# MCU.net
KiCad netlist of a schematic drawn in EAGLE
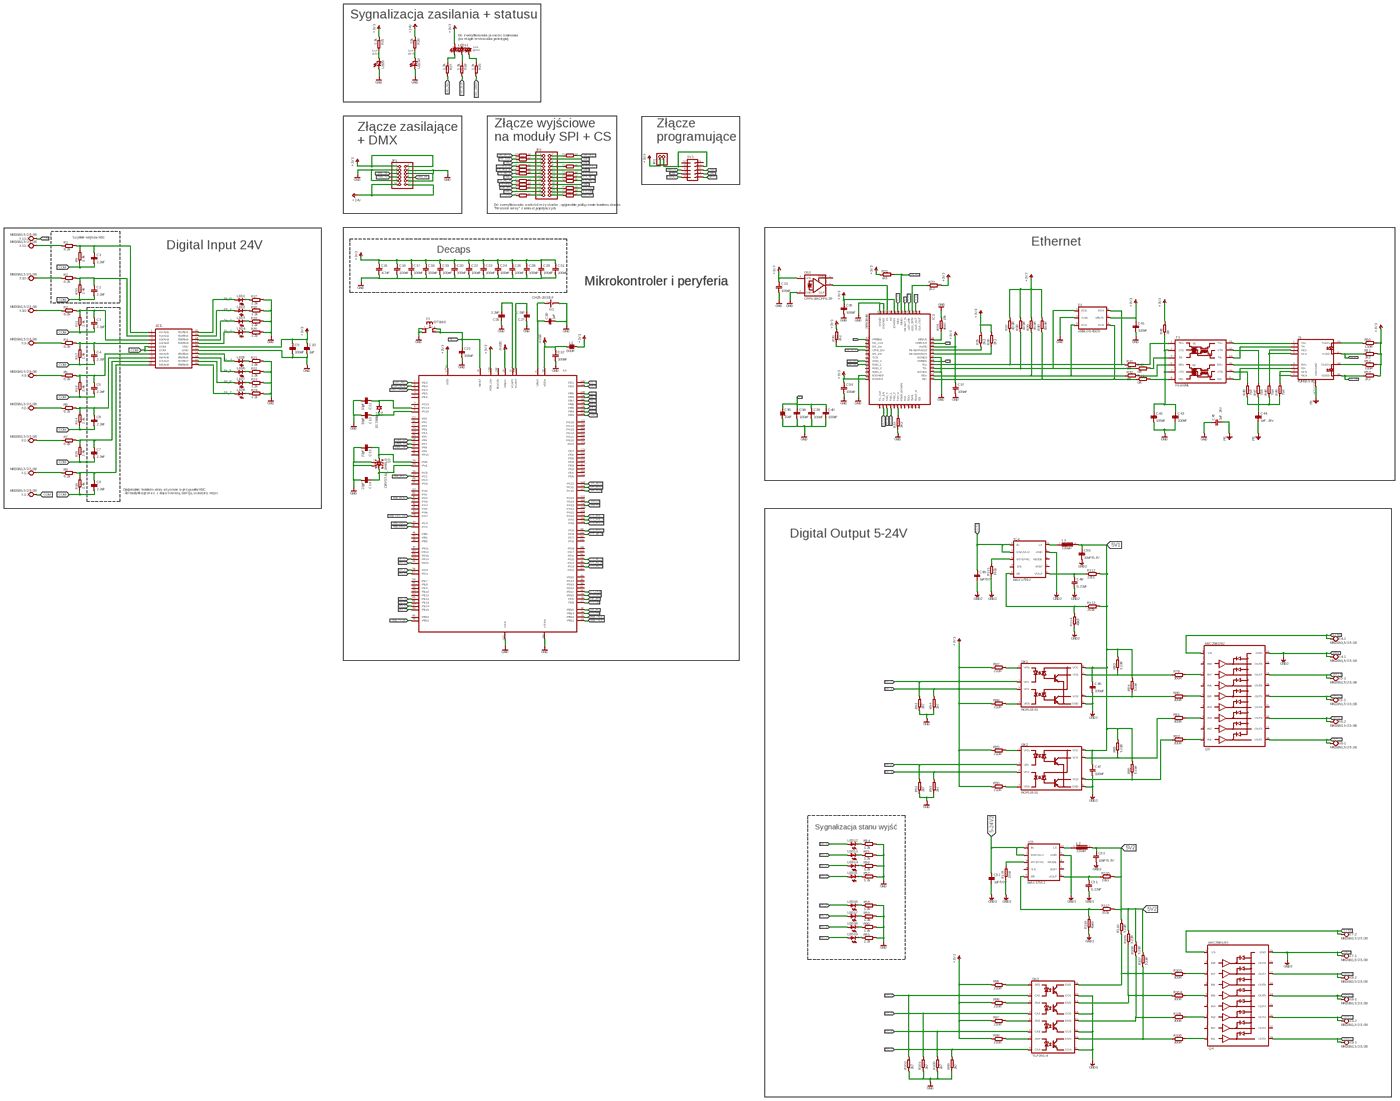
[diagram p0: schematic, sheet 1, overview]
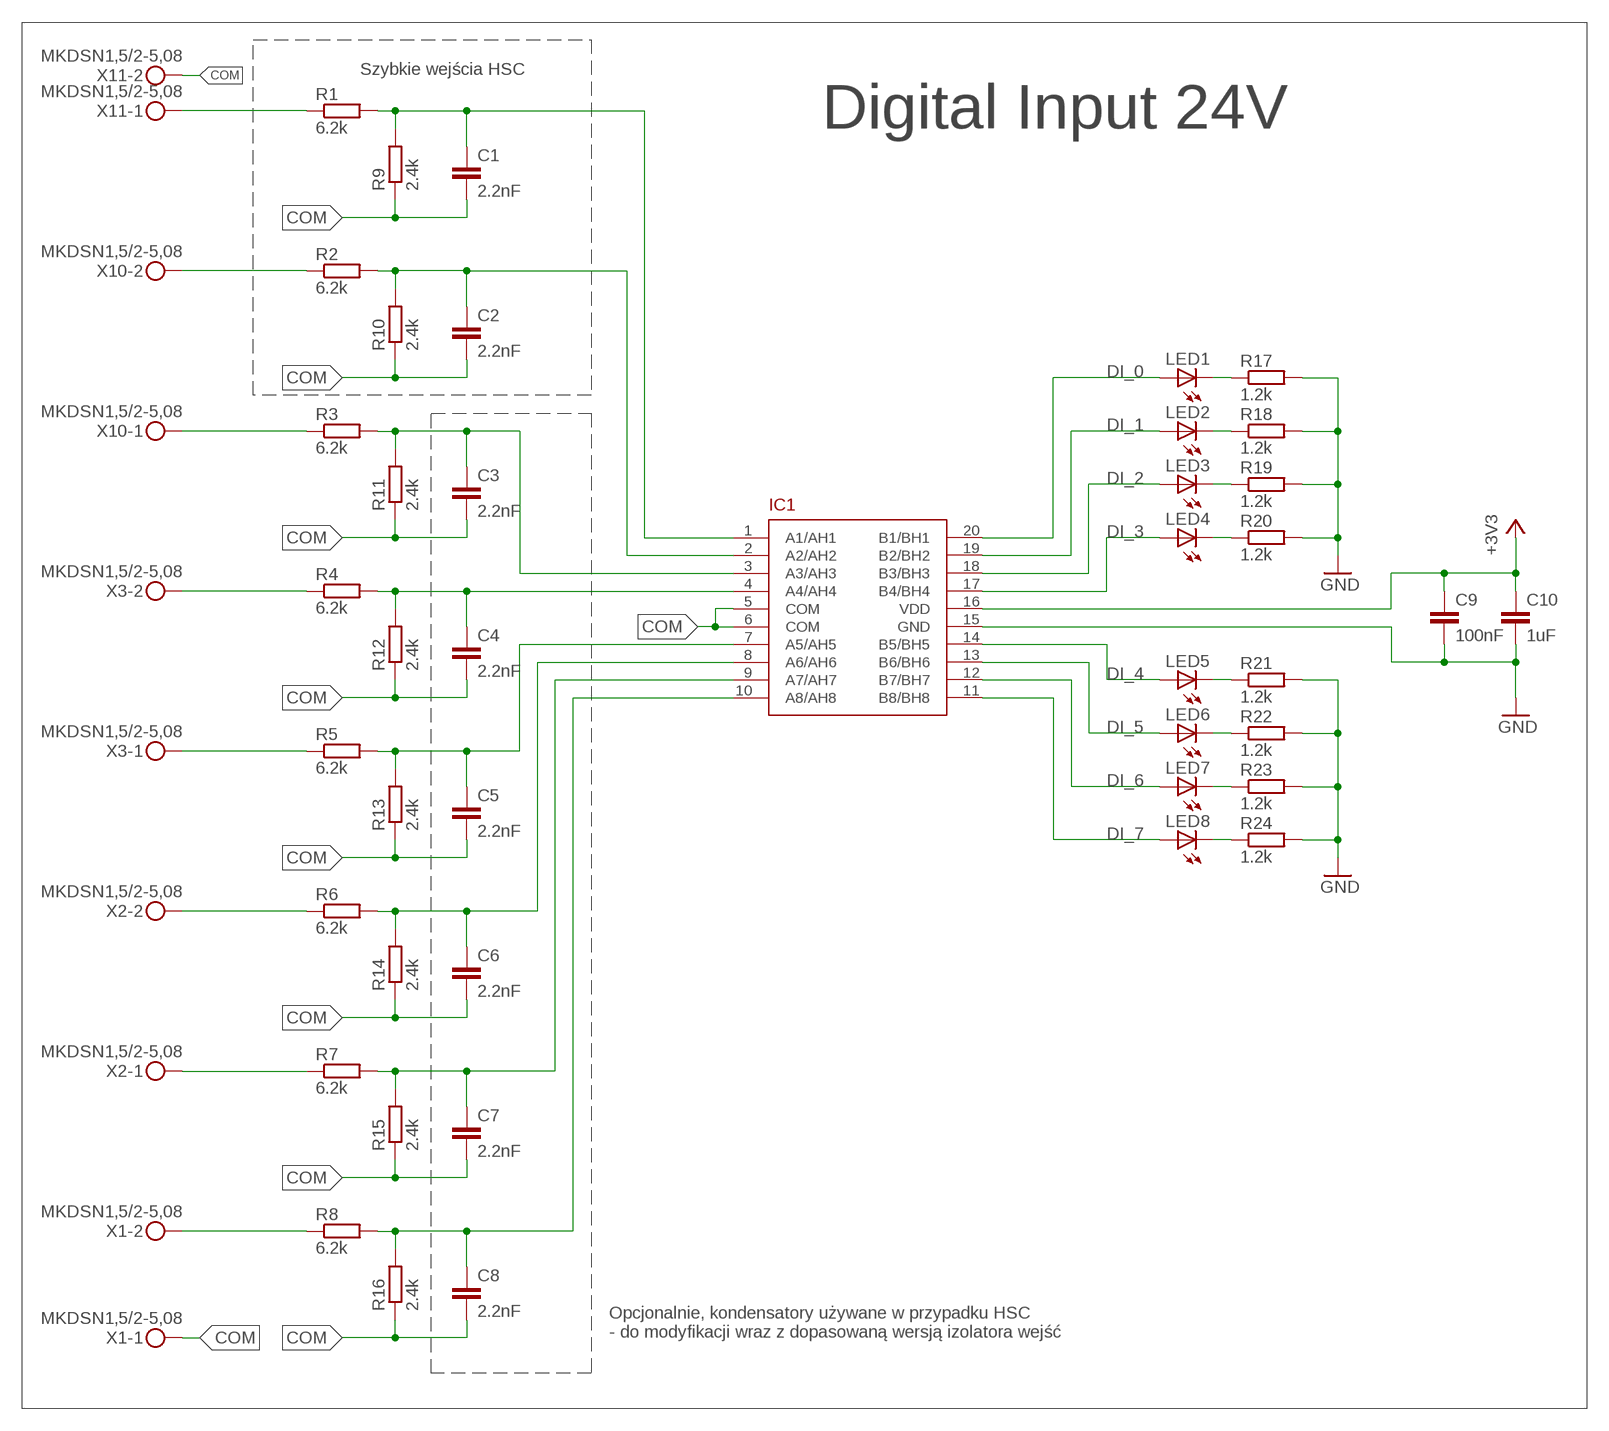
[diagram p1: schematic, sheet 1, part 1 of 5]
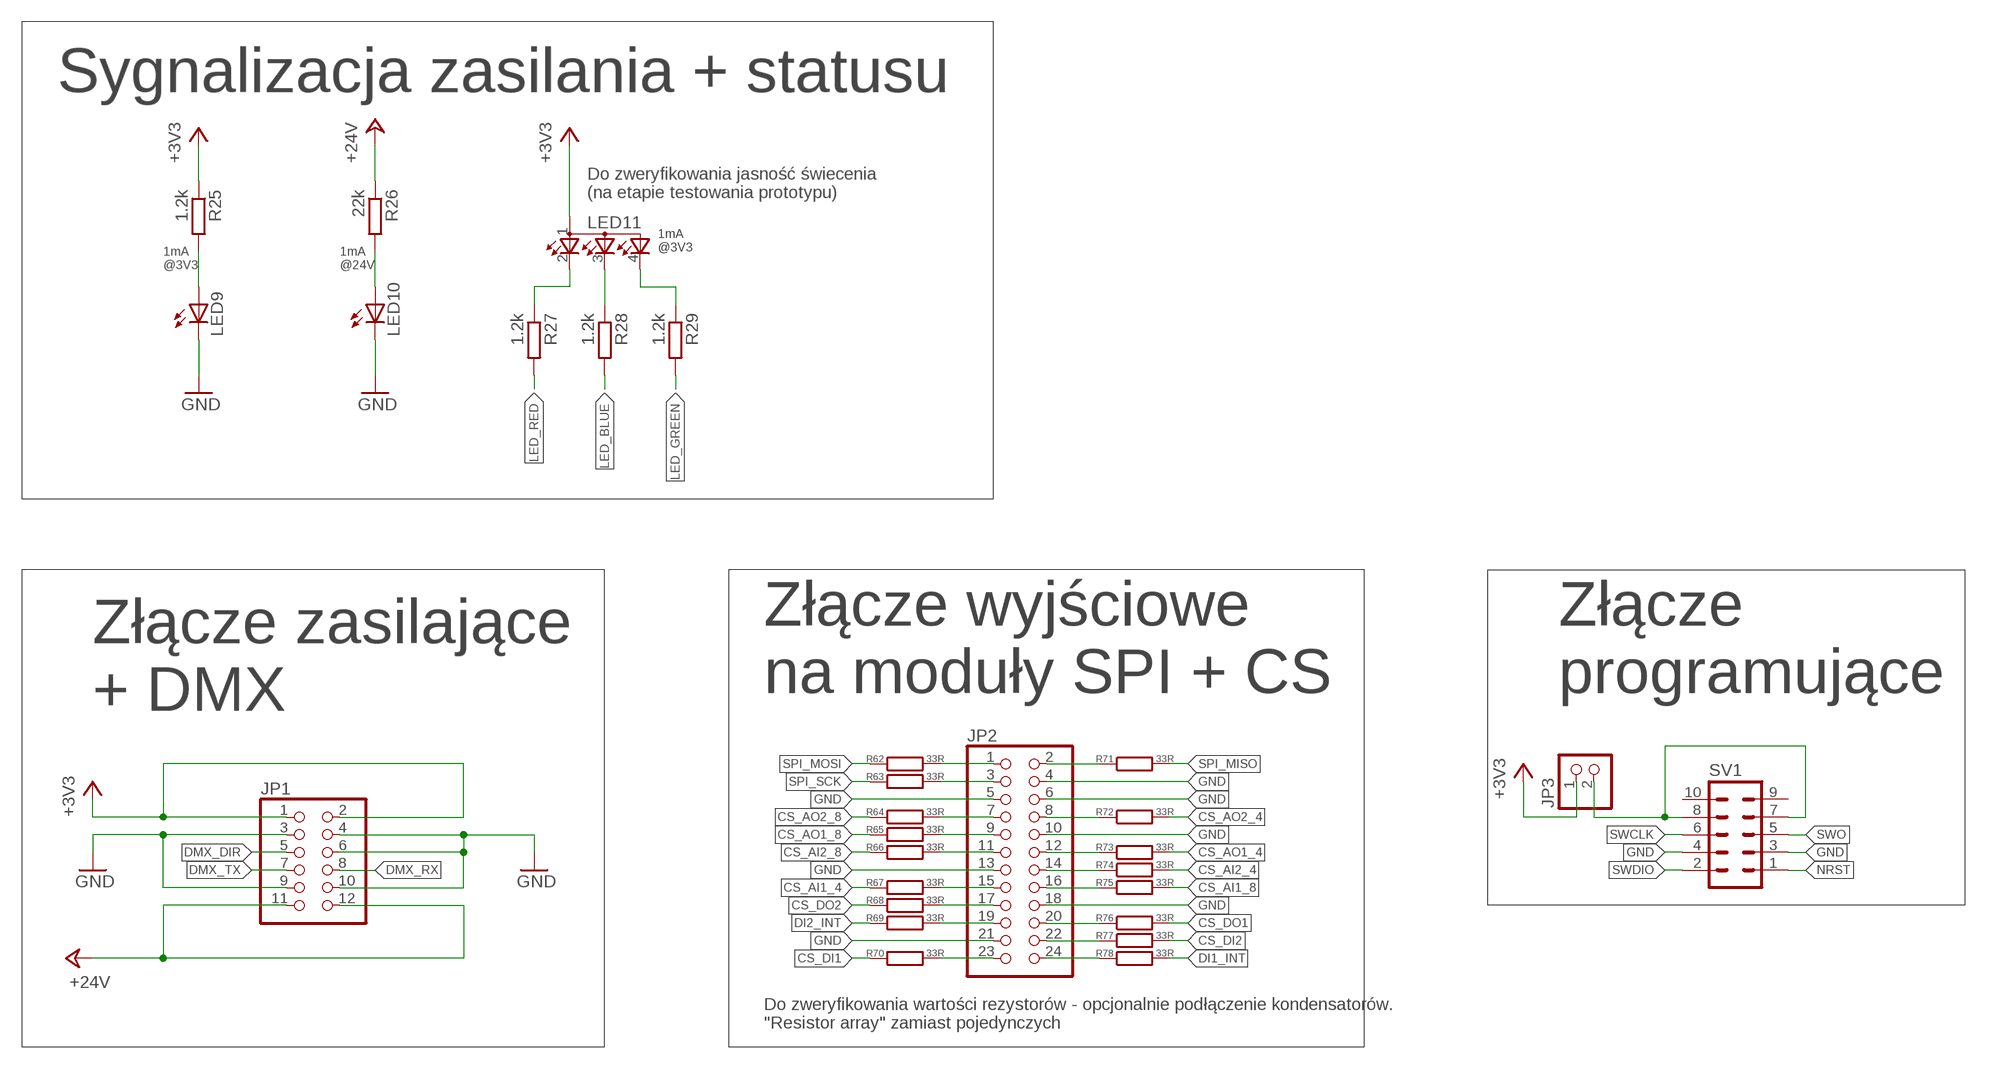
[diagram p2: schematic, sheet 1, part 2 of 5]
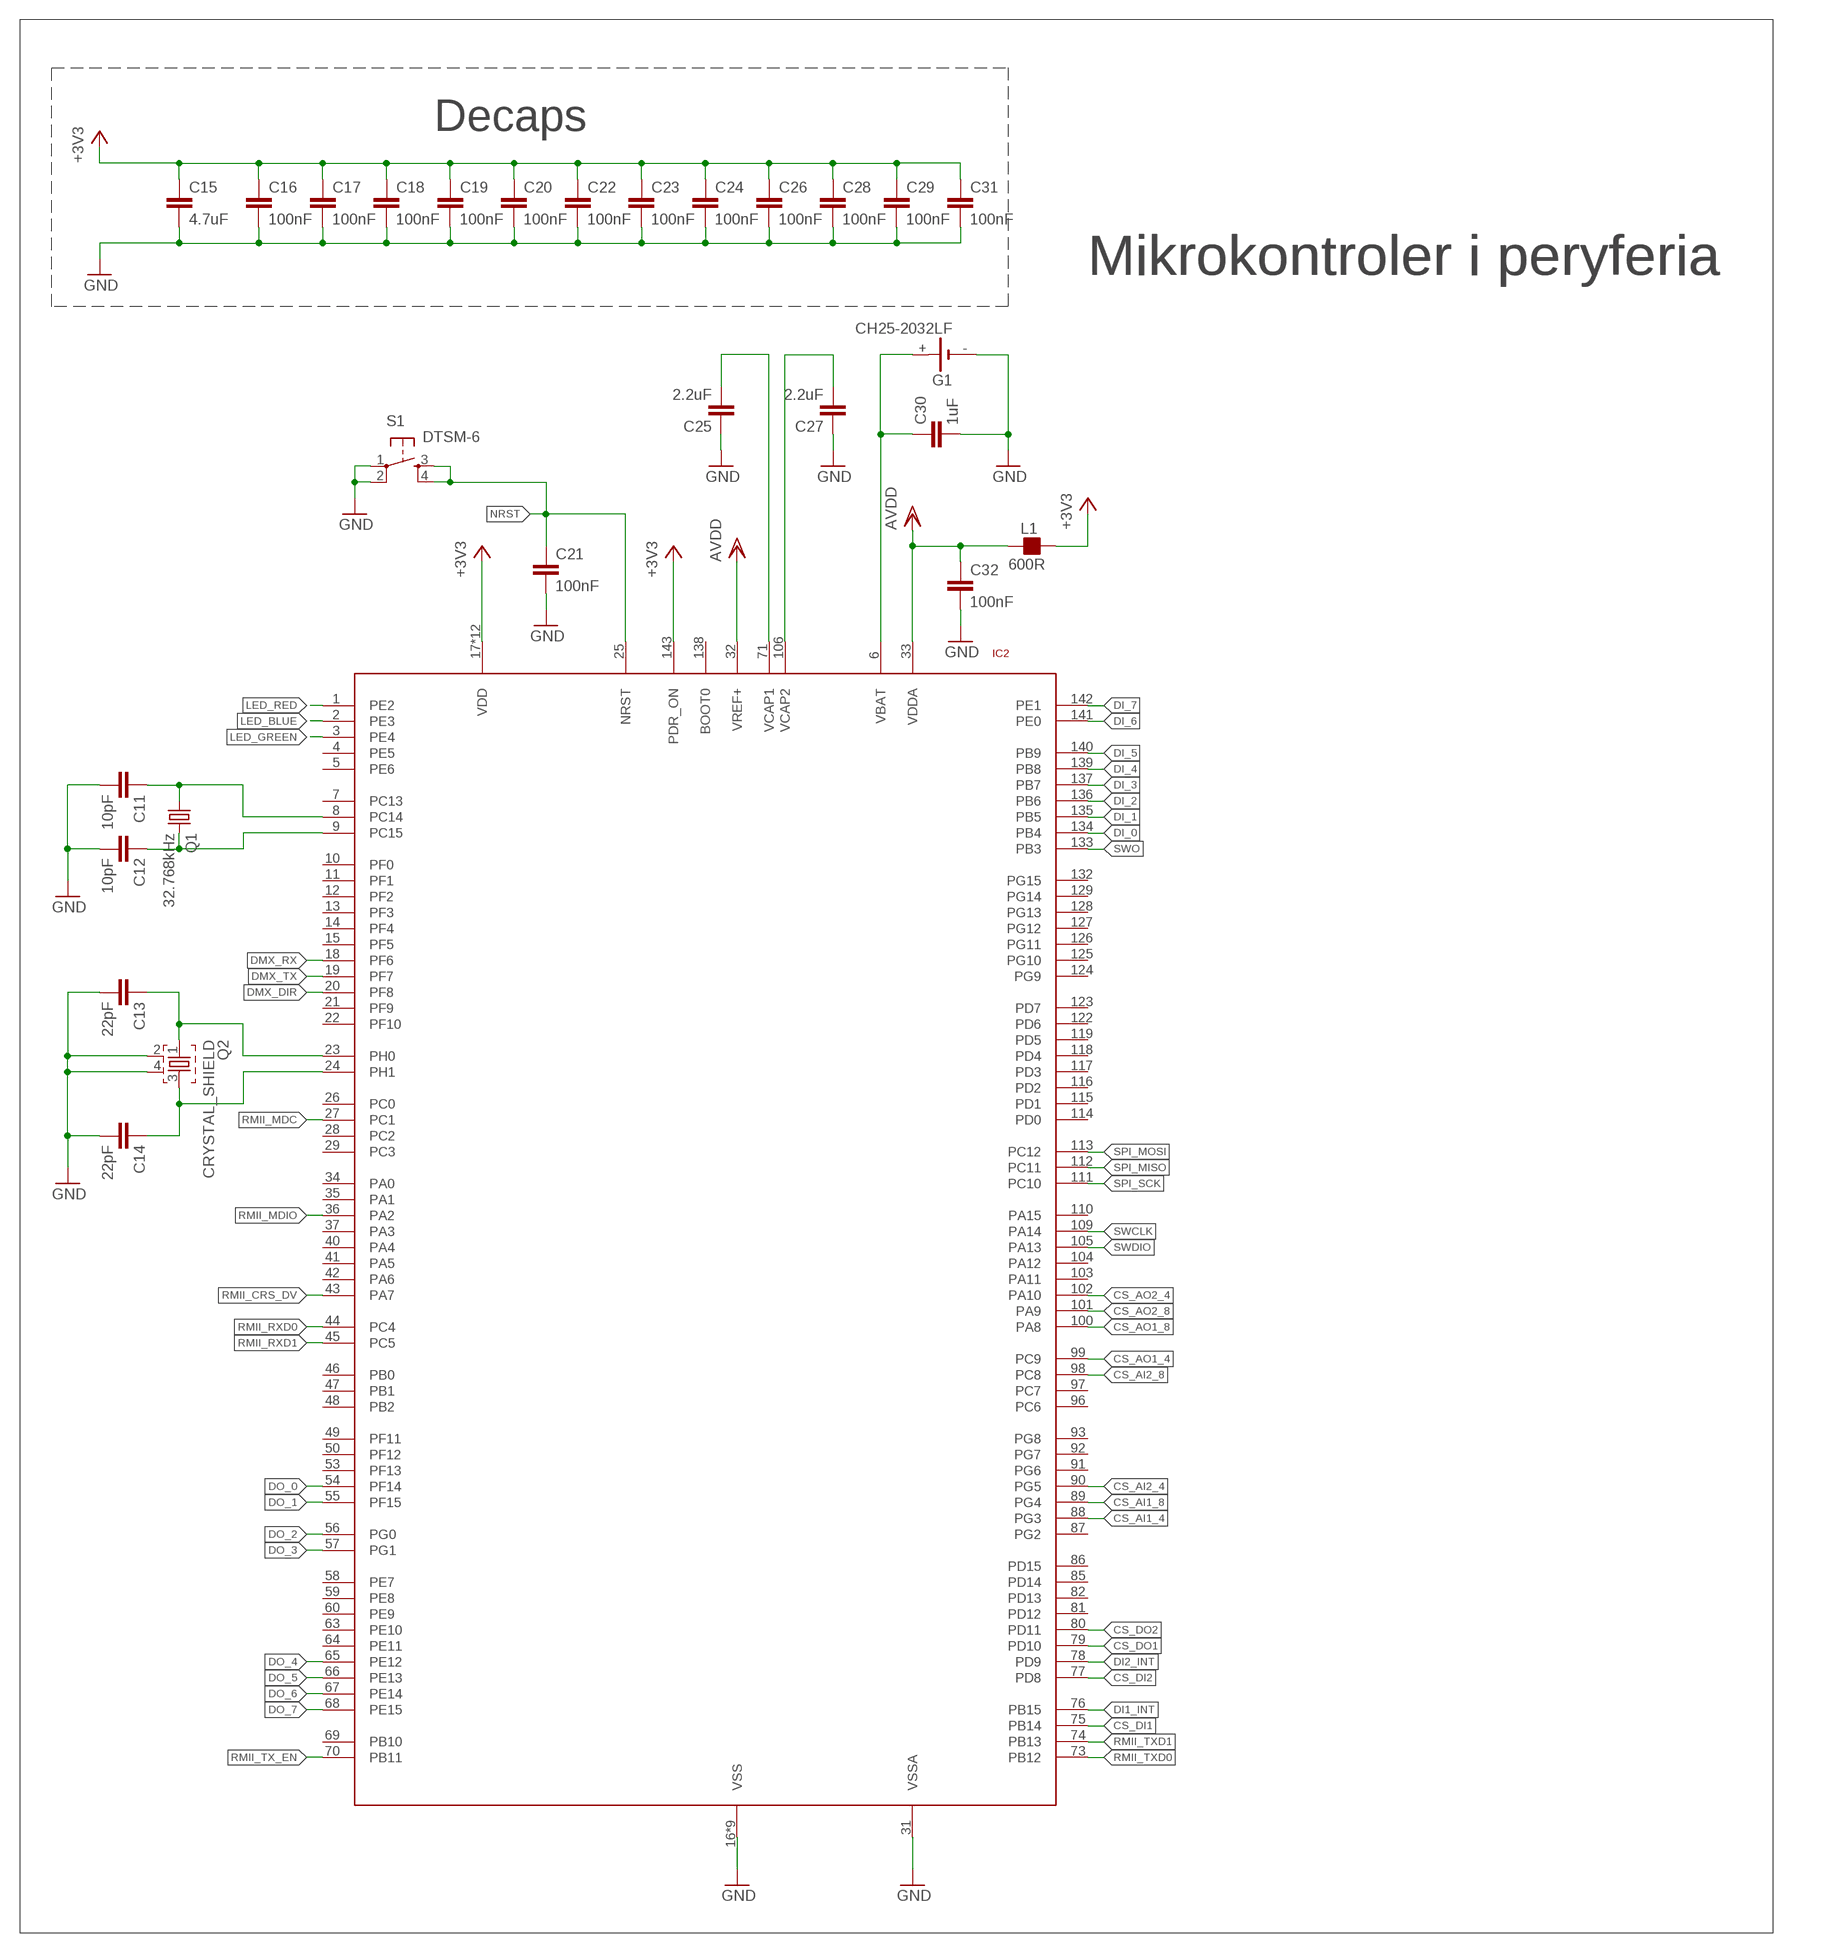
[diagram p3: schematic, sheet 1, part 3 of 5]
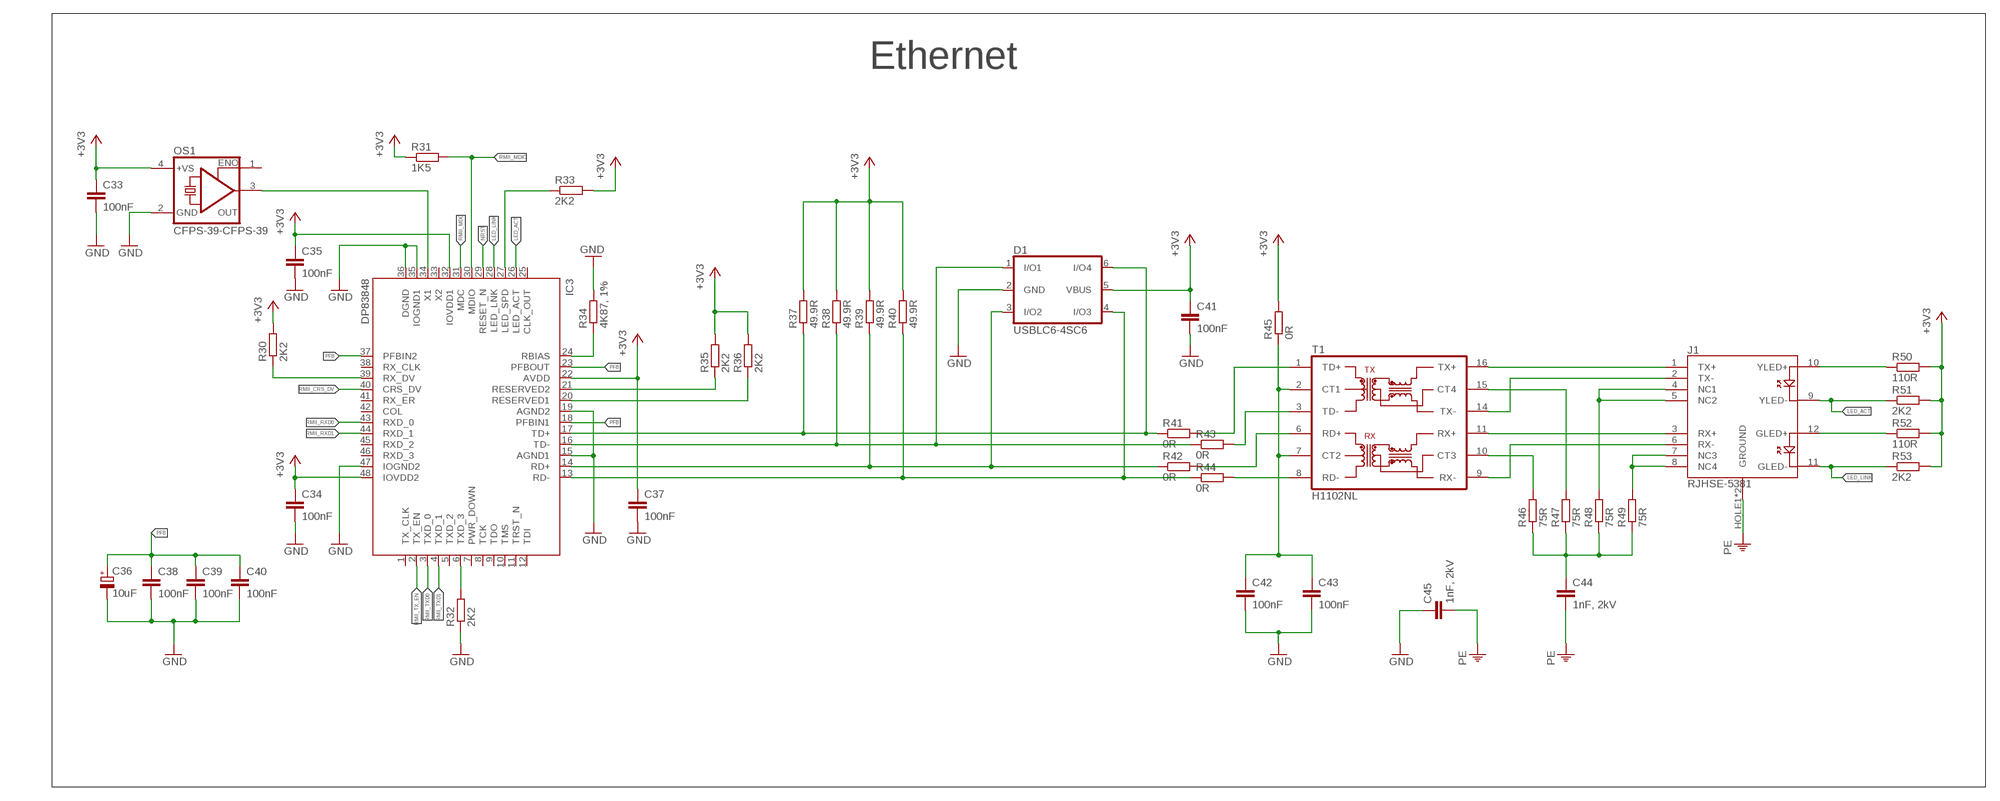
[diagram p4: schematic, sheet 1, part 4 of 5]
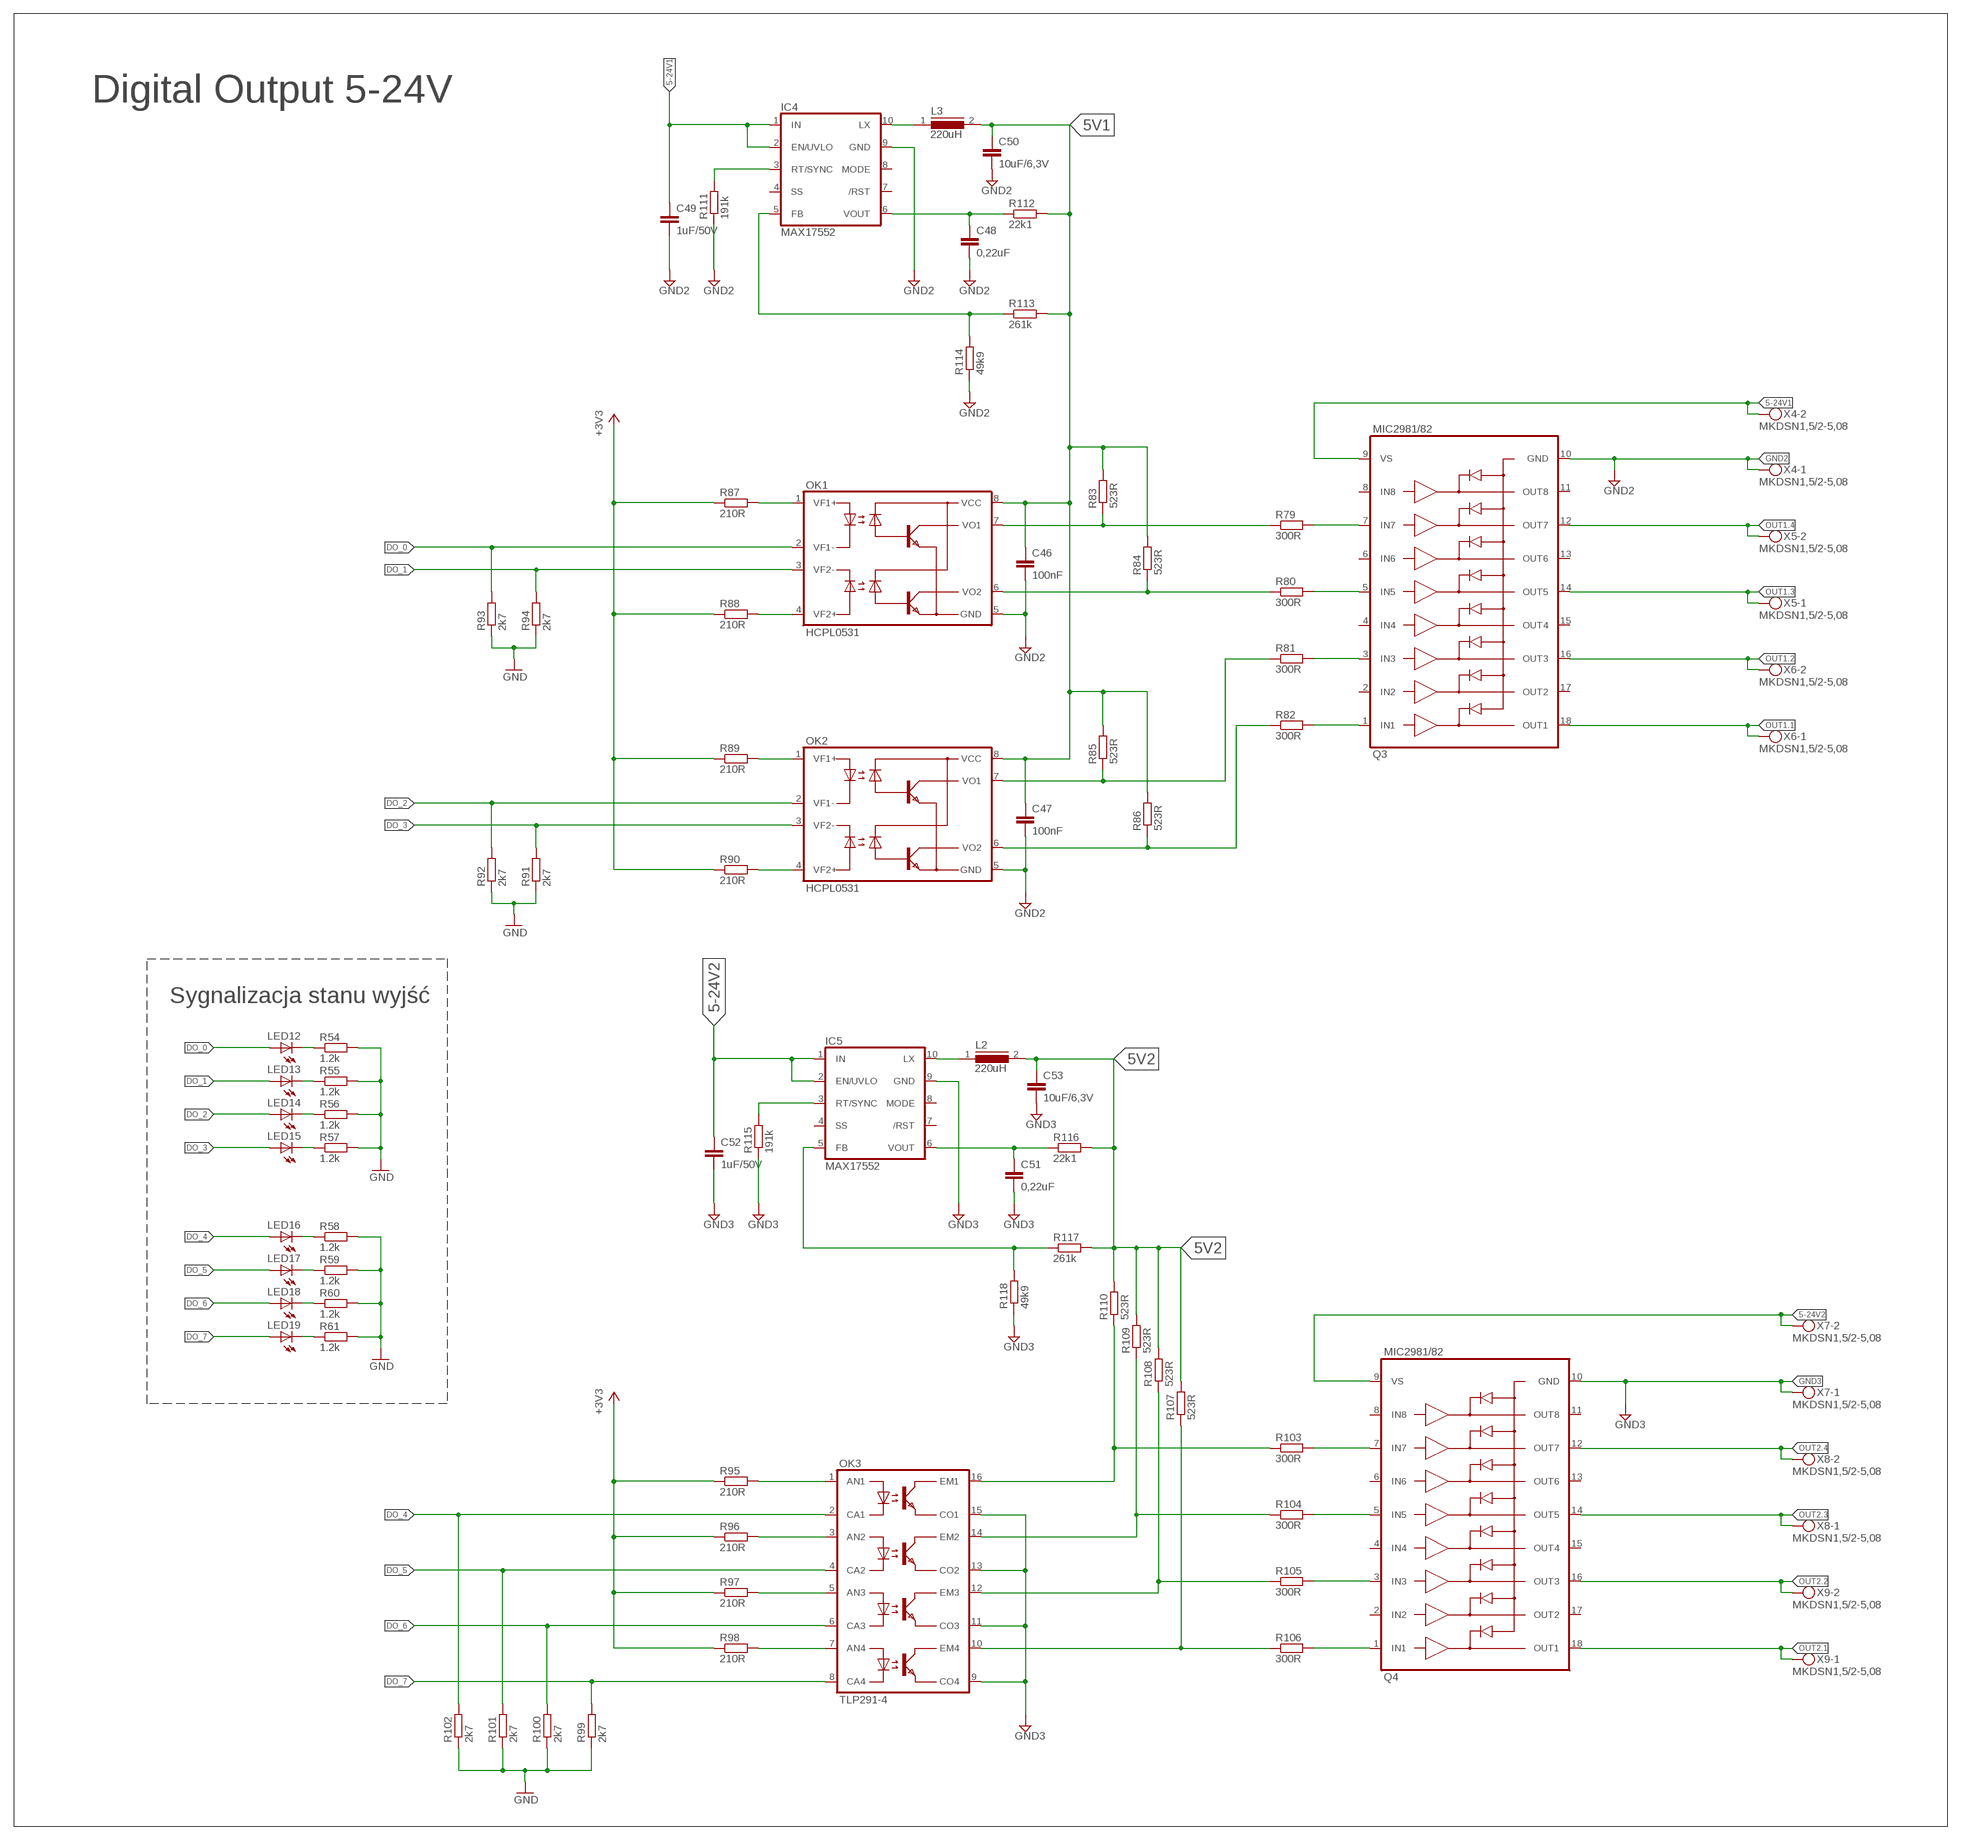
[diagram p5: schematic, sheet 1, part 5 of 5]

(export (version "E")
  (design (tool "Eeschema 10.0.6"))
  (components
    (comp (ref "C1")
      (value "2.2nF")
      (footprint "eagle-import:C0805")
      (fields (field (name "MF") "AVX") (field (name "MPN") "06035C222JAT2A"))
      (libsource (lib "eagle-import") (part "C-EUC0805"))
    )
    (comp (ref "C2")
      (value "2.2nF")
      (footprint "eagle-import:C0805")
      (fields (field (name "MF") "AVX") (field (name "MPN") "06035C222JAT2A"))
      (libsource (lib "eagle-import") (part "C-EUC0805"))
    )
    (comp (ref "C3")
      (value "2.2nF")
      (footprint "eagle-import:C0805")
      (fields (field (name "MF") "AVX") (field (name "MPN") "06035C222JAT2A"))
      (libsource (lib "eagle-import") (part "C-EUC0805"))
    )
    (comp (ref "C4")
      (value "2.2nF")
      (footprint "eagle-import:C0805")
      (fields (field (name "MF") "AVX") (field (name "MPN") "06035C222JAT2A"))
      (libsource (lib "eagle-import") (part "C-EUC0805"))
    )
    (comp (ref "C5")
      (value "2.2nF")
      (footprint "eagle-import:C0805")
      (fields (field (name "MF") "AVX") (field (name "MPN") "06035C222JAT2A"))
      (libsource (lib "eagle-import") (part "C-EUC0805"))
    )
    (comp (ref "C6")
      (value "2.2nF")
      (footprint "eagle-import:C0805")
      (fields (field (name "MF") "AVX") (field (name "MPN") "06035C222JAT2A"))
      (libsource (lib "eagle-import") (part "C-EUC0805"))
    )
    (comp (ref "C7")
      (value "2.2nF")
      (footprint "eagle-import:C0805")
      (fields (field (name "MF") "AVX") (field (name "MPN") "06035C222JAT2A"))
      (libsource (lib "eagle-import") (part "C-EUC0805"))
    )
    (comp (ref "C8")
      (value "2.2nF")
      (footprint "eagle-import:C0805")
      (fields (field (name "MF") "AVX") (field (name "MPN") "06035C222JAT2A"))
      (libsource (lib "eagle-import") (part "C-EUC0805"))
    )
    (comp (ref "C9")
      (value "100nF")
      (footprint "eagle-import:C0603K")
      (fields (field (name "MF") "AVX") (field (name "MPN") "06033C104KAT2A"))
      (libsource (lib "eagle-import") (part "C-EUC0603K"))
    )
    (comp (ref "C10")
      (value "1uF")
      (footprint "eagle-import:C0603K")
      (fields (field (name "MF") "AVX") (field (name "MPN") "0603YC105KAT4A"))
      (libsource (lib "eagle-import") (part "C-EUC0603K"))
    )
    (comp (ref "C11")
      (value "10pF")
      (footprint "eagle-import:C0603K")
      (fields (field (name "MF") "AVX") (field (name "MPN") "06035A100JAT2A"))
      (libsource (lib "eagle-import") (part "C-EUC0603K"))
    )
    (comp (ref "C12")
      (value "10pF")
      (footprint "eagle-import:C0603K")
      (fields (field (name "MF") "AVX") (field (name "MPN") "06035A100JAT2A"))
      (libsource (lib "eagle-import") (part "C-EUC0603K"))
    )
    (comp (ref "C13")
      (value "22pF")
      (footprint "eagle-import:C0603K")
      (fields (field (name "MF") "AVX") (field (name "MPN") "06035A220JAT2A"))
      (libsource (lib "eagle-import") (part "C-EUC0603K"))
    )
    (comp (ref "C14")
      (value "22pF")
      (footprint "eagle-import:C0603K")
      (fields (field (name "MF") "AVX") (field (name "MPN") "06035A220JAT2A"))
      (libsource (lib "eagle-import") (part "C-EUC0603K"))
    )
    (comp (ref "C15")
      (value "4.7uF")
      (footprint "eagle-import:C0603K")
      (fields (field (name "MF") "AVX") (field (name "MPN") "0603ZD475KAT2A"))
      (libsource (lib "eagle-import") (part "C-EUC0603K"))
    )
    (comp (ref "C16")
      (value "100nF")
      (footprint "eagle-import:C0603K")
      (fields (field (name "MF") "AVX") (field (name "MPN") "06033C104KAT2A"))
      (libsource (lib "eagle-import") (part "C-EUC0603K"))
    )
    (comp (ref "C17")
      (value "100nF")
      (footprint "eagle-import:C0603K")
      (fields (field (name "MF") "AVX") (field (name "MPN") "06033C104KAT2A"))
      (libsource (lib "eagle-import") (part "C-EUC0603K"))
    )
    (comp (ref "C18")
      (value "100nF")
      (footprint "eagle-import:C0603K")
      (fields (field (name "MF") "AVX") (field (name "MPN") "06033C104KAT2A"))
      (libsource (lib "eagle-import") (part "C-EUC0603K"))
    )
    (comp (ref "C19")
      (value "100nF")
      (footprint "eagle-import:C0603K")
      (fields (field (name "MF") "AVX") (field (name "MPN") "06033C104KAT2A"))
      (libsource (lib "eagle-import") (part "C-EUC0603K"))
    )
    (comp (ref "C20")
      (value "100nF")
      (footprint "eagle-import:C0603K")
      (fields (field (name "MF") "AVX") (field (name "MPN") "06033C104KAT2A"))
      (libsource (lib "eagle-import") (part "C-EUC0603K"))
    )
    (comp (ref "C21")
      (value "100nF")
      (footprint "eagle-import:C0603K")
      (fields (field (name "MF") "AVX") (field (name "MPN") "06033C104KAT2A"))
      (libsource (lib "eagle-import") (part "C-EUC0603K"))
    )
    (comp (ref "C22")
      (value "100nF")
      (footprint "eagle-import:C0603K")
      (fields (field (name "MF") "AVX") (field (name "MPN") "06033C104KAT2A"))
      (libsource (lib "eagle-import") (part "C-EUC0603K"))
    )
    (comp (ref "C23")
      (value "100nF")
      (footprint "eagle-import:C0603K")
      (fields (field (name "MF") "AVX") (field (name "MPN") "06033C104KAT2A"))
      (libsource (lib "eagle-import") (part "C-EUC0603K"))
    )
    (comp (ref "C24")
      (value "100nF")
      (footprint "eagle-import:C0603K")
      (fields (field (name "MF") "AVX") (field (name "MPN") "06033C104KAT2A"))
      (libsource (lib "eagle-import") (part "C-EUC0603K"))
    )
    (comp (ref "C25")
      (value "2.2uF")
      (footprint "eagle-import:C0603K")
      (fields (field (name "MF") "AVX") (field (name "MPN") "06036C225KAT2A"))
      (libsource (lib "eagle-import") (part "C-EUC0603K"))
    )
    (comp (ref "C26")
      (value "100nF")
      (footprint "eagle-import:C0603K")
      (fields (field (name "MF") "AVX") (field (name "MPN") "06033C104KAT2A"))
      (libsource (lib "eagle-import") (part "C-EUC0603K"))
    )
    (comp (ref "C27")
      (value "2.2uF")
      (footprint "eagle-import:C0603K")
      (fields (field (name "MF") "AVX") (field (name "MPN") "06036C225KAT2A"))
      (libsource (lib "eagle-import") (part "C-EUC0603K"))
    )
    (comp (ref "C28")
      (value "100nF")
      (footprint "eagle-import:C0603K")
      (fields (field (name "MF") "AVX") (field (name "MPN") "06033C104KAT2A"))
      (libsource (lib "eagle-import") (part "C-EUC0603K"))
    )
    (comp (ref "C29")
      (value "100nF")
      (footprint "eagle-import:C0603K")
      (fields (field (name "MF") "AVX") (field (name "MPN") "06033C104KAT2A"))
      (libsource (lib "eagle-import") (part "C-EUC0603K"))
    )
    (comp (ref "C30")
      (value "1uF")
      (footprint "eagle-import:C0603K")
      (fields (field (name "MF") "AVX") (field (name "MPN") "0603YC105KAT4A"))
      (libsource (lib "eagle-import") (part "C-EUC0603K"))
    )
    (comp (ref "C31")
      (value "100nF")
      (footprint "eagle-import:C0603K")
      (fields (field (name "MF") "AVX") (field (name "MPN") "06033C104KAT2A"))
      (libsource (lib "eagle-import") (part "C-EUC0603K"))
    )
    (comp (ref "C32")
      (value "100nF")
      (footprint "eagle-import:C0603K")
      (fields (field (name "MF") "AVX") (field (name "MPN") "06033C104KAT2A"))
      (libsource (lib "eagle-import") (part "C-EUC0603K"))
    )
    (comp (ref "C33")
      (value "100nF")
      (footprint "eagle-import:C0603")
      (fields (field (name "MF") "AVX") (field (name "MPN") "06033C104KAT2A"))
      (libsource (lib "eagle-import") (part "C-EUC0603"))
    )
    (comp (ref "C34")
      (value "100nF")
      (footprint "eagle-import:C0603")
      (fields (field (name "MF") "AVX") (field (name "MPN") "06033C104KAT2A"))
      (libsource (lib "eagle-import") (part "C-EUC0603"))
    )
    (comp (ref "C35")
      (value "100nF")
      (footprint "eagle-import:C0603")
      (fields (field (name "MF") "AVX") (field (name "MPN") "06033C104KAT2A"))
      (libsource (lib "eagle-import") (part "C-EUC0603"))
    )
    (comp (ref "C36")
      (value "10uF")
      (footprint "eagle-import:SMC_A")
      (fields (field (name "MF") "AVX") (field (name "MPN") "F931A106MAA"))
      (libsource (lib "eagle-import") (part "CPOL-EUSMCA"))
    )
    (comp (ref "C37")
      (value "100nF")
      (footprint "eagle-import:C0603")
      (fields (field (name "MF") "AVX") (field (name "MPN") "06033C104KAT2A"))
      (libsource (lib "eagle-import") (part "C-EUC0603"))
    )
    (comp (ref "C38")
      (value "100nF")
      (footprint "eagle-import:C0603")
      (fields (field (name "MF") "AVX") (field (name "MPN") "06033C104KAT2A"))
      (libsource (lib "eagle-import") (part "C-EUC0603"))
    )
    (comp (ref "C39")
      (value "100nF")
      (footprint "eagle-import:C0603")
      (fields (field (name "MF") "AVX") (field (name "MPN") "06033C104KAT2A"))
      (libsource (lib "eagle-import") (part "C-EUC0603"))
    )
    (comp (ref "C40")
      (value "100nF")
      (footprint "eagle-import:C0603")
      (fields (field (name "MF") "AVX") (field (name "MPN") "06033C104KAT2A"))
      (libsource (lib "eagle-import") (part "C-EUC0603"))
    )
    (comp (ref "C41")
      (value "100nF")
      (footprint "eagle-import:C0603")
      (fields (field (name "MF") "AVX") (field (name "MPN") "06033C104KAT2A"))
      (libsource (lib "eagle-import") (part "C-EUC0603"))
    )
    (comp (ref "C42")
      (value "100nF")
      (footprint "eagle-import:C0603")
      (fields (field (name "MF") "AVX") (field (name "MPN") "06033C104KAT2A"))
      (libsource (lib "eagle-import") (part "C-EUC0603"))
    )
    (comp (ref "C43")
      (value "100nF")
      (footprint "eagle-import:C0603")
      (fields (field (name "MF") "AVX") (field (name "MPN") "06033C104KAT2A"))
      (libsource (lib "eagle-import") (part "C-EUC0603"))
    )
    (comp (ref "C44")
      (value "1nF, 2kV")
      (footprint "eagle-import:C1206")
      (fields (field (name "MF") "Vishay") (field (name "MPN") "VJ1206Y102MXFAT4X"))
      (libsource (lib "eagle-import") (part "C-EUC1206"))
    )
    (comp (ref "C45")
      (value "1nF, 2kV")
      (footprint "eagle-import:C1206")
      (fields (field (name "MF") "Vishay") (field (name "MPN") "VJ1206Y102MXFAT4X"))
      (libsource (lib "eagle-import") (part "C-EUC1206"))
    )
    (comp (ref "C46")
      (value "100nF")
      (footprint "eagle-import:C0603")
      (fields (field (name "MF") "AVX") (field (name "MPN") "06033C104KAT2A"))
      (libsource (lib "eagle-import") (part "C-EUC0603"))
    )
    (comp (ref "C47")
      (value "100nF")
      (footprint "eagle-import:C0603")
      (fields (field (name "MF") "AVX") (field (name "MPN") "06033C104KAT2A"))
      (libsource (lib "eagle-import") (part "C-EUC0603"))
    )
    (comp (ref "C48")
      (value "0,22uF")
      (footprint "eagle-import:C0603")
      (fields (field (name "MF") "AVX") (field (name "MPN") "0603ZC224KAT9A"))
      (libsource (lib "eagle-import") (part "C-EUC0603"))
    )
    (comp (ref "C49")
      (value "1uF/50V")
      (footprint "eagle-import:C1206")
      (fields (field (name "MF") "AVX") (field (name "MPN") "12065C105M4Z2A"))
      (libsource (lib "eagle-import") (part "C-EUC1206"))
    )
    (comp (ref "C50")
      (value "10uF/6,3V")
      (footprint "eagle-import:C1206")
      (fields (field (name "MF") "AVX") (field (name "MPN") "12066G106ZAT4A"))
      (libsource (lib "eagle-import") (part "C-EUC1206"))
    )
    (comp (ref "C51")
      (value "0,22uF")
      (footprint "eagle-import:C0603")
      (fields (field (name "MF") "AVX") (field (name "MPN") "0603ZC224KAT9A"))
      (libsource (lib "eagle-import") (part "C-EUC0603"))
    )
    (comp (ref "C52")
      (value "1uF/50V")
      (footprint "eagle-import:C1206")
      (fields (field (name "MF") "AVX") (field (name "MPN") "12065C105M4Z2A"))
      (libsource (lib "eagle-import") (part "C-EUC1206"))
    )
    (comp (ref "C53")
      (value "10uF/6,3V")
      (footprint "eagle-import:C1206")
      (fields (field (name "MF") "AVX") (field (name "MPN") "12066G106ZAT4A"))
      (libsource (lib "eagle-import") (part "C-EUC1206"))
    )
    (comp (ref "D1")
      (value "USBLC6-4SC6")
      (footprint "eagle-import:SOT23-6")
      (fields (field (name "MF") "ST-MICROELECTRONICS"))
      (libsource (lib "eagle-import") (part "USBLC6-4SC6"))
    )
    (comp (ref "G1")
      (value "CH25-2032LF")
      (footprint "eagle-import:CH25-2032LF")
      (fields (field (name "MF") "G1") (field (name "MPN") "CH25-2032"))
      (libsource (lib "eagle-import") (part "CH25-2032LF"))
    )
    (comp (ref "IC1")
      (value "SI8382P-IU")
      (footprint "eagle-import:QSOP-20")
      (fields (field (name "MF") "Silicon Labs"))
      (libsource (lib "eagle-import") (part "SI838X"))
    )
    (comp (ref "IC2")
      (value "STM32F429ZILQFP144")
      (footprint "eagle-import:LQFP144")
      (fields (field (name "MF") "STMicroelectronics") (field (name "MPN") "STM32F429ZIT6"))
      (libsource (lib "eagle-import") (part "STM32F429ZILQFP144"))
    )
    (comp (ref "IC3")
      (value "DP83848")
      (footprint "eagle-import:LQFP48")
      (fields
        (field (name "MPN") "DP83848VYB")
        (field (name "MF") "Texas Instruments")
        (field (name "MPN_1") "DP83848CVV/NOPB")
      )
      (libsource (lib "eagle-import") (part "DP83848"))
    )
    (comp (ref "IC4")
      (value "MAX17552")
      (footprint "eagle-import:TSSOP-10(10UMAX)")
      (fields (field (name "MF") "Maxim") (field (name "MPN") "MAX17552AUB+"))
      (libsource (lib "eagle-import") (part "MAX17552"))
    )
    (comp (ref "IC5")
      (value "MAX17552")
      (footprint "eagle-import:TSSOP-10(10UMAX)")
      (fields (field (name "MF") "Maxim") (field (name "MPN") "MAX17552AUB+"))
      (libsource (lib "eagle-import") (part "MAX17552"))
    )
    (comp (ref "J1")
      (value "RJHSE-5381")
      (footprint "eagle-import:MAGJACK-19938")
      (fields (field (name "MF") "AMPHENOL"))
      (libsource (lib "eagle-import") (part "RJHSE-5381"))
    )
    (comp (ref "JP1")
      (value "PINHD-2X6")
      (footprint "eagle-import:2X06")
      (fields (field (name "MF") "NINIGI") (field (name "MPN") "ZL2019-40"))
      (libsource (lib "eagle-import") (part "PINHD-2X6"))
    )
    (comp (ref "JP2")
      (value "PINHD-2X12")
      (footprint "eagle-import:2X12")
      (fields (field (name "MF") "NINIGI") (field (name "MPN") "ZL2019-40"))
      (libsource (lib "eagle-import") (part "PINHD-2X12"))
    )
    (comp (ref "JP3")
      (value "PINHD-1X2")
      (footprint "eagle-import:1X02")
      (fields (field (name "MF") "CONNFLY") (field (name "MPN") "DS1021-1*20SF1-5"))
      (libsource (lib "eagle-import") (part "PINHD-1X2"))
    )
    (comp (ref "L1")
      (value "600R")
      (footprint "eagle-import:L0603")
      (fields (field (name "MF") "TDK") (field (name "MPN") "MMZ1608S601ATD25"))
      (libsource (lib "eagle-import") (part "FB_0603"))
    )
    (comp (ref "L2")
      (value "220uH")
      (footprint "eagle-import:SRR4528A")
      (fields (field (name "MF") "Bourns") (field (name "MPN") "SRR4528A-221M"))
      (libsource (lib "eagle-import") (part "SRR4528A221M"))
    )
    (comp (ref "L3")
      (value "220uH")
      (footprint "eagle-import:SRR4528A")
      (fields (field (name "MF") "Bourns") (field (name "MPN") "SRR4528A-221M"))
      (libsource (lib "eagle-import") (part "SRR4528A221M"))
    )
    (comp (ref "LED1")
      (value "LEDCHIP-LED0603")
      (footprint "eagle-import:CHIP-LED0603")
      (fields (field (name "MF") "Kingbright") (field (name "MPN") "APTD1608LCGCK"))
      (libsource (lib "eagle-import") (part "LEDCHIP-LED0603"))
    )
    (comp (ref "LED2")
      (value "LEDCHIP-LED0603")
      (footprint "eagle-import:CHIP-LED0603")
      (fields (field (name "MF") "Kingbright") (field (name "MPN") "APTD1608LCGCK"))
      (libsource (lib "eagle-import") (part "LEDCHIP-LED0603"))
    )
    (comp (ref "LED3")
      (value "LEDCHIP-LED0603")
      (footprint "eagle-import:CHIP-LED0603")
      (fields (field (name "MF") "Kingbright") (field (name "MPN") "APTD1608LCGCK"))
      (libsource (lib "eagle-import") (part "LEDCHIP-LED0603"))
    )
    (comp (ref "LED4")
      (value "LEDCHIP-LED0603")
      (footprint "eagle-import:CHIP-LED0603")
      (fields (field (name "MF") "Kingbright") (field (name "MPN") "APTD1608LCGCK"))
      (libsource (lib "eagle-import") (part "LEDCHIP-LED0603"))
    )
    (comp (ref "LED5")
      (value "LEDCHIP-LED0603")
      (footprint "eagle-import:CHIP-LED0603")
      (fields (field (name "MF") "Kingbright") (field (name "MPN") "APTD1608LCGCK"))
      (libsource (lib "eagle-import") (part "LEDCHIP-LED0603"))
    )
    (comp (ref "LED6")
      (value "LEDCHIP-LED0603")
      (footprint "eagle-import:CHIP-LED0603")
      (fields (field (name "MF") "Kingbright") (field (name "MPN") "APTD1608LCGCK"))
      (libsource (lib "eagle-import") (part "LEDCHIP-LED0603"))
    )
    (comp (ref "LED7")
      (value "LEDCHIP-LED0603")
      (footprint "eagle-import:CHIP-LED0603")
      (fields (field (name "MF") "Kingbright") (field (name "MPN") "APTD1608LCGCK"))
      (libsource (lib "eagle-import") (part "LEDCHIP-LED0603"))
    )
    (comp (ref "LED8")
      (value "LEDCHIP-LED0603")
      (footprint "eagle-import:CHIP-LED0603")
      (fields (field (name "MF") "Kingbright") (field (name "MPN") "APTD1608LCGCK"))
      (libsource (lib "eagle-import") (part "LEDCHIP-LED0603"))
    )
    (comp (ref "LED9")
      (value "LEDCHIP-LED0603")
      (footprint "eagle-import:CHIP-LED0603")
      (fields (field (name "MF") "Kingbright") (field (name "MPN") "APTD1608LSURCK"))
      (libsource (lib "eagle-import") (part "LEDCHIP-LED0603"))
    )
    (comp (ref "LED10")
      (value "LEDCHIP-LED0603")
      (footprint "eagle-import:CHIP-LED0603")
      (fields (field (name "MF") "Kingbright") (field (name "MPN") "APTD1608LSURCK"))
      (libsource (lib "eagle-import") (part "LEDCHIP-LED0603"))
    )
    (comp (ref "LED11")
      (value "APHF1608SEEQBDZGKC")
      (footprint "eagle-import:APHF1608SEEQBDZGKC")
      (fields (field (name "MF") "Kingbright"))
      (libsource (lib "eagle-import") (part "APHF1608SEEQBDZGKC"))
    )
    (comp (ref "LED12")
      (value "LEDCHIP-LED0603")
      (footprint "eagle-import:CHIP-LED0603")
      (fields (field (name "MF") "Kingbright") (field (name "MPN") "APTD1608LCGCK"))
      (libsource (lib "eagle-import") (part "LEDCHIP-LED0603"))
    )
    (comp (ref "LED13")
      (value "LEDCHIP-LED0603")
      (footprint "eagle-import:CHIP-LED0603")
      (fields (field (name "MF") "Kingbright") (field (name "MPN") "APTD1608LCGCK"))
      (libsource (lib "eagle-import") (part "LEDCHIP-LED0603"))
    )
    (comp (ref "LED14")
      (value "LEDCHIP-LED0603")
      (footprint "eagle-import:CHIP-LED0603")
      (fields (field (name "MF") "Kingbright") (field (name "MPN") "APTD1608LCGCK"))
      (libsource (lib "eagle-import") (part "LEDCHIP-LED0603"))
    )
    (comp (ref "LED15")
      (value "LEDCHIP-LED0603")
      (footprint "eagle-import:CHIP-LED0603")
      (fields (field (name "MF") "Kingbright") (field (name "MPN") "APTD1608LCGCK"))
      (libsource (lib "eagle-import") (part "LEDCHIP-LED0603"))
    )
    (comp (ref "LED16")
      (value "LEDCHIP-LED0603")
      (footprint "eagle-import:CHIP-LED0603")
      (fields (field (name "MF") "Kingbright") (field (name "MPN") "APTD1608LCGCK"))
      (libsource (lib "eagle-import") (part "LEDCHIP-LED0603"))
    )
    (comp (ref "LED17")
      (value "LEDCHIP-LED0603")
      (footprint "eagle-import:CHIP-LED0603")
      (fields (field (name "MF") "Kingbright") (field (name "MPN") "APTD1608LCGCK"))
      (libsource (lib "eagle-import") (part "LEDCHIP-LED0603"))
    )
    (comp (ref "LED18")
      (value "LEDCHIP-LED0603")
      (footprint "eagle-import:CHIP-LED0603")
      (fields (field (name "MF") "Kingbright") (field (name "MPN") "APTD1608LCGCK"))
      (libsource (lib "eagle-import") (part "LEDCHIP-LED0603"))
    )
    (comp (ref "LED19")
      (value "LEDCHIP-LED0603")
      (footprint "eagle-import:CHIP-LED0603")
      (fields (field (name "MF") "Kingbright") (field (name "MPN") "APTD1608LCGCK"))
      (libsource (lib "eagle-import") (part "LEDCHIP-LED0603"))
    )
    (comp (ref "OK1")
      (value "HCPL0531")
      (footprint "eagle-import:SOIC08")
      (fields (field (name "MF") "Broadcom / Avago") (field (name "MPN") "HCPL-0531-500E"))
      (libsource (lib "eagle-import") (part "HCPL0531"))
    )
    (comp (ref "OK2")
      (value "HCPL0531")
      (footprint "eagle-import:SOIC08")
      (fields (field (name "MF") "Broadcom / Avago") (field (name "MPN") "HCPL-0531-500E"))
      (libsource (lib "eagle-import") (part "HCPL0531"))
    )
    (comp (ref "OK3")
      (value "TLP291-4")
      (footprint "eagle-import:SO16")
      (fields (field (name "MF") "Toshiba") (field (name "MPN") "TLP291-4(GB,E)"))
      (libsource (lib "eagle-import") (part "TLP291-4"))
    )
    (comp (ref "OS1")
      (value "CFPS-39-CFPS-39")
      (footprint "eagle-import:3.4X2.7-4-PAD")
      (fields (field (name "MF") "IQD") (field (name "MPN") "LFSPXO025560"))
      (libsource (lib "eagle-import") (part "CFPS-39-CFPS-39"))
    )
    (comp (ref "Q1")
      (value "32.768kHz")
      (footprint "eagle-import:CRYSTAL_3.5X1.5")
      (fields (field (name "MF") "ECS") (field (name "MPN") "ECS-.327-9-34QCS-TR"))
      (libsource (lib "eagle-import") (part "CRYSTAL3.5X1.5"))
    )
    (comp (ref "Q2")
      (value "CRYSTAL_SHIELD")
      (footprint "eagle-import:CRYSTAL_5X3.2")
      (fields (field (name "MF") "IQD") (field (name "MPN") "LFXTAL059158"))
      (libsource (lib "eagle-import") (part "CRYSTAL_SHIELD"))
    )
    (comp (ref "Q3")
      (value "MIC2981/82")
      (footprint "eagle-import:SOP18")
      (fields (field (name "MF") "Microchip") (field (name "MPN") "MIC2981/82YWM"))
      (libsource (lib "eagle-import") (part "MIC2981/82"))
    )
    (comp (ref "Q4")
      (value "MIC2981/82")
      (footprint "eagle-import:SOP18")
      (fields (field (name "MF") "Microchip") (field (name "MPN") "MIC2981/82YWM"))
      (libsource (lib "eagle-import") (part "MIC2981/82"))
    )
    (comp (ref "R1")
      (value "6.2k")
      (footprint "eagle-import:R1206")
      (fields (field (name "MF") "Yageo") (field (name "MPN") "RC1206JR-076K2L"))
      (libsource (lib "eagle-import") (part "R-EU_R1206"))
    )
    (comp (ref "R2")
      (value "6.2k")
      (footprint "eagle-import:R1206")
      (fields (field (name "MF") "Yageo") (field (name "MPN") "RC1206JR-076K2L"))
      (libsource (lib "eagle-import") (part "R-EU_R1206"))
    )
    (comp (ref "R3")
      (value "6.2k")
      (footprint "eagle-import:R1206")
      (fields (field (name "MF") "Yageo") (field (name "MPN") "RC1206JR-076K2L"))
      (libsource (lib "eagle-import") (part "R-EU_R1206"))
    )
    (comp (ref "R4")
      (value "6.2k")
      (footprint "eagle-import:R1206")
      (fields (field (name "MF") "Yageo") (field (name "MPN") "RC1206JR-076K2L"))
      (libsource (lib "eagle-import") (part "R-EU_R1206"))
    )
    (comp (ref "R5")
      (value "6.2k")
      (footprint "eagle-import:R1206")
      (fields (field (name "MF") "Yageo") (field (name "MPN") "RC1206JR-076K2L"))
      (libsource (lib "eagle-import") (part "R-EU_R1206"))
    )
    (comp (ref "R6")
      (value "6.2k")
      (footprint "eagle-import:R1206")
      (fields (field (name "MF") "Yageo") (field (name "MPN") "RC1206JR-076K2L"))
      (libsource (lib "eagle-import") (part "R-EU_R1206"))
    )
    (comp (ref "R7")
      (value "6.2k")
      (footprint "eagle-import:R1206")
      (fields (field (name "MF") "Yageo") (field (name "MPN") "RC1206JR-076K2L"))
      (libsource (lib "eagle-import") (part "R-EU_R1206"))
    )
    (comp (ref "R8")
      (value "6.2k")
      (footprint "eagle-import:R1206")
      (fields (field (name "MF") "Yageo") (field (name "MPN") "RC1206JR-076K2L"))
      (libsource (lib "eagle-import") (part "R-EU_R1206"))
    )
    (comp (ref "R9")
      (value "2.4k")
      (footprint "eagle-import:R1206")
      (fields (field (name "MF") "Yageo") (field (name "MPN") "RC1206JR-072K4L"))
      (libsource (lib "eagle-import") (part "R-EU_R1206"))
    )
    (comp (ref "R10")
      (value "2.4k")
      (footprint "eagle-import:R1206")
      (fields (field (name "MF") "Yageo") (field (name "MPN") "RC1206JR-072K4L"))
      (libsource (lib "eagle-import") (part "R-EU_R1206"))
    )
    (comp (ref "R11")
      (value "2.4k")
      (footprint "eagle-import:R1206")
      (fields (field (name "MF") "Yageo") (field (name "MPN") "RC1206JR-072K4L"))
      (libsource (lib "eagle-import") (part "R-EU_R1206"))
    )
    (comp (ref "R12")
      (value "2.4k")
      (footprint "eagle-import:R1206")
      (fields (field (name "MF") "Yageo") (field (name "MPN") "RC1206JR-072K4L"))
      (libsource (lib "eagle-import") (part "R-EU_R1206"))
    )
    (comp (ref "R13")
      (value "2.4k")
      (footprint "eagle-import:R1206")
      (fields (field (name "MF") "Yageo") (field (name "MPN") "RC1206JR-072K4L"))
      (libsource (lib "eagle-import") (part "R-EU_R1206"))
    )
    (comp (ref "R14")
      (value "2.4k")
      (footprint "eagle-import:R1206")
      (fields (field (name "MF") "Yageo") (field (name "MPN") "RC1206JR-072K4L"))
      (libsource (lib "eagle-import") (part "R-EU_R1206"))
    )
    (comp (ref "R15")
      (value "2.4k")
      (footprint "eagle-import:R1206")
      (fields (field (name "MF") "Yageo") (field (name "MPN") "RC1206JR-072K4L"))
      (libsource (lib "eagle-import") (part "R-EU_R1206"))
    )
    (comp (ref "R16")
      (value "2.4k")
      (footprint "eagle-import:R1206")
      (fields (field (name "MF") "Yageo") (field (name "MPN") "RC1206JR-072K4L"))
      (libsource (lib "eagle-import") (part "R-EU_R1206"))
    )
    (comp (ref "R17")
      (value "1.2k")
      (footprint "eagle-import:R0603")
      (fields (field (name "MF") "Yageo") (field (name "MPN") "RC0603FR-071K2L"))
      (libsource (lib "eagle-import") (part "R-EU_R0603"))
    )
    (comp (ref "R18")
      (value "1.2k")
      (footprint "eagle-import:R0603")
      (fields (field (name "MF") "Yageo") (field (name "MPN") "RC0603FR-071K2L"))
      (libsource (lib "eagle-import") (part "R-EU_R0603"))
    )
    (comp (ref "R19")
      (value "1.2k")
      (footprint "eagle-import:R0603")
      (fields (field (name "MF") "Yageo") (field (name "MPN") "RC0603FR-071K2L"))
      (libsource (lib "eagle-import") (part "R-EU_R0603"))
    )
    (comp (ref "R20")
      (value "1.2k")
      (footprint "eagle-import:R0603")
      (fields (field (name "MF") "Yageo") (field (name "MPN") "RC0603FR-071K2L"))
      (libsource (lib "eagle-import") (part "R-EU_R0603"))
    )
    (comp (ref "R21")
      (value "1.2k")
      (footprint "eagle-import:R0603")
      (fields (field (name "MF") "Yageo") (field (name "MPN") "RC0603FR-071K2L"))
      (libsource (lib "eagle-import") (part "R-EU_R0603"))
    )
    (comp (ref "R22")
      (value "1.2k")
      (footprint "eagle-import:R0603")
      (fields (field (name "MF") "Yageo") (field (name "MPN") "RC0603FR-071K2L"))
      (libsource (lib "eagle-import") (part "R-EU_R0603"))
    )
    (comp (ref "R23")
      (value "1.2k")
      (footprint "eagle-import:R0603")
      (fields (field (name "MF") "Yageo") (field (name "MPN") "RC0603FR-071K2L"))
      (libsource (lib "eagle-import") (part "R-EU_R0603"))
    )
    (comp (ref "R24")
      (value "1.2k")
      (footprint "eagle-import:R0603")
      (fields (field (name "MF") "Yageo") (field (name "MPN") "RC0603FR-071K2L"))
      (libsource (lib "eagle-import") (part "R-EU_R0603"))
    )
    (comp (ref "R25")
      (value "1.2k")
      (footprint "eagle-import:R0603")
      (fields (field (name "MF") "Yageo") (field (name "MPN") "RC0603FR-071K2L"))
      (libsource (lib "eagle-import") (part "R-EU_R0603"))
    )
    (comp (ref "R26")
      (value "22k")
      (footprint "eagle-import:R0603")
      (fields (field (name "MF") "Yageo") (field (name "MPN") "AC0603FR-0722K1L"))
      (libsource (lib "eagle-import") (part "R-EU_R0603"))
    )
    (comp (ref "R27")
      (value "1.2k")
      (footprint "eagle-import:R0603")
      (fields (field (name "MF") "Yageo") (field (name "MPN") "RC0603FR-071K2L"))
      (libsource (lib "eagle-import") (part "R-EU_R0603"))
    )
    (comp (ref "R28")
      (value "1.2k")
      (footprint "eagle-import:R0603")
      (fields (field (name "MF") "Yageo") (field (name "MPN") "RC0603FR-071K2L"))
      (libsource (lib "eagle-import") (part "R-EU_R0603"))
    )
    (comp (ref "R29")
      (value "1.2k")
      (footprint "eagle-import:R0603")
      (fields (field (name "MF") "Yageo") (field (name "MPN") "RC0603FR-071K2L"))
      (libsource (lib "eagle-import") (part "R-EU_R0603"))
    )
    (comp (ref "R30")
      (value "2K2")
      (footprint "eagle-import:R0603")
      (fields (field (name "MF") "Yageo") (field (name "MPN") "RC0603FR-072K2P"))
      (libsource (lib "eagle-import") (part "R-EU_R0603"))
    )
    (comp (ref "R31")
      (value "1K5")
      (footprint "eagle-import:R0603")
      (fields (field (name "MF") "Yageo") (field (name "MPN") "RC0603FR-071K5P"))
      (libsource (lib "eagle-import") (part "R-EU_R0603"))
    )
    (comp (ref "R32")
      (value "2K2")
      (footprint "eagle-import:R0603")
      (fields (field (name "MF") "Yageo") (field (name "MPN") "RC0603FR-072K2P"))
      (libsource (lib "eagle-import") (part "R-EU_R0603"))
    )
    (comp (ref "R33")
      (value "2K2")
      (footprint "eagle-import:R0603")
      (fields (field (name "MF") "Yageo") (field (name "MPN") "RC0603FR-072K2P"))
      (libsource (lib "eagle-import") (part "R-EU_R0603"))
    )
    (comp (ref "R34")
      (value "4K87, 1%")
      (footprint "eagle-import:R0603")
      (fields (field (name "MF") "Yageo") (field (name "MPN") "AC0603FR-074K87L"))
      (libsource (lib "eagle-import") (part "R-EU_R0603"))
    )
    (comp (ref "R35")
      (value "2K2")
      (footprint "eagle-import:R0603")
      (fields (field (name "MF") "Yageo") (field (name "MPN") "RC0603FR-072K2P"))
      (libsource (lib "eagle-import") (part "R-EU_R0603"))
    )
    (comp (ref "R36")
      (value "2K2")
      (footprint "eagle-import:R0603")
      (fields (field (name "MF") "Yageo") (field (name "MPN") "RC0603FR-072K2P"))
      (libsource (lib "eagle-import") (part "R-EU_R0603"))
    )
    (comp (ref "R37")
      (value "49.9R")
      (footprint "eagle-import:R0603")
      (fields (field (name "MF") "Bourns") (field (name "MPN") "CR0603-FX-49R9GLF"))
      (libsource (lib "eagle-import") (part "R-EU_R0603"))
    )
    (comp (ref "R38")
      (value "49.9R")
      (footprint "eagle-import:R0603")
      (fields (field (name "MF") "Bourns") (field (name "MPN") "CR0603-FX-49R9GLF"))
      (libsource (lib "eagle-import") (part "R-EU_R0603"))
    )
    (comp (ref "R39")
      (value "49.9R")
      (footprint "eagle-import:R0603")
      (fields (field (name "MF") "Bourns") (field (name "MPN") "CR0603-FX-49R9GLF"))
      (libsource (lib "eagle-import") (part "R-EU_R0603"))
    )
    (comp (ref "R40")
      (value "49.9R")
      (footprint "eagle-import:R0603")
      (fields (field (name "MF") "Bourns") (field (name "MPN") "CR0603-FX-49R9GLF"))
      (libsource (lib "eagle-import") (part "R-EU_R0603"))
    )
    (comp (ref "R41")
      (value "0R")
      (footprint "eagle-import:R0603")
      (fields (field (name "MF") "Yageo") (field (name "MPN") "RC0603JR-070RL"))
      (libsource (lib "eagle-import") (part "R-EU_R0603"))
    )
    (comp (ref "R42")
      (value "0R")
      (footprint "eagle-import:R0603")
      (fields (field (name "MF") "Yageo") (field (name "MPN") "RC0603JR-070RL"))
      (libsource (lib "eagle-import") (part "R-EU_R0603"))
    )
    (comp (ref "R43")
      (value "0R")
      (footprint "eagle-import:R0603")
      (fields (field (name "MF") "Yageo") (field (name "MPN") "RC0603JR-070RL"))
      (libsource (lib "eagle-import") (part "R-EU_R0603"))
    )
    (comp (ref "R44")
      (value "0R")
      (footprint "eagle-import:R0603")
      (fields (field (name "MF") "Yageo") (field (name "MPN") "RC0603JR-070RL"))
      (libsource (lib "eagle-import") (part "R-EU_R0603"))
    )
    (comp (ref "R45")
      (value "0R")
      (footprint "eagle-import:R0603")
      (fields (field (name "MF") "Yageo") (field (name "MPN") "RC0603JR-070RL"))
      (libsource (lib "eagle-import") (part "R-EU_R0603"))
    )
    (comp (ref "R46")
      (value "75R")
      (footprint "eagle-import:R0603")
      (fields (field (name "MF") "Yageo") (field (name "MPN") "RC0603JR-0775RL"))
      (libsource (lib "eagle-import") (part "R-EU_R0603"))
    )
    (comp (ref "R47")
      (value "75R")
      (footprint "eagle-import:R0603")
      (fields (field (name "MF") "Yageo") (field (name "MPN") "RC0603JR-0775RL"))
      (libsource (lib "eagle-import") (part "R-EU_R0603"))
    )
    (comp (ref "R48")
      (value "75R")
      (footprint "eagle-import:R0603")
      (fields (field (name "MF") "Yageo") (field (name "MPN") "RC0603JR-0775RL"))
      (libsource (lib "eagle-import") (part "R-EU_R0603"))
    )
    (comp (ref "R49")
      (value "75R")
      (footprint "eagle-import:R0603")
      (fields (field (name "MF") "Yageo") (field (name "MPN") "RC0603JR-0775RL"))
      (libsource (lib "eagle-import") (part "R-EU_R0603"))
    )
    (comp (ref "R50")
      (value "110R")
      (footprint "eagle-import:R0603")
      (fields (field (name "MF") "Yageo") (field (name "MPN") "RC0603FR-07110RL"))
      (libsource (lib "eagle-import") (part "R-EU_R0603"))
    )
    (comp (ref "R51")
      (value "2K2")
      (footprint "eagle-import:R0603")
      (fields (field (name "MF") "Yageo") (field (name "MPN") "RC0603FR-072K2P"))
      (libsource (lib "eagle-import") (part "R-EU_R0603"))
    )
    (comp (ref "R52")
      (value "110R")
      (footprint "eagle-import:R0603")
      (fields (field (name "MF") "Yageo") (field (name "MPN") "RC0603FR-07110RL"))
      (libsource (lib "eagle-import") (part "R-EU_R0603"))
    )
    (comp (ref "R53")
      (value "2K2")
      (footprint "eagle-import:R0603")
      (fields (field (name "MF") "Yageo") (field (name "MPN") "RC0603FR-072K2P"))
      (libsource (lib "eagle-import") (part "R-EU_R0603"))
    )
    (comp (ref "R54")
      (value "1.2k")
      (footprint "eagle-import:R0603")
      (fields (field (name "MF") "Yageo") (field (name "MPN") "RC0603FR-071K2L"))
      (libsource (lib "eagle-import") (part "R-EU_R0603"))
    )
    (comp (ref "R55")
      (value "1.2k")
      (footprint "eagle-import:R0603")
      (fields (field (name "MF") "Yageo") (field (name "MPN") "RC0603FR-071K2L"))
      (libsource (lib "eagle-import") (part "R-EU_R0603"))
    )
    (comp (ref "R56")
      (value "1.2k")
      (footprint "eagle-import:R0603")
      (fields (field (name "MF") "Yageo") (field (name "MPN") "RC0603FR-071K2L"))
      (libsource (lib "eagle-import") (part "R-EU_R0603"))
    )
    (comp (ref "R57")
      (value "1.2k")
      (footprint "eagle-import:R0603")
      (fields (field (name "MF") "Yageo") (field (name "MPN") "RC0603FR-071K2L"))
      (libsource (lib "eagle-import") (part "R-EU_R0603"))
    )
    (comp (ref "R58")
      (value "1.2k")
      (footprint "eagle-import:R0603")
      (fields (field (name "MF") "Yageo") (field (name "MPN") "RC0603FR-071K2L"))
      (libsource (lib "eagle-import") (part "R-EU_R0603"))
    )
    (comp (ref "R59")
      (value "1.2k")
      (footprint "eagle-import:R0603")
      (fields (field (name "MF") "Yageo") (field (name "MPN") "RC0603FR-071K2L"))
      (libsource (lib "eagle-import") (part "R-EU_R0603"))
    )
    (comp (ref "R60")
      (value "1.2k")
      (footprint "eagle-import:R0603")
      (fields (field (name "MF") "Yageo") (field (name "MPN") "RC0603FR-071K2L"))
      (libsource (lib "eagle-import") (part "R-EU_R0603"))
    )
    (comp (ref "R61")
      (value "1.2k")
      (footprint "eagle-import:R0603")
      (fields (field (name "MF") "Yageo") (field (name "MPN") "RC0603FR-071K2L"))
      (libsource (lib "eagle-import") (part "R-EU_R0603"))
    )
    (comp (ref "R62")
      (value "33R")
      (footprint "eagle-import:R0603")
      (fields (field (name "MF") "Yageo") (field (name "MPN") "RC0603FR-071K2L"))
      (libsource (lib "eagle-import") (part "R-EU_R0603"))
    )
    (comp (ref "R63")
      (value "33R")
      (footprint "eagle-import:R0603")
      (fields (field (name "MF") "Yageo") (field (name "MPN") "RC0603FR-071K2L"))
      (libsource (lib "eagle-import") (part "R-EU_R0603"))
    )
    (comp (ref "R64")
      (value "33R")
      (footprint "eagle-import:R0603")
      (fields (field (name "MF") "Yageo") (field (name "MPN") "RC0603FR-071K2L"))
      (libsource (lib "eagle-import") (part "R-EU_R0603"))
    )
    (comp (ref "R65")
      (value "33R")
      (footprint "eagle-import:R0603")
      (fields (field (name "MF") "Yageo") (field (name "MPN") "RC0603FR-071K2L"))
      (libsource (lib "eagle-import") (part "R-EU_R0603"))
    )
    (comp (ref "R66")
      (value "33R")
      (footprint "eagle-import:R0603")
      (fields (field (name "MF") "Yageo") (field (name "MPN") "RC0603FR-071K2L"))
      (libsource (lib "eagle-import") (part "R-EU_R0603"))
    )
    (comp (ref "R67")
      (value "33R")
      (footprint "eagle-import:R0603")
      (fields (field (name "MF") "Yageo") (field (name "MPN") "RC0603FR-071K2L"))
      (libsource (lib "eagle-import") (part "R-EU_R0603"))
    )
    (comp (ref "R68")
      (value "33R")
      (footprint "eagle-import:R0603")
      (fields (field (name "MF") "Yageo") (field (name "MPN") "RC0603FR-071K2L"))
      (libsource (lib "eagle-import") (part "R-EU_R0603"))
    )
    (comp (ref "R69")
      (value "33R")
      (footprint "eagle-import:R0603")
      (fields (field (name "MF") "Yageo") (field (name "MPN") "RC0603FR-071K2L"))
      (libsource (lib "eagle-import") (part "R-EU_R0603"))
    )
    (comp (ref "R70")
      (value "33R")
      (footprint "eagle-import:R0603")
      (fields (field (name "MF") "Yageo") (field (name "MPN") "RC0603FR-071K2L"))
      (libsource (lib "eagle-import") (part "R-EU_R0603"))
    )
    (comp (ref "R71")
      (value "33R")
      (footprint "eagle-import:R0603")
      (fields (field (name "MF") "Yageo") (field (name "MPN") "RC0603FR-071K2L"))
      (libsource (lib "eagle-import") (part "R-EU_R0603"))
    )
    (comp (ref "R72")
      (value "33R")
      (footprint "eagle-import:R0603")
      (fields (field (name "MF") "Yageo") (field (name "MPN") "RC0603FR-071K2L"))
      (libsource (lib "eagle-import") (part "R-EU_R0603"))
    )
    (comp (ref "R73")
      (value "33R")
      (footprint "eagle-import:R0603")
      (fields (field (name "MF") "Yageo") (field (name "MPN") "RC0603FR-071K2L"))
      (libsource (lib "eagle-import") (part "R-EU_R0603"))
    )
    (comp (ref "R74")
      (value "33R")
      (footprint "eagle-import:R0603")
      (fields (field (name "MF") "Yageo") (field (name "MPN") "RC0603FR-071K2L"))
      (libsource (lib "eagle-import") (part "R-EU_R0603"))
    )
    (comp (ref "R75")
      (value "33R")
      (footprint "eagle-import:R0603")
      (fields (field (name "MF") "Yageo") (field (name "MPN") "RC0603FR-071K2L"))
      (libsource (lib "eagle-import") (part "R-EU_R0603"))
    )
    (comp (ref "R76")
      (value "33R")
      (footprint "eagle-import:R0603")
      (fields (field (name "MF") "Yageo") (field (name "MPN") "RC0603FR-071K2L"))
      (libsource (lib "eagle-import") (part "R-EU_R0603"))
    )
    (comp (ref "R77")
      (value "33R")
      (footprint "eagle-import:R0603")
      (fields (field (name "MF") "Yageo") (field (name "MPN") "RC0603FR-071K2L"))
      (libsource (lib "eagle-import") (part "R-EU_R0603"))
    )
    (comp (ref "R78")
      (value "33R")
      (footprint "eagle-import:R0603")
      (fields (field (name "MF") "Yageo") (field (name "MPN") "RC0603FR-071K2L"))
      (libsource (lib "eagle-import") (part "R-EU_R0603"))
    )
    (comp (ref "R79")
      (value "300R")
      (footprint "eagle-import:R0603")
      (fields (field (name "MF") "Yageo") (field (name "MPN") "AC0603FR-07300RL"))
      (libsource (lib "eagle-import") (part "R-EU_R0603"))
    )
    (comp (ref "R80")
      (value "300R")
      (footprint "eagle-import:R0603")
      (fields (field (name "MF") "Yageo") (field (name "MPN") "AC0603FR-07300RL"))
      (libsource (lib "eagle-import") (part "R-EU_R0603"))
    )
    (comp (ref "R81")
      (value "300R")
      (footprint "eagle-import:R0603")
      (fields (field (name "MF") "Yageo") (field (name "MPN") "AC0603FR-07300RL"))
      (libsource (lib "eagle-import") (part "R-EU_R0603"))
    )
    (comp (ref "R82")
      (value "300R")
      (footprint "eagle-import:R0603")
      (fields (field (name "MF") "Yageo") (field (name "MPN") "AC0603FR-07300RL"))
      (libsource (lib "eagle-import") (part "R-EU_R0603"))
    )
    (comp (ref "R83")
      (value "523R")
      (footprint "eagle-import:R0603")
      (fields (field (name "MF") "Yageo") (field (name "MPN") "RC0603FR-07523RL"))
      (libsource (lib "eagle-import") (part "R-EU_R0603"))
    )
    (comp (ref "R84")
      (value "523R")
      (footprint "eagle-import:R0603")
      (fields (field (name "MF") "Yageo") (field (name "MPN") "RC0603FR-07523RL"))
      (libsource (lib "eagle-import") (part "R-EU_R0603"))
    )
    (comp (ref "R85")
      (value "523R")
      (footprint "eagle-import:R0603")
      (fields (field (name "MF") "Yageo") (field (name "MPN") "RC0603FR-07523RL"))
      (libsource (lib "eagle-import") (part "R-EU_R0603"))
    )
    (comp (ref "R86")
      (value "523R")
      (footprint "eagle-import:R0603")
      (fields (field (name "MF") "Yageo") (field (name "MPN") "RC0603FR-07523RL"))
      (libsource (lib "eagle-import") (part "R-EU_R0603"))
    )
    (comp (ref "R87")
      (value "210R")
      (footprint "eagle-import:R0603")
      (fields (field (name "MF") "Bourns") (field (name "MPN") "CR0603-FX-2100ELF"))
      (libsource (lib "eagle-import") (part "R-EU_R0603"))
    )
    (comp (ref "R88")
      (value "210R")
      (footprint "eagle-import:R0603")
      (fields (field (name "MF") "Bourns") (field (name "MPN") "CR0603-FX-2100ELF"))
      (libsource (lib "eagle-import") (part "R-EU_R0603"))
    )
    (comp (ref "R89")
      (value "210R")
      (footprint "eagle-import:R0603")
      (fields (field (name "MF") "Bourns") (field (name "MPN") "CR0603-FX-2100ELF"))
      (libsource (lib "eagle-import") (part "R-EU_R0603"))
    )
    (comp (ref "R90")
      (value "210R")
      (footprint "eagle-import:R0603")
      (fields (field (name "MF") "Bourns") (field (name "MPN") "CR0603-FX-2100ELF"))
      (libsource (lib "eagle-import") (part "R-EU_R0603"))
    )
    (comp (ref "R91")
      (value "2k7")
      (footprint "eagle-import:R0603")
      (fields (field (name "MF") "Yageo") (field (name "MPN") "RC0603JR-072K7L"))
      (libsource (lib "eagle-import") (part "R-EU_R0603"))
    )
    (comp (ref "R92")
      (value "2k7")
      (footprint "eagle-import:R0603")
      (fields (field (name "MF") "Yageo") (field (name "MPN") "RC0603JR-072K7L"))
      (libsource (lib "eagle-import") (part "R-EU_R0603"))
    )
    (comp (ref "R93")
      (value "2k7")
      (footprint "eagle-import:R0603")
      (fields (field (name "MF") "Yageo") (field (name "MPN") "RC0603JR-072K7L"))
      (libsource (lib "eagle-import") (part "R-EU_R0603"))
    )
    (comp (ref "R94")
      (value "2k7")
      (footprint "eagle-import:R0603")
      (fields (field (name "MF") "Yageo") (field (name "MPN") "RC0603JR-072K7L"))
      (libsource (lib "eagle-import") (part "R-EU_R0603"))
    )
    (comp (ref "R95")
      (value "210R")
      (footprint "eagle-import:R0603")
      (fields (field (name "MF") "Bourns") (field (name "MPN") "CR0603-FX-2100ELF"))
      (libsource (lib "eagle-import") (part "R-EU_R0603"))
    )
    (comp (ref "R96")
      (value "210R")
      (footprint "eagle-import:R0603")
      (fields (field (name "MF") "Bourns") (field (name "MPN") "CR0603-FX-2100ELF"))
      (libsource (lib "eagle-import") (part "R-EU_R0603"))
    )
    (comp (ref "R97")
      (value "210R")
      (footprint "eagle-import:R0603")
      (fields (field (name "MF") "Bourns") (field (name "MPN") "CR0603-FX-2100ELF"))
      (libsource (lib "eagle-import") (part "R-EU_R0603"))
    )
    (comp (ref "R98")
      (value "210R")
      (footprint "eagle-import:R0603")
      (fields (field (name "MF") "Bourns") (field (name "MPN") "CR0603-FX-2100ELF"))
      (libsource (lib "eagle-import") (part "R-EU_R0603"))
    )
    (comp (ref "R99")
      (value "2k7")
      (footprint "eagle-import:R0603")
      (fields (field (name "MF") "Yageo") (field (name "MPN") "RC0603JR-072K7L"))
      (libsource (lib "eagle-import") (part "R-EU_R0603"))
    )
    (comp (ref "R100")
      (value "2k7")
      (footprint "eagle-import:R0603")
      (fields (field (name "MF") "Yageo") (field (name "MPN") "RC0603JR-072K7L"))
      (libsource (lib "eagle-import") (part "R-EU_R0603"))
    )
    (comp (ref "R101")
      (value "2k7")
      (footprint "eagle-import:R0603")
      (fields (field (name "MF") "Yageo") (field (name "MPN") "RC0603JR-072K7L"))
      (libsource (lib "eagle-import") (part "R-EU_R0603"))
    )
    (comp (ref "R102")
      (value "2k7")
      (footprint "eagle-import:R0603")
      (fields (field (name "MF") "Yageo") (field (name "MPN") "RC0603JR-072K7L"))
      (libsource (lib "eagle-import") (part "R-EU_R0603"))
    )
    (comp (ref "R103")
      (value "300R")
      (footprint "eagle-import:R0603")
      (fields (field (name "MF") "Yageo") (field (name "MPN") "AC0603FR-07300RL"))
      (libsource (lib "eagle-import") (part "R-EU_R0603"))
    )
    (comp (ref "R104")
      (value "300R")
      (footprint "eagle-import:R0603")
      (fields (field (name "MF") "Yageo") (field (name "MPN") "AC0603FR-07300RL"))
      (libsource (lib "eagle-import") (part "R-EU_R0603"))
    )
    (comp (ref "R105")
      (value "300R")
      (footprint "eagle-import:R0603")
      (fields (field (name "MF") "Yageo") (field (name "MPN") "AC0603FR-07300RL"))
      (libsource (lib "eagle-import") (part "R-EU_R0603"))
    )
    (comp (ref "R106")
      (value "300R")
      (footprint "eagle-import:R0603")
      (fields (field (name "MF") "Yageo") (field (name "MPN") "AC0603FR-07300RL"))
      (libsource (lib "eagle-import") (part "R-EU_R0603"))
    )
    (comp (ref "R107")
      (value "523R")
      (footprint "eagle-import:R0603")
      (fields (field (name "MF") "Yageo") (field (name "MPN") "RC0603FR-07523RL"))
      (libsource (lib "eagle-import") (part "R-EU_R0603"))
    )
    (comp (ref "R108")
      (value "523R")
      (footprint "eagle-import:R0603")
      (fields (field (name "MF") "Yageo") (field (name "MPN") "RC0603FR-07523RL"))
      (libsource (lib "eagle-import") (part "R-EU_R0603"))
    )
    (comp (ref "R109")
      (value "523R")
      (footprint "eagle-import:R0603")
      (fields (field (name "MF") "Yageo") (field (name "MPN") "RC0603FR-07523RL"))
      (libsource (lib "eagle-import") (part "R-EU_R0603"))
    )
    (comp (ref "R110")
      (value "523R")
      (footprint "eagle-import:R0603")
      (fields (field (name "MF") "Yageo") (field (name "MPN") "RC0603FR-07523RL"))
      (libsource (lib "eagle-import") (part "R-EU_R0603"))
    )
    (comp (ref "R111")
      (value "191k")
      (footprint "eagle-import:R0603")
      (fields (field (name "MF") "Yageo") (field (name "MPN") "AC0603FR-07191KL"))
      (libsource (lib "eagle-import") (part "R-EU_R0603"))
    )
    (comp (ref "R112")
      (value "22k1")
      (footprint "eagle-import:R0603")
      (fields (field (name "MF") "Yageo") (field (name "MPN") "AC0603FR-0722K1L"))
      (libsource (lib "eagle-import") (part "R-EU_R0603"))
    )
    (comp (ref "R113")
      (value "261k")
      (footprint "eagle-import:R0603")
      (fields (field (name "MF") "Bourns") (field (name "MPN") "CR0603-FX-2613ELF"))
      (libsource (lib "eagle-import") (part "R-EU_R0603"))
    )
    (comp (ref "R114")
      (value "49k9")
      (footprint "eagle-import:R0603")
      (fields (field (name "MF") "Vishay") (field (name "MPN") "CRCW060349K9FKEB"))
      (libsource (lib "eagle-import") (part "R-EU_R0603"))
    )
    (comp (ref "R115")
      (value "191k")
      (footprint "eagle-import:R0603")
      (fields (field (name "MF") "Yageo") (field (name "MPN") "AC0603FR-07191KL"))
      (libsource (lib "eagle-import") (part "R-EU_R0603"))
    )
    (comp (ref "R116")
      (value "22k1")
      (footprint "eagle-import:R0603")
      (fields (field (name "MF") "Yageo") (field (name "MPN") "AC0603FR-0722K1L"))
      (libsource (lib "eagle-import") (part "R-EU_R0603"))
    )
    (comp (ref "R117")
      (value "261k")
      (footprint "eagle-import:R0603")
      (fields (field (name "MF") "Bourns") (field (name "MPN") "CR0603-FX-2613ELF"))
      (libsource (lib "eagle-import") (part "R-EU_R0603"))
    )
    (comp (ref "R118")
      (value "49k9")
      (footprint "eagle-import:R0603")
      (fields (field (name "MF") "Vishay") (field (name "MPN") "CRCW060349K9FKEB"))
      (libsource (lib "eagle-import") (part "R-EU_R0603"))
    )
    (comp (ref "S1")
      (value "DTSM-6")
      (footprint "eagle-import:DTSM-6")
      (fields (field (name "MF") "DIPTRONICS") (field (name "MPN") "DTSM-63N-V-B"))
      (libsource (lib "eagle-import") (part "DTSM-6"))
    )
    (comp (ref "SV1")
      (value "ML10")
      (footprint "eagle-import:ML10")
      (fields (field (name "MF") "Wurth Electronics") (field (name "MPN") "61201021621"))
      (libsource (lib "eagle-import") (part "ML10"))
    )
    (comp (ref "T1")
      (value "H1102NL")
      (footprint "eagle-import:HXXXX")
      (fields (field (name "MF") "PULSE"))
      (libsource (lib "eagle-import") (part "HX1188"))
    )
    (comp (ref "X1")
      (value "MKDSN1,5/2-5,08")
      (footprint "eagle-import:MKDSN1,5_2-5,08")
      (fields (field (name "MF") "NINIGI") (field (name "MPN") "TB-5.08-P-2P/BL"))
      (libsource (lib "eagle-import") (part "MKDSN1,5/2-5,08"))
    )
    (comp (ref "X2")
      (value "MKDSN1,5/2-5,08")
      (footprint "eagle-import:MKDSN1,5_2-5,08")
      (fields (field (name "MF") "NINIGI") (field (name "MPN") "TB-5.08-P-2P/BL"))
      (libsource (lib "eagle-import") (part "MKDSN1,5/2-5,08"))
    )
    (comp (ref "X3")
      (value "MKDSN1,5/2-5,08")
      (footprint "eagle-import:MKDSN1,5_2-5,08")
      (fields (field (name "MF") "NINIGI") (field (name "MPN") "TB-5.08-P-2P/BL"))
      (libsource (lib "eagle-import") (part "MKDSN1,5/2-5,08"))
    )
    (comp (ref "X4")
      (value "MKDSN1,5/2-5,08")
      (footprint "eagle-import:MKDSN1,5_2-5,08")
      (fields (field (name "MF") "NINIGI") (field (name "MPN") "TB-5.08-P-2P/BL"))
      (libsource (lib "eagle-import") (part "MKDSN1,5/2-5,08"))
    )
    (comp (ref "X5")
      (value "MKDSN1,5/2-5,08")
      (footprint "eagle-import:MKDSN1,5_2-5,08")
      (fields (field (name "MF") "NINIGI") (field (name "MPN") "TB-5.08-P-2P/BL"))
      (libsource (lib "eagle-import") (part "MKDSN1,5/2-5,08"))
    )
    (comp (ref "X6")
      (value "MKDSN1,5/2-5,08")
      (footprint "eagle-import:MKDSN1,5_2-5,08")
      (fields (field (name "MF") "NINIGI") (field (name "MPN") "TB-5.08-P-2P/BL"))
      (libsource (lib "eagle-import") (part "MKDSN1,5/2-5,08"))
    )
    (comp (ref "X7")
      (value "MKDSN1,5/2-5,08")
      (footprint "eagle-import:MKDSN1,5_2-5,08")
      (fields (field (name "MF") "NINIGI") (field (name "MPN") "TB-5.08-P-2P/BL"))
      (libsource (lib "eagle-import") (part "MKDSN1,5/2-5,08"))
    )
    (comp (ref "X8")
      (value "MKDSN1,5/2-5,08")
      (footprint "eagle-import:MKDSN1,5_2-5,08")
      (fields (field (name "MF") "NINIGI") (field (name "MPN") "TB-5.08-P-2P/BL"))
      (libsource (lib "eagle-import") (part "MKDSN1,5/2-5,08"))
    )
    (comp (ref "X9")
      (value "MKDSN1,5/2-5,08")
      (footprint "eagle-import:MKDSN1,5_2-5,08")
      (fields (field (name "MF") "NINIGI") (field (name "MPN") "TB-5.08-P-2P/BL"))
      (libsource (lib "eagle-import") (part "MKDSN1,5/2-5,08"))
    )
    (comp (ref "X10")
      (value "MKDSN1,5/2-5,08")
      (footprint "eagle-import:MKDSN1,5_2-5,08")
      (fields (field (name "MF") "NINIGI") (field (name "MPN") "TB-5.08-P-2P/BL"))
      (libsource (lib "eagle-import") (part "MKDSN1,5/2-5,08"))
    )
    (comp (ref "X11")
      (value "MKDSN1,5/2-5,08")
      (footprint "eagle-import:MKDSN1,5_2-5,08")
      (fields (field (name "MF") "NINIGI") (field (name "MPN") "TB-5.08-P-2P/BL"))
      (libsource (lib "eagle-import") (part "MKDSN1,5/2-5,08"))
    )
  )
  (nets
    (net (code "1") (name "+3V3") (class "Default")
      (node (ref "C10") (pin "1") (pinfunction "1_1") (pintype "passive"))
      (node (ref "C15") (pin "1") (pinfunction "1_1") (pintype "passive"))
      (node (ref "C16") (pin "1") (pinfunction "1_1") (pintype "passive"))
      (node (ref "C17") (pin "1") (pinfunction "1_1") (pintype "passive"))
      (node (ref "C18") (pin "1") (pinfunction "1_1") (pintype "passive"))
      (node (ref "C19") (pin "1") (pinfunction "1_1") (pintype "passive"))
      (node (ref "C20") (pin "1") (pinfunction "1_1") (pintype "passive"))
      (node (ref "C22") (pin "1") (pinfunction "1_1") (pintype "passive"))
      (node (ref "C23") (pin "1") (pinfunction "1_1") (pintype "passive"))
      (node (ref "C24") (pin "1") (pinfunction "1_1") (pintype "passive"))
      (node (ref "C26") (pin "1") (pinfunction "1_1") (pintype "passive"))
      (node (ref "C28") (pin "1") (pinfunction "1_1") (pintype "passive"))
      (node (ref "C29") (pin "1") (pinfunction "1_1") (pintype "passive"))
      (node (ref "C31") (pin "1") (pinfunction "1_1") (pintype "passive"))
      (node (ref "C33") (pin "1") (pinfunction "1_1") (pintype "passive"))
      (node (ref "C34") (pin "1") (pinfunction "1_1") (pintype "passive"))
      (node (ref "C35") (pin "1") (pinfunction "1_1") (pintype "passive"))
      (node (ref "C37") (pin "1") (pinfunction "1_1") (pintype "passive"))
      (node (ref "C41") (pin "1") (pinfunction "1_1") (pintype "passive"))
      (node (ref "C9") (pin "1") (pinfunction "1_1") (pintype "passive"))
      (node (ref "D1") (pin "5") (pinfunction "VBUS_5") (pintype "output"))
      (node (ref "IC1") (pin "16") (pinfunction "VDD_16") (pintype "bidirectional"))
      (node (ref "IC2") (pin "108") (pinfunction "VDD_108") (pintype "bidirectional"))
      (node (ref "IC2") (pin "121") (pinfunction "VDD_121") (pintype "bidirectional"))
      (node (ref "IC2") (pin "131") (pinfunction "VDD_131") (pintype "bidirectional"))
      (node (ref "IC2") (pin "143") (pinfunction "PDR_ON_143") (pintype "bidirectional"))
      (node (ref "IC2") (pin "144") (pinfunction "VDD_144") (pintype "bidirectional"))
      (node (ref "IC2") (pin "17") (pinfunction "VDD_17") (pintype "bidirectional"))
      (node (ref "IC2") (pin "30") (pinfunction "VDD_30") (pintype "bidirectional"))
      (node (ref "IC2") (pin "39") (pinfunction "VDD_39") (pintype "bidirectional"))
      (node (ref "IC2") (pin "52") (pinfunction "VDD_52") (pintype "bidirectional"))
      (node (ref "IC2") (pin "62") (pinfunction "VDD_62") (pintype "bidirectional"))
      (node (ref "IC2") (pin "72") (pinfunction "VDD_72") (pintype "bidirectional"))
      (node (ref "IC2") (pin "84") (pinfunction "VDD_84") (pintype "bidirectional"))
      (node (ref "IC2") (pin "95") (pinfunction "VDD_95") (pintype "bidirectional"))
      (node (ref "IC3") (pin "22") (pinfunction "AVDD_22") (pintype "power_in"))
      (node (ref "IC3") (pin "32") (pinfunction "IOVDD1_32") (pintype "power_in"))
      (node (ref "IC3") (pin "48") (pinfunction "IOVDD2_48") (pintype "power_in"))
      (node (ref "JP1") (pin "1") (pinfunction "1_1") (pintype "passive"))
      (node (ref "JP1") (pin "2") (pinfunction "2_2") (pintype "passive"))
      (node (ref "JP3") (pin "1") (pinfunction "1_1") (pintype "passive"))
      (node (ref "L1") (pin "2") (pinfunction "2_2") (pintype "passive"))
      (node (ref "LED11") (pin "1") (pinfunction "A_1") (pintype "passive"))
      (node (ref "OS1") (pin "4") (pinfunction "VDD_4") (pintype "power_in"))
      (node (ref "R25") (pin "1") (pinfunction "1_1") (pintype "passive"))
      (node (ref "R30") (pin "2") (pinfunction "2_2") (pintype "passive"))
      (node (ref "R31") (pin "1") (pinfunction "1_1") (pintype "passive"))
      (node (ref "R33") (pin "2") (pinfunction "2_2") (pintype "passive"))
      (node (ref "R35") (pin "2") (pinfunction "2_2") (pintype "passive"))
      (node (ref "R36") (pin "2") (pinfunction "2_2") (pintype "passive"))
      (node (ref "R37") (pin "2") (pinfunction "2_2") (pintype "passive"))
      (node (ref "R38") (pin "2") (pinfunction "2_2") (pintype "passive"))
      (node (ref "R39") (pin "2") (pinfunction "2_2") (pintype "passive"))
      (node (ref "R40") (pin "2") (pinfunction "2_2") (pintype "passive"))
      (node (ref "R45") (pin "2") (pinfunction "2_2") (pintype "passive"))
      (node (ref "R50") (pin "2") (pinfunction "2_2") (pintype "passive"))
      (node (ref "R51") (pin "2") (pinfunction "2_2") (pintype "passive"))
      (node (ref "R52") (pin "2") (pinfunction "2_2") (pintype "passive"))
      (node (ref "R53") (pin "2") (pinfunction "2_2") (pintype "passive"))
      (node (ref "R87") (pin "1") (pinfunction "1_1") (pintype "passive"))
      (node (ref "R88") (pin "1") (pinfunction "1_1") (pintype "passive"))
      (node (ref "R89") (pin "1") (pinfunction "1_1") (pintype "passive"))
      (node (ref "R90") (pin "1") (pinfunction "1_1") (pintype "passive"))
      (node (ref "R95") (pin "1") (pinfunction "1_1") (pintype "passive"))
      (node (ref "R96") (pin "1") (pinfunction "1_1") (pintype "passive"))
      (node (ref "R97") (pin "1") (pinfunction "1_1") (pintype "passive"))
      (node (ref "R98") (pin "1") (pinfunction "1_1") (pintype "passive"))
    )
    (net (code "2") (name "+24V") (class "Default")
      (node (ref "JP1") (pin "11") (pinfunction "11_11") (pintype "passive"))
      (node (ref "JP1") (pin "12") (pinfunction "12_12") (pintype "passive"))
      (node (ref "R26") (pin "1") (pinfunction "1_1") (pintype "passive"))
    )
    (net (code "3") (name "5-24V1") (class "Default")
      (node (ref "C49") (pin "1") (pinfunction "1_1") (pintype "passive"))
      (node (ref "IC4") (pin "1") (pinfunction "IN_1") (pintype "power_in"))
      (node (ref "IC4") (pin "2") (pinfunction "EN/UVLO_2") (pintype "input"))
      (node (ref "Q3") (pin "9") (pinfunction "VS_9") (pintype "passive"))
      (node (ref "X4") (pin "2") (pinfunction "KL_2") (pintype "passive"))
    )
    (net (code "4") (name "5-24V2") (class "Default")
      (node (ref "C52") (pin "1") (pinfunction "1_1") (pintype "passive"))
      (node (ref "IC5") (pin "1") (pinfunction "IN_1") (pintype "power_in"))
      (node (ref "IC5") (pin "2") (pinfunction "EN/UVLO_2") (pintype "input"))
      (node (ref "Q4") (pin "9") (pinfunction "VS_9") (pintype "passive"))
      (node (ref "X7") (pin "2") (pinfunction "KL_2") (pintype "passive"))
    )
    (net (code "5") (name "5V1") (class "Default")
      (node (ref "C46") (pin "1") (pinfunction "1_1") (pintype "passive"))
      (node (ref "C47") (pin "1") (pinfunction "1_1") (pintype "passive"))
      (node (ref "C50") (pin "1") (pinfunction "1_1") (pintype "passive"))
      (node (ref "L3") (pin "2") (pinfunction "2_2") (pintype "passive"))
      (node (ref "OK1") (pin "8") (pinfunction "VCC_8") (pintype "passive"))
      (node (ref "OK2") (pin "8") (pinfunction "VCC_8") (pintype "passive"))
      (node (ref "R112") (pin "2") (pinfunction "2_2") (pintype "passive"))
      (node (ref "R113") (pin "2") (pinfunction "2_2") (pintype "passive"))
      (node (ref "R83") (pin "2") (pinfunction "2_2") (pintype "passive"))
      (node (ref "R84") (pin "2") (pinfunction "2_2") (pintype "passive"))
      (node (ref "R85") (pin "2") (pinfunction "2_2") (pintype "passive"))
      (node (ref "R86") (pin "2") (pinfunction "2_2") (pintype "passive"))
    )
    (net (code "6") (name "5V2") (class "Default")
      (node (ref "C53") (pin "1") (pinfunction "1_1") (pintype "passive"))
      (node (ref "L2") (pin "2") (pinfunction "2_2") (pintype "passive"))
      (node (ref "R107") (pin "2") (pinfunction "2_2") (pintype "passive"))
      (node (ref "R108") (pin "2") (pinfunction "2_2") (pintype "passive"))
      (node (ref "R109") (pin "2") (pinfunction "2_2") (pintype "passive"))
      (node (ref "R110") (pin "2") (pinfunction "2_2") (pintype "passive"))
      (node (ref "R116") (pin "2") (pinfunction "2_2") (pintype "passive"))
      (node (ref "R117") (pin "2") (pinfunction "2_2") (pintype "passive"))
    )
    (net (code "7") (name "AVDD") (class "Default")
      (node (ref "C32") (pin "1") (pinfunction "1_1") (pintype "passive"))
      (node (ref "IC2") (pin "32") (pinfunction "VREF+_32") (pintype "bidirectional"))
      (node (ref "IC2") (pin "33") (pinfunction "VDDA_33") (pintype "bidirectional"))
      (node (ref "L1") (pin "1") (pinfunction "1_1") (pintype "passive"))
    )
    (net (code "8") (name "COM") (class "Default")
      (node (ref "C1") (pin "2") (pinfunction "2_2") (pintype "passive"))
      (node (ref "C2") (pin "2") (pinfunction "2_2") (pintype "passive"))
      (node (ref "C3") (pin "2") (pinfunction "2_2") (pintype "passive"))
      (node (ref "C4") (pin "2") (pinfunction "2_2") (pintype "passive"))
      (node (ref "C5") (pin "2") (pinfunction "2_2") (pintype "passive"))
      (node (ref "C6") (pin "2") (pinfunction "2_2") (pintype "passive"))
      (node (ref "C7") (pin "2") (pinfunction "2_2") (pintype "passive"))
      (node (ref "C8") (pin "2") (pinfunction "2_2") (pintype "passive"))
      (node (ref "IC1") (pin "5") (pinfunction "COM_5") (pintype "bidirectional"))
      (node (ref "IC1") (pin "6") (pinfunction "COM_6") (pintype "bidirectional"))
      (node (ref "R10") (pin "1") (pinfunction "1_1") (pintype "passive"))
      (node (ref "R11") (pin "1") (pinfunction "1_1") (pintype "passive"))
      (node (ref "R12") (pin "1") (pinfunction "1_1") (pintype "passive"))
      (node (ref "R13") (pin "1") (pinfunction "1_1") (pintype "passive"))
      (node (ref "R14") (pin "1") (pinfunction "1_1") (pintype "passive"))
      (node (ref "R15") (pin "1") (pinfunction "1_1") (pintype "passive"))
      (node (ref "R16") (pin "1") (pinfunction "1_1") (pintype "passive"))
      (node (ref "R9") (pin "1") (pinfunction "1_1") (pintype "passive"))
      (node (ref "X1") (pin "1") (pinfunction "KL_1") (pintype "passive"))
      (node (ref "X11") (pin "2") (pinfunction "KL_2") (pintype "passive"))
    )
    (net (code "9") (name "CS_AI1_4") (class "Default")
      (node (ref "IC2") (pin "88") (pinfunction "PG3_88") (pintype "bidirectional"))
      (node (ref "R67") (pin "1") (pinfunction "1_1") (pintype "passive"))
    )
    (net (code "10") (name "CS_AI1_8") (class "Default")
      (node (ref "IC2") (pin "89") (pinfunction "PG4_89") (pintype "bidirectional"))
      (node (ref "R75") (pin "2") (pinfunction "2_2") (pintype "passive"))
    )
    (net (code "11") (name "CS_AI2_4") (class "Default")
      (node (ref "IC2") (pin "90") (pinfunction "PG5_90") (pintype "bidirectional"))
      (node (ref "R74") (pin "2") (pinfunction "2_2") (pintype "passive"))
    )
    (net (code "12") (name "CS_AI2_8") (class "Default")
      (node (ref "IC2") (pin "98") (pinfunction "PC8_98") (pintype "bidirectional"))
      (node (ref "R66") (pin "1") (pinfunction "1_1") (pintype "passive"))
    )
    (net (code "13") (name "CS_AO1_4") (class "Default")
      (node (ref "IC2") (pin "99") (pinfunction "PC9_99") (pintype "bidirectional"))
      (node (ref "R73") (pin "2") (pinfunction "2_2") (pintype "passive"))
    )
    (net (code "14") (name "CS_AO1_8") (class "Default")
      (node (ref "IC2") (pin "100") (pinfunction "PA8_100") (pintype "bidirectional"))
      (node (ref "R65") (pin "1") (pinfunction "1_1") (pintype "passive"))
    )
    (net (code "15") (name "CS_AO2_4") (class "Default")
      (node (ref "IC2") (pin "102") (pinfunction "PA10_102") (pintype "bidirectional"))
      (node (ref "R72") (pin "2") (pinfunction "2_2") (pintype "passive"))
    )
    (net (code "16") (name "CS_AO2_8") (class "Default")
      (node (ref "IC2") (pin "101") (pinfunction "PA9_101") (pintype "bidirectional"))
      (node (ref "R64") (pin "1") (pinfunction "1_1") (pintype "passive"))
    )
    (net (code "17") (name "CS_DI1") (class "Default")
      (node (ref "IC2") (pin "75") (pinfunction "PB14_75") (pintype "bidirectional"))
      (node (ref "R70") (pin "1") (pinfunction "1_1") (pintype "passive"))
    )
    (net (code "18") (name "CS_DI2") (class "Default")
      (node (ref "IC2") (pin "77") (pinfunction "PD8_77") (pintype "bidirectional"))
      (node (ref "R77") (pin "2") (pinfunction "2_2") (pintype "passive"))
    )
    (net (code "19") (name "CS_DO1") (class "Default")
      (node (ref "IC2") (pin "79") (pinfunction "PD10_79") (pintype "bidirectional"))
      (node (ref "R76") (pin "2") (pinfunction "2_2") (pintype "passive"))
    )
    (net (code "20") (name "CS_DO2") (class "Default")
      (node (ref "IC2") (pin "80") (pinfunction "PD11_80") (pintype "bidirectional"))
      (node (ref "R68") (pin "1") (pinfunction "1_1") (pintype "passive"))
    )
    (net (code "21") (name "DI1_INT") (class "Default")
      (node (ref "IC2") (pin "76") (pinfunction "PB15_76") (pintype "bidirectional"))
      (node (ref "R78") (pin "2") (pinfunction "2_2") (pintype "passive"))
    )
    (net (code "22") (name "DI2_INT") (class "Default")
      (node (ref "IC2") (pin "78") (pinfunction "PD9_78") (pintype "bidirectional"))
      (node (ref "R69") (pin "1") (pinfunction "1_1") (pintype "passive"))
    )
    (net (code "23") (name "DI_0") (class "Default")
      (node (ref "IC1") (pin "20") (pinfunction "B1/BH1_20") (pintype "bidirectional"))
      (node (ref "IC2") (pin "134") (pinfunction "PB4_134") (pintype "bidirectional"))
      (node (ref "LED1") (pin "A") (pinfunction "A_A") (pintype "passive"))
    )
    (net (code "24") (name "DI_1") (class "Default")
      (node (ref "IC1") (pin "19") (pinfunction "B2/BH2_19") (pintype "bidirectional"))
      (node (ref "IC2") (pin "135") (pinfunction "PB5_135") (pintype "bidirectional"))
      (node (ref "LED2") (pin "A") (pinfunction "A_A") (pintype "passive"))
    )
    (net (code "25") (name "DI_2") (class "Default")
      (node (ref "IC1") (pin "18") (pinfunction "B3/BH3_18") (pintype "bidirectional"))
      (node (ref "IC2") (pin "136") (pinfunction "PB6_136") (pintype "bidirectional"))
      (node (ref "LED3") (pin "A") (pinfunction "A_A") (pintype "passive"))
    )
    (net (code "26") (name "DI_3") (class "Default")
      (node (ref "IC1") (pin "17") (pinfunction "B4/BH4_17") (pintype "bidirectional"))
      (node (ref "IC2") (pin "137") (pinfunction "PB7_137") (pintype "bidirectional"))
      (node (ref "LED4") (pin "A") (pinfunction "A_A") (pintype "passive"))
    )
    (net (code "27") (name "DI_4") (class "Default")
      (node (ref "IC1") (pin "14") (pinfunction "B5/BH5_14") (pintype "bidirectional"))
      (node (ref "IC2") (pin "139") (pinfunction "PB8_139") (pintype "bidirectional"))
      (node (ref "LED5") (pin "A") (pinfunction "A_A") (pintype "passive"))
    )
    (net (code "28") (name "DI_5") (class "Default")
      (node (ref "IC1") (pin "13") (pinfunction "B6/BH6_13") (pintype "bidirectional"))
      (node (ref "IC2") (pin "140") (pinfunction "PB9_140") (pintype "bidirectional"))
      (node (ref "LED6") (pin "A") (pinfunction "A_A") (pintype "passive"))
    )
    (net (code "29") (name "DI_6") (class "Default")
      (node (ref "IC1") (pin "12") (pinfunction "B7/BH7_12") (pintype "bidirectional"))
      (node (ref "IC2") (pin "141") (pinfunction "PE0_141") (pintype "bidirectional"))
      (node (ref "LED7") (pin "A") (pinfunction "A_A") (pintype "passive"))
    )
    (net (code "30") (name "DI_7") (class "Default")
      (node (ref "IC1") (pin "11") (pinfunction "B8/BH8_11") (pintype "bidirectional"))
      (node (ref "IC2") (pin "142") (pinfunction "PE1_142") (pintype "bidirectional"))
      (node (ref "LED8") (pin "A") (pinfunction "A_A") (pintype "passive"))
    )
    (net (code "31") (name "DMX_DIR") (class "Default")
      (node (ref "IC2") (pin "20") (pinfunction "PF8_20") (pintype "bidirectional"))
      (node (ref "JP1") (pin "5") (pinfunction "5_5") (pintype "passive"))
    )
    (net (code "32") (name "DMX_RX") (class "Default")
      (node (ref "IC2") (pin "18") (pinfunction "PF6_18") (pintype "bidirectional"))
      (node (ref "JP1") (pin "8") (pinfunction "8_8") (pintype "passive"))
    )
    (net (code "33") (name "DMX_TX") (class "Default")
      (node (ref "IC2") (pin "19") (pinfunction "PF7_19") (pintype "bidirectional"))
      (node (ref "JP1") (pin "7") (pinfunction "7_7") (pintype "passive"))
    )
    (net (code "34") (name "DO_0") (class "Default")
      (node (ref "IC2") (pin "54") (pinfunction "PF14_54") (pintype "bidirectional"))
      (node (ref "LED12") (pin "A") (pinfunction "A_A") (pintype "passive"))
      (node (ref "OK1") (pin "2") (pinfunction "VF1-_2") (pintype "passive"))
      (node (ref "R93") (pin "2") (pinfunction "2_2") (pintype "passive"))
    )
    (net (code "35") (name "DO_1") (class "Default")
      (node (ref "IC2") (pin "55") (pinfunction "PF15_55") (pintype "bidirectional"))
      (node (ref "LED13") (pin "A") (pinfunction "A_A") (pintype "passive"))
      (node (ref "OK1") (pin "3") (pinfunction "VF2-_3") (pintype "passive"))
      (node (ref "R94") (pin "2") (pinfunction "2_2") (pintype "passive"))
    )
    (net (code "36") (name "DO_2") (class "Default")
      (node (ref "IC2") (pin "56") (pinfunction "PG0_56") (pintype "bidirectional"))
      (node (ref "LED14") (pin "A") (pinfunction "A_A") (pintype "passive"))
      (node (ref "OK2") (pin "2") (pinfunction "VF1-_2") (pintype "passive"))
      (node (ref "R92") (pin "2") (pinfunction "2_2") (pintype "passive"))
    )
    (net (code "37") (name "DO_3") (class "Default")
      (node (ref "IC2") (pin "57") (pinfunction "PG1_57") (pintype "bidirectional"))
      (node (ref "LED15") (pin "A") (pinfunction "A_A") (pintype "passive"))
      (node (ref "OK2") (pin "3") (pinfunction "VF2-_3") (pintype "passive"))
      (node (ref "R91") (pin "2") (pinfunction "2_2") (pintype "passive"))
    )
    (net (code "38") (name "DO_4") (class "Default")
      (node (ref "IC2") (pin "65") (pinfunction "PE12_65") (pintype "bidirectional"))
      (node (ref "LED16") (pin "A") (pinfunction "A_A") (pintype "passive"))
      (node (ref "OK3") (pin "2") (pinfunction "CA1_2") (pintype "passive"))
      (node (ref "R102") (pin "2") (pinfunction "2_2") (pintype "passive"))
    )
    (net (code "39") (name "DO_5") (class "Default")
      (node (ref "IC2") (pin "66") (pinfunction "PE13_66") (pintype "bidirectional"))
      (node (ref "LED17") (pin "A") (pinfunction "A_A") (pintype "passive"))
      (node (ref "OK3") (pin "4") (pinfunction "CA2_4") (pintype "passive"))
      (node (ref "R101") (pin "2") (pinfunction "2_2") (pintype "passive"))
    )
    (net (code "40") (name "DO_6") (class "Default")
      (node (ref "IC2") (pin "67") (pinfunction "PE14_67") (pintype "bidirectional"))
      (node (ref "LED18") (pin "A") (pinfunction "A_A") (pintype "passive"))
      (node (ref "OK3") (pin "6") (pinfunction "CA3_6") (pintype "passive"))
      (node (ref "R100") (pin "2") (pinfunction "2_2") (pintype "passive"))
    )
    (net (code "41") (name "DO_7") (class "Default")
      (node (ref "IC2") (pin "68") (pinfunction "PE15_68") (pintype "bidirectional"))
      (node (ref "LED19") (pin "A") (pinfunction "A_A") (pintype "passive"))
      (node (ref "OK3") (pin "8") (pinfunction "CA4_8") (pintype "passive"))
      (node (ref "R99") (pin "2") (pinfunction "2_2") (pintype "passive"))
    )
    (net (code "42") (name "GND") (class "Default")
      (node (ref "C10") (pin "2") (pinfunction "2_2") (pintype "passive"))
      (node (ref "C11") (pin "2") (pinfunction "2_2") (pintype "passive"))
      (node (ref "C12") (pin "2") (pinfunction "2_2") (pintype "passive"))
      (node (ref "C13") (pin "2") (pinfunction "2_2") (pintype "passive"))
      (node (ref "C14") (pin "2") (pinfunction "2_2") (pintype "passive"))
      (node (ref "C15") (pin "2") (pinfunction "2_2") (pintype "passive"))
      (node (ref "C16") (pin "2") (pinfunction "2_2") (pintype "passive"))
      (node (ref "C17") (pin "2") (pinfunction "2_2") (pintype "passive"))
      (node (ref "C18") (pin "2") (pinfunction "2_2") (pintype "passive"))
      (node (ref "C19") (pin "2") (pinfunction "2_2") (pintype "passive"))
      (node (ref "C20") (pin "2") (pinfunction "2_2") (pintype "passive"))
      (node (ref "C21") (pin "2") (pinfunction "2_2") (pintype "passive"))
      (node (ref "C22") (pin "2") (pinfunction "2_2") (pintype "passive"))
      (node (ref "C23") (pin "2") (pinfunction "2_2") (pintype "passive"))
      (node (ref "C24") (pin "2") (pinfunction "2_2") (pintype "passive"))
      (node (ref "C25") (pin "1") (pinfunction "1_1") (pintype "passive"))
      (node (ref "C26") (pin "2") (pinfunction "2_2") (pintype "passive"))
      (node (ref "C27") (pin "1") (pinfunction "1_1") (pintype "passive"))
      (node (ref "C28") (pin "2") (pinfunction "2_2") (pintype "passive"))
      (node (ref "C29") (pin "2") (pinfunction "2_2") (pintype "passive"))
      (node (ref "C30") (pin "2") (pinfunction "2_2") (pintype "passive"))
      (node (ref "C31") (pin "2") (pinfunction "2_2") (pintype "passive"))
      (node (ref "C32") (pin "2") (pinfunction "2_2") (pintype "passive"))
      (node (ref "C33") (pin "2") (pinfunction "2_2") (pintype "passive"))
      (node (ref "C34") (pin "2") (pinfunction "2_2") (pintype "passive"))
      (node (ref "C35") (pin "2") (pinfunction "2_2") (pintype "passive"))
      (node (ref "C36") (pin "-") (pinfunction "-_-") (pintype "passive"))
      (node (ref "C37") (pin "2") (pinfunction "2_2") (pintype "passive"))
      (node (ref "C38") (pin "2") (pinfunction "2_2") (pintype "passive"))
      (node (ref "C39") (pin "2") (pinfunction "2_2") (pintype "passive"))
      (node (ref "C40") (pin "2") (pinfunction "2_2") (pintype "passive"))
      (node (ref "C41") (pin "2") (pinfunction "2_2") (pintype "passive"))
      (node (ref "C42") (pin "2") (pinfunction "2_2") (pintype "passive"))
      (node (ref "C43") (pin "2") (pinfunction "2_2") (pintype "passive"))
      (node (ref "C45") (pin "1") (pinfunction "1_1") (pintype "passive"))
      (node (ref "C9") (pin "2") (pinfunction "2_2") (pintype "passive"))
      (node (ref "D1") (pin "2") (pinfunction "GND_2") (pintype "input"))
      (node (ref "G1") (pin "-") (pinfunction "-_-") (pintype "passive"))
      (node (ref "IC1") (pin "15") (pinfunction "GND_15") (pintype "bidirectional"))
      (node (ref "IC2") (pin "107") (pinfunction "VSS_107") (pintype "bidirectional"))
      (node (ref "IC2") (pin "120") (pinfunction "VSS_120") (pintype "bidirectional"))
      (node (ref "IC2") (pin "130") (pinfunction "VSS_130") (pintype "bidirectional"))
      (node (ref "IC2") (pin "16") (pinfunction "VSS_16") (pintype "bidirectional"))
      (node (ref "IC2") (pin "31") (pinfunction "VSSA_31") (pintype "bidirectional"))
      (node (ref "IC2") (pin "38") (pinfunction "VSS_38") (pintype "bidirectional"))
      (node (ref "IC2") (pin "51") (pinfunction "VSS_51") (pintype "bidirectional"))
      (node (ref "IC2") (pin "61") (pinfunction "VSS_61") (pintype "bidirectional"))
      (node (ref "IC2") (pin "83") (pinfunction "VSS_83") (pintype "bidirectional"))
      (node (ref "IC2") (pin "94") (pinfunction "VSS_94") (pintype "bidirectional"))
      (node (ref "IC3") (pin "15") (pinfunction "AGND1_15") (pintype "power_in"))
      (node (ref "IC3") (pin "19") (pinfunction "AGND2_19") (pintype "power_in"))
      (node (ref "IC3") (pin "35") (pinfunction "IOGND1_35") (pintype "power_in"))
      (node (ref "IC3") (pin "36") (pinfunction "DGND_36") (pintype "power_in"))
      (node (ref "IC3") (pin "47") (pinfunction "IOGND2_47") (pintype "power_in"))
      (node (ref "JP1") (pin "10") (pinfunction "10_10") (pintype "passive"))
      (node (ref "JP1") (pin "3") (pinfunction "3_3") (pintype "passive"))
      (node (ref "JP1") (pin "4") (pinfunction "4_4") (pintype "passive"))
      (node (ref "JP1") (pin "6") (pinfunction "6_6") (pintype "passive"))
      (node (ref "JP1") (pin "9") (pinfunction "9_9") (pintype "passive"))
      (node (ref "JP2") (pin "10") (pinfunction "10_10") (pintype "passive"))
      (node (ref "JP2") (pin "13") (pinfunction "13_13") (pintype "passive"))
      (node (ref "JP2") (pin "18") (pinfunction "18_18") (pintype "passive"))
      (node (ref "JP2") (pin "21") (pinfunction "21_21") (pintype "passive"))
      (node (ref "JP2") (pin "4") (pinfunction "4_4") (pintype "passive"))
      (node (ref "JP2") (pin "5") (pinfunction "5_5") (pintype "passive"))
      (node (ref "JP2") (pin "6") (pinfunction "6_6") (pintype "passive"))
      (node (ref "LED10") (pin "C") (pinfunction "C_C") (pintype "passive"))
      (node (ref "LED9") (pin "C") (pinfunction "C_C") (pintype "passive"))
      (node (ref "OS1") (pin "2") (pinfunction "VSS_2") (pintype "power_in"))
      (node (ref "Q2") (pin "2") (pinfunction "2_2") (pintype "passive"))
      (node (ref "Q2") (pin "4") (pinfunction "4_4") (pintype "passive"))
      (node (ref "R100") (pin "1") (pinfunction "1_1") (pintype "passive"))
      (node (ref "R101") (pin "1") (pinfunction "1_1") (pintype "passive"))
      (node (ref "R102") (pin "1") (pinfunction "1_1") (pintype "passive"))
      (node (ref "R17") (pin "2") (pinfunction "2_2") (pintype "passive"))
      (node (ref "R18") (pin "2") (pinfunction "2_2") (pintype "passive"))
      (node (ref "R19") (pin "2") (pinfunction "2_2") (pintype "passive"))
      (node (ref "R20") (pin "2") (pinfunction "2_2") (pintype "passive"))
      (node (ref "R21") (pin "2") (pinfunction "2_2") (pintype "passive"))
      (node (ref "R22") (pin "2") (pinfunction "2_2") (pintype "passive"))
      (node (ref "R23") (pin "2") (pinfunction "2_2") (pintype "passive"))
      (node (ref "R24") (pin "2") (pinfunction "2_2") (pintype "passive"))
      (node (ref "R32") (pin "1") (pinfunction "1_1") (pintype "passive"))
      (node (ref "R34") (pin "2") (pinfunction "2_2") (pintype "passive"))
      (node (ref "R54") (pin "2") (pinfunction "2_2") (pintype "passive"))
      (node (ref "R55") (pin "2") (pinfunction "2_2") (pintype "passive"))
      (node (ref "R56") (pin "2") (pinfunction "2_2") (pintype "passive"))
      (node (ref "R57") (pin "2") (pinfunction "2_2") (pintype "passive"))
      (node (ref "R58") (pin "2") (pinfunction "2_2") (pintype "passive"))
      (node (ref "R59") (pin "2") (pinfunction "2_2") (pintype "passive"))
      (node (ref "R60") (pin "2") (pinfunction "2_2") (pintype "passive"))
      (node (ref "R61") (pin "2") (pinfunction "2_2") (pintype "passive"))
      (node (ref "R91") (pin "1") (pinfunction "1_1") (pintype "passive"))
      (node (ref "R92") (pin "1") (pinfunction "1_1") (pintype "passive"))
      (node (ref "R93") (pin "1") (pinfunction "1_1") (pintype "passive"))
      (node (ref "R94") (pin "1") (pinfunction "1_1") (pintype "passive"))
      (node (ref "R99") (pin "1") (pinfunction "1_1") (pintype "passive"))
      (node (ref "S1") (pin "1") (pinfunction "1_1") (pintype "passive"))
      (node (ref "S1") (pin "2") (pinfunction "2_2") (pintype "passive"))
      (node (ref "SV1") (pin "3") (pinfunction "3_3") (pintype "passive"))
      (node (ref "SV1") (pin "4") (pinfunction "4_4") (pintype "passive"))
    )
    (net (code "43") (name "GND2") (class "Default")
      (node (ref "C46") (pin "2") (pinfunction "2_2") (pintype "passive"))
      (node (ref "C47") (pin "2") (pinfunction "2_2") (pintype "passive"))
      (node (ref "C48") (pin "2") (pinfunction "2_2") (pintype "passive"))
      (node (ref "C49") (pin "2") (pinfunction "2_2") (pintype "passive"))
      (node (ref "C50") (pin "2") (pinfunction "2_2") (pintype "passive"))
      (node (ref "IC4") (pin "9") (pinfunction "GND_9") (pintype "output"))
      (node (ref "OK1") (pin "5") (pinfunction "GND_5") (pintype "passive"))
      (node (ref "OK2") (pin "5") (pinfunction "GND_5") (pintype "passive"))
      (node (ref "Q3") (pin "10") (pinfunction "GND_10") (pintype "passive"))
      (node (ref "R111") (pin "1") (pinfunction "1_1") (pintype "passive"))
      (node (ref "R114") (pin "1") (pinfunction "1_1") (pintype "passive"))
      (node (ref "X4") (pin "1") (pinfunction "KL_1") (pintype "passive"))
    )
    (net (code "44") (name "GND3") (class "Default")
      (node (ref "C51") (pin "2") (pinfunction "2_2") (pintype "passive"))
      (node (ref "C52") (pin "2") (pinfunction "2_2") (pintype "passive"))
      (node (ref "C53") (pin "2") (pinfunction "2_2") (pintype "passive"))
      (node (ref "IC5") (pin "9") (pinfunction "GND_9") (pintype "output"))
      (node (ref "OK3") (pin "11") (pinfunction "CO3_11") (pintype "passive"))
      (node (ref "OK3") (pin "13") (pinfunction "CO2_13") (pintype "passive"))
      (node (ref "OK3") (pin "15") (pinfunction "CO1_15") (pintype "passive"))
      (node (ref "OK3") (pin "9") (pinfunction "CO4_9") (pintype "passive"))
      (node (ref "Q4") (pin "10") (pinfunction "GND_10") (pintype "passive"))
      (node (ref "R115") (pin "1") (pinfunction "1_1") (pintype "passive"))
      (node (ref "R118") (pin "1") (pinfunction "1_1") (pintype "passive"))
      (node (ref "X7") (pin "1") (pinfunction "KL_1") (pintype "passive"))
    )
    (net (code "45") (name "LED_ACT") (class "Default")
      (node (ref "IC3") (pin "26") (pinfunction "LED_ACT_26") (pintype "bidirectional"))
      (node (ref "J1") (pin "9") (pinfunction "YLED-_9") (pintype "bidirectional"))
      (node (ref "R51") (pin "1") (pinfunction "1_1") (pintype "passive"))
    )
    (net (code "46") (name "LED_BLUE") (class "Default")
      (node (ref "IC2") (pin "2") (pinfunction "PE3_2") (pintype "bidirectional"))
      (node (ref "R28") (pin "2") (pinfunction "2_2") (pintype "passive"))
    )
    (net (code "47") (name "LED_GREEN") (class "Default")
      (node (ref "IC2") (pin "3") (pinfunction "PE4_3") (pintype "bidirectional"))
      (node (ref "R29") (pin "2") (pinfunction "2_2") (pintype "passive"))
    )
    (net (code "48") (name "LED_LINK") (class "Default")
      (node (ref "IC3") (pin "28") (pinfunction "LED_LNK_28") (pintype "bidirectional"))
      (node (ref "J1") (pin "11") (pinfunction "GLED-_11") (pintype "bidirectional"))
      (node (ref "R53") (pin "1") (pinfunction "1_1") (pintype "passive"))
    )
    (net (code "49") (name "LED_RED") (class "Default")
      (node (ref "IC2") (pin "1") (pinfunction "PE2_1") (pintype "bidirectional"))
      (node (ref "R27") (pin "2") (pinfunction "2_2") (pintype "passive"))
    )
    (net (code "50") (name "NRST") (class "Default")
      (node (ref "C21") (pin "1") (pinfunction "1_1") (pintype "passive"))
      (node (ref "IC2") (pin "25") (pinfunction "NRST_25") (pintype "bidirectional"))
      (node (ref "IC3") (pin "29") (pinfunction "RESET_N_29") (pintype "input"))
      (node (ref "S1") (pin "3") (pinfunction "3_3") (pintype "passive"))
      (node (ref "S1") (pin "4") (pinfunction "4_4") (pintype "passive"))
      (node (ref "SV1") (pin "1") (pinfunction "1_1") (pintype "passive"))
    )
    (net (code "51") (name "Net-(C44-Pad1)") (class "Default")
      (node (ref "C44") (pin "1") (pinfunction "1_1") (pintype "passive"))
      (node (ref "R46") (pin "1") (pinfunction "1_1") (pintype "passive"))
      (node (ref "R47") (pin "1") (pinfunction "1_1") (pintype "passive"))
      (node (ref "R48") (pin "1") (pinfunction "1_1") (pintype "passive"))
      (node (ref "R49") (pin "1") (pinfunction "1_1") (pintype "passive"))
    )
    (net (code "52") (name "Net-(D1-I{slash}O1)") (class "Default")
      (node (ref "D1") (pin "1") (pinfunction "I/O1_1") (pintype "power_in"))
      (node (ref "IC3") (pin "16") (pinfunction "TD-_16") (pintype "bidirectional"))
      (node (ref "R38") (pin "1") (pinfunction "1_1") (pintype "passive"))
      (node (ref "R43") (pin "1") (pinfunction "1_1") (pintype "passive"))
    )
    (net (code "53") (name "Net-(D1-I{slash}O2)") (class "Default")
      (node (ref "D1") (pin "3") (pinfunction "I/O2_3") (pintype "input"))
      (node (ref "IC3") (pin "14") (pinfunction "RD+_14") (pintype "bidirectional"))
      (node (ref "R39") (pin "1") (pinfunction "1_1") (pintype "passive"))
      (node (ref "R42") (pin "1") (pinfunction "1_1") (pintype "passive"))
    )
    (net (code "54") (name "Net-(D1-I{slash}O3)") (class "Default")
      (node (ref "D1") (pin "4") (pinfunction "I/O3_4") (pintype "input"))
      (node (ref "IC3") (pin "13") (pinfunction "RD-_13") (pintype "bidirectional"))
      (node (ref "R40") (pin "1") (pinfunction "1_1") (pintype "passive"))
      (node (ref "R44") (pin "1") (pinfunction "1_1") (pintype "passive"))
    )
    (net (code "55") (name "Net-(D1-I{slash}O4)") (class "Default")
      (node (ref "D1") (pin "6") (pinfunction "I/O4_6") (pintype "output"))
      (node (ref "IC3") (pin "17") (pinfunction "TD+_17") (pintype "bidirectional"))
      (node (ref "R37") (pin "1") (pinfunction "1_1") (pintype "passive"))
      (node (ref "R41") (pin "1") (pinfunction "1_1") (pintype "passive"))
    )
    (net (code "56") (name "Net-(IC1-A1{slash}AH1)") (class "Default")
      (node (ref "C1") (pin "1") (pinfunction "1_1") (pintype "passive"))
      (node (ref "IC1") (pin "1") (pinfunction "A1/AH1_1") (pintype "bidirectional"))
      (node (ref "R1") (pin "2") (pinfunction "2_2") (pintype "passive"))
      (node (ref "R9") (pin "2") (pinfunction "2_2") (pintype "passive"))
    )
    (net (code "57") (name "Net-(IC1-A2{slash}AH2)") (class "Default")
      (node (ref "C2") (pin "1") (pinfunction "1_1") (pintype "passive"))
      (node (ref "IC1") (pin "2") (pinfunction "A2/AH2_2") (pintype "bidirectional"))
      (node (ref "R10") (pin "2") (pinfunction "2_2") (pintype "passive"))
      (node (ref "R2") (pin "2") (pinfunction "2_2") (pintype "passive"))
    )
    (net (code "58") (name "Net-(IC1-A3{slash}AH3)") (class "Default")
      (node (ref "C3") (pin "1") (pinfunction "1_1") (pintype "passive"))
      (node (ref "IC1") (pin "3") (pinfunction "A3/AH3_3") (pintype "bidirectional"))
      (node (ref "R11") (pin "2") (pinfunction "2_2") (pintype "passive"))
      (node (ref "R3") (pin "2") (pinfunction "2_2") (pintype "passive"))
    )
    (net (code "59") (name "Net-(IC1-A4{slash}AH4)") (class "Default")
      (node (ref "C4") (pin "1") (pinfunction "1_1") (pintype "passive"))
      (node (ref "IC1") (pin "4") (pinfunction "A4/AH4_4") (pintype "bidirectional"))
      (node (ref "R12") (pin "2") (pinfunction "2_2") (pintype "passive"))
      (node (ref "R4") (pin "2") (pinfunction "2_2") (pintype "passive"))
    )
    (net (code "60") (name "Net-(IC1-A5{slash}AH5)") (class "Default")
      (node (ref "C5") (pin "1") (pinfunction "1_1") (pintype "passive"))
      (node (ref "IC1") (pin "7") (pinfunction "A5/AH5_7") (pintype "bidirectional"))
      (node (ref "R13") (pin "2") (pinfunction "2_2") (pintype "passive"))
      (node (ref "R5") (pin "2") (pinfunction "2_2") (pintype "passive"))
    )
    (net (code "61") (name "Net-(IC1-A6{slash}AH6)") (class "Default")
      (node (ref "C6") (pin "1") (pinfunction "1_1") (pintype "passive"))
      (node (ref "IC1") (pin "8") (pinfunction "A6/AH6_8") (pintype "bidirectional"))
      (node (ref "R14") (pin "2") (pinfunction "2_2") (pintype "passive"))
      (node (ref "R6") (pin "2") (pinfunction "2_2") (pintype "passive"))
    )
    (net (code "62") (name "Net-(IC1-A7{slash}AH7)") (class "Default")
      (node (ref "C7") (pin "1") (pinfunction "1_1") (pintype "passive"))
      (node (ref "IC1") (pin "9") (pinfunction "A7/AH7_9") (pintype "bidirectional"))
      (node (ref "R15") (pin "2") (pinfunction "2_2") (pintype "passive"))
      (node (ref "R7") (pin "2") (pinfunction "2_2") (pintype "passive"))
    )
    (net (code "63") (name "Net-(IC1-A8{slash}AH8)") (class "Default")
      (node (ref "C8") (pin "1") (pinfunction "1_1") (pintype "passive"))
      (node (ref "IC1") (pin "10") (pinfunction "A8/AH8_10") (pintype "bidirectional"))
      (node (ref "R16") (pin "2") (pinfunction "2_2") (pintype "passive"))
      (node (ref "R8") (pin "2") (pinfunction "2_2") (pintype "passive"))
    )
    (net (code "64") (name "Net-(IC2-PC14)") (class "Default")
      (node (ref "C11") (pin "1") (pinfunction "1_1") (pintype "passive"))
      (node (ref "IC2") (pin "8") (pinfunction "PC14_8") (pintype "bidirectional"))
      (node (ref "Q1") (pin "1") (pinfunction "1_1") (pintype "passive"))
    )
    (net (code "65") (name "Net-(IC2-PC15)") (class "Default")
      (node (ref "C12") (pin "1") (pinfunction "1_1") (pintype "passive"))
      (node (ref "IC2") (pin "9") (pinfunction "PC15_9") (pintype "bidirectional"))
      (node (ref "Q1") (pin "2") (pinfunction "2_2") (pintype "passive"))
    )
    (net (code "66") (name "Net-(IC2-PH0)") (class "Default")
      (node (ref "C13") (pin "1") (pinfunction "1_1") (pintype "passive"))
      (node (ref "IC2") (pin "23") (pinfunction "PH0_23") (pintype "bidirectional"))
      (node (ref "Q2") (pin "1") (pinfunction "1_1") (pintype "passive"))
    )
    (net (code "67") (name "Net-(IC2-PH1)") (class "Default")
      (node (ref "C14") (pin "1") (pinfunction "1_1") (pintype "passive"))
      (node (ref "IC2") (pin "24") (pinfunction "PH1_24") (pintype "bidirectional"))
      (node (ref "Q2") (pin "3") (pinfunction "3_3") (pintype "passive"))
    )
    (net (code "68") (name "Net-(IC2-VBAT)") (class "Default")
      (node (ref "C30") (pin "1") (pinfunction "1_1") (pintype "passive"))
      (node (ref "G1") (pin "+") (pinfunction "+_+") (pintype "passive"))
      (node (ref "IC2") (pin "6") (pinfunction "VBAT_6") (pintype "bidirectional"))
    )
    (net (code "69") (name "Net-(IC2-VCAP1)") (class "Default")
      (node (ref "C25") (pin "2") (pinfunction "2_2") (pintype "passive"))
      (node (ref "IC2") (pin "71") (pinfunction "VCAP1_71") (pintype "bidirectional"))
    )
    (net (code "70") (name "Net-(IC2-VCAP2)") (class "Default")
      (node (ref "C27") (pin "2") (pinfunction "2_2") (pintype "passive"))
      (node (ref "IC2") (pin "106") (pinfunction "VCAP2_106") (pintype "bidirectional"))
    )
    (net (code "71") (name "Net-(IC3-LED_SPD)") (class "Default")
      (node (ref "IC3") (pin "27") (pinfunction "LED_SPD_27") (pintype "bidirectional"))
      (node (ref "R33") (pin "1") (pinfunction "1_1") (pintype "passive"))
    )
    (net (code "72") (name "Net-(IC3-RBIAS)") (class "Default")
      (node (ref "IC3") (pin "24") (pinfunction "RBIAS_24") (pintype "bidirectional"))
      (node (ref "R34") (pin "1") (pinfunction "1_1") (pintype "passive"))
    )
    (net (code "73") (name "Net-(IC3-RESERVED1)") (class "Default")
      (node (ref "IC3") (pin "20") (pinfunction "RESERVED1_20") (pintype "input"))
      (node (ref "R36") (pin "1") (pinfunction "1_1") (pintype "passive"))
    )
    (net (code "74") (name "Net-(IC3-RESERVED2)") (class "Default")
      (node (ref "IC3") (pin "21") (pinfunction "RESERVED2_21") (pintype "input"))
      (node (ref "R35") (pin "1") (pinfunction "1_1") (pintype "passive"))
    )
    (net (code "75") (name "Net-(IC3-RX_DV)") (class "Default")
      (node (ref "IC3") (pin "39") (pinfunction "RX_DV_39") (pintype "bidirectional"))
      (node (ref "R30") (pin "1") (pinfunction "1_1") (pintype "passive"))
    )
    (net (code "76") (name "Net-(IC3-TXD_3)") (class "Default")
      (node (ref "IC3") (pin "6") (pinfunction "TXD_3_6") (pintype "bidirectional"))
      (node (ref "R32") (pin "2") (pinfunction "2_2") (pintype "passive"))
    )
    (net (code "77") (name "Net-(IC3-X1)") (class "Default")
      (node (ref "IC3") (pin "34") (pinfunction "X1_34") (pintype "input"))
      (node (ref "OS1") (pin "3") (pinfunction "OUT_3") (pintype "output"))
    )
    (net (code "78") (name "Net-(IC4-FB)") (class "Default")
      (node (ref "IC4") (pin "5") (pinfunction "FB_5") (pintype "input"))
      (node (ref "R113") (pin "1") (pinfunction "1_1") (pintype "passive"))
      (node (ref "R114") (pin "2") (pinfunction "2_2") (pintype "passive"))
    )
    (net (code "79") (name "Net-(IC4-LX)") (class "Default")
      (node (ref "IC4") (pin "10") (pinfunction "LX_10") (pintype "output"))
      (node (ref "L3") (pin "1") (pinfunction "1_1") (pintype "passive"))
    )
    (net (code "80") (name "Net-(IC4-RT{slash}SYNC)") (class "Default")
      (node (ref "IC4") (pin "3") (pinfunction "RT/SYNC_3") (pintype "input"))
      (node (ref "R111") (pin "2") (pinfunction "2_2") (pintype "passive"))
    )
    (net (code "81") (name "Net-(IC4-VOUT)") (class "Default")
      (node (ref "C48") (pin "1") (pinfunction "1_1") (pintype "passive"))
      (node (ref "IC4") (pin "6") (pinfunction "VOUT_6") (pintype "input"))
      (node (ref "R112") (pin "1") (pinfunction "1_1") (pintype "passive"))
    )
    (net (code "82") (name "Net-(IC5-FB)") (class "Default")
      (node (ref "IC5") (pin "5") (pinfunction "FB_5") (pintype "input"))
      (node (ref "R117") (pin "1") (pinfunction "1_1") (pintype "passive"))
      (node (ref "R118") (pin "2") (pinfunction "2_2") (pintype "passive"))
    )
    (net (code "83") (name "Net-(IC5-LX)") (class "Default")
      (node (ref "IC5") (pin "10") (pinfunction "LX_10") (pintype "output"))
      (node (ref "L2") (pin "1") (pinfunction "1_1") (pintype "passive"))
    )
    (net (code "84") (name "Net-(IC5-RT{slash}SYNC)") (class "Default")
      (node (ref "IC5") (pin "3") (pinfunction "RT/SYNC_3") (pintype "input"))
      (node (ref "R115") (pin "2") (pinfunction "2_2") (pintype "passive"))
    )
    (net (code "85") (name "Net-(IC5-VOUT)") (class "Default")
      (node (ref "C51") (pin "1") (pinfunction "1_1") (pintype "passive"))
      (node (ref "IC5") (pin "6") (pinfunction "VOUT_6") (pintype "input"))
      (node (ref "R116") (pin "1") (pinfunction "1_1") (pintype "passive"))
    )
    (net (code "86") (name "Net-(J1-GLED+)") (class "Default")
      (node (ref "J1") (pin "12") (pinfunction "GLED+_12") (pintype "bidirectional"))
      (node (ref "R52") (pin "1") (pinfunction "1_1") (pintype "passive"))
    )
    (net (code "87") (name "Net-(J1-NC1)") (class "Default")
      (node (ref "J1") (pin "4") (pinfunction "NC1_4") (pintype "bidirectional"))
      (node (ref "J1") (pin "5") (pinfunction "NC2_5") (pintype "bidirectional"))
      (node (ref "R48") (pin "2") (pinfunction "2_2") (pintype "passive"))
    )
    (net (code "88") (name "Net-(J1-NC3)") (class "Default")
      (node (ref "J1") (pin "7") (pinfunction "NC3_7") (pintype "bidirectional"))
      (node (ref "J1") (pin "8") (pinfunction "NC4_8") (pintype "bidirectional"))
      (node (ref "R49") (pin "2") (pinfunction "2_2") (pintype "passive"))
    )
    (net (code "89") (name "Net-(J1-RX+)") (class "Default")
      (node (ref "J1") (pin "3") (pinfunction "RX+_3") (pintype "bidirectional"))
      (node (ref "T1") (pin "11") (pinfunction "RX+_11") (pintype "passive"))
    )
    (net (code "90") (name "Net-(J1-RX-)") (class "Default")
      (node (ref "J1") (pin "6") (pinfunction "RX-_6") (pintype "bidirectional"))
      (node (ref "T1") (pin "9") (pinfunction "RX-_9") (pintype "passive"))
    )
    (net (code "91") (name "Net-(J1-TX+)") (class "Default")
      (node (ref "J1") (pin "1") (pinfunction "TX+_1") (pintype "bidirectional"))
      (node (ref "T1") (pin "16") (pinfunction "TX+_16") (pintype "passive"))
    )
    (net (code "92") (name "Net-(J1-TX-)") (class "Default")
      (node (ref "J1") (pin "2") (pinfunction "TX-_2") (pintype "bidirectional"))
      (node (ref "T1") (pin "14") (pinfunction "TX-_14") (pintype "passive"))
    )
    (net (code "93") (name "Net-(J1-YLED+)") (class "Default")
      (node (ref "J1") (pin "10") (pinfunction "YLED+_10") (pintype "bidirectional"))
      (node (ref "R50") (pin "1") (pinfunction "1_1") (pintype "passive"))
    )
    (net (code "94") (name "Net-(JP2-Pad1)") (class "Default")
      (node (ref "JP2") (pin "1") (pinfunction "1_1") (pintype "passive"))
      (node (ref "R62") (pin "2") (pinfunction "2_2") (pintype "passive"))
    )
    (net (code "95") (name "Net-(JP2-Pad2)") (class "Default")
      (node (ref "JP2") (pin "2") (pinfunction "2_2") (pintype "passive"))
      (node (ref "R71") (pin "1") (pinfunction "1_1") (pintype "passive"))
    )
    (net (code "96") (name "Net-(JP2-Pad3)") (class "Default")
      (node (ref "JP2") (pin "3") (pinfunction "3_3") (pintype "passive"))
      (node (ref "R63") (pin "2") (pinfunction "2_2") (pintype "passive"))
    )
    (net (code "97") (name "Net-(JP2-Pad7)") (class "Default")
      (node (ref "JP2") (pin "7") (pinfunction "7_7") (pintype "passive"))
      (node (ref "R64") (pin "2") (pinfunction "2_2") (pintype "passive"))
    )
    (net (code "98") (name "Net-(JP2-Pad8)") (class "Default")
      (node (ref "JP2") (pin "8") (pinfunction "8_8") (pintype "passive"))
      (node (ref "R72") (pin "1") (pinfunction "1_1") (pintype "passive"))
    )
    (net (code "99") (name "Net-(JP2-Pad9)") (class "Default")
      (node (ref "JP2") (pin "9") (pinfunction "9_9") (pintype "passive"))
      (node (ref "R65") (pin "2") (pinfunction "2_2") (pintype "passive"))
    )
    (net (code "100") (name "Net-(JP2-Pad11)") (class "Default")
      (node (ref "JP2") (pin "11") (pinfunction "11_11") (pintype "passive"))
      (node (ref "R66") (pin "2") (pinfunction "2_2") (pintype "passive"))
    )
    (net (code "101") (name "Net-(JP2-Pad12)") (class "Default")
      (node (ref "JP2") (pin "12") (pinfunction "12_12") (pintype "passive"))
      (node (ref "R73") (pin "1") (pinfunction "1_1") (pintype "passive"))
    )
    (net (code "102") (name "Net-(JP2-Pad14)") (class "Default")
      (node (ref "JP2") (pin "14") (pinfunction "14_14") (pintype "passive"))
      (node (ref "R74") (pin "1") (pinfunction "1_1") (pintype "passive"))
    )
    (net (code "103") (name "Net-(JP2-Pad15)") (class "Default")
      (node (ref "JP2") (pin "15") (pinfunction "15_15") (pintype "passive"))
      (node (ref "R67") (pin "2") (pinfunction "2_2") (pintype "passive"))
    )
    (net (code "104") (name "Net-(JP2-Pad16)") (class "Default")
      (node (ref "JP2") (pin "16") (pinfunction "16_16") (pintype "passive"))
      (node (ref "R75") (pin "1") (pinfunction "1_1") (pintype "passive"))
    )
    (net (code "105") (name "Net-(JP2-Pad17)") (class "Default")
      (node (ref "JP2") (pin "17") (pinfunction "17_17") (pintype "passive"))
      (node (ref "R68") (pin "2") (pinfunction "2_2") (pintype "passive"))
    )
    (net (code "106") (name "Net-(JP2-Pad19)") (class "Default")
      (node (ref "JP2") (pin "19") (pinfunction "19_19") (pintype "passive"))
      (node (ref "R69") (pin "2") (pinfunction "2_2") (pintype "passive"))
    )
    (net (code "107") (name "Net-(JP2-Pad20)") (class "Default")
      (node (ref "JP2") (pin "20") (pinfunction "20_20") (pintype "passive"))
      (node (ref "R76") (pin "1") (pinfunction "1_1") (pintype "passive"))
    )
    (net (code "108") (name "Net-(JP2-Pad22)") (class "Default")
      (node (ref "JP2") (pin "22") (pinfunction "22_22") (pintype "passive"))
      (node (ref "R77") (pin "1") (pinfunction "1_1") (pintype "passive"))
    )
    (net (code "109") (name "Net-(JP2-Pad23)") (class "Default")
      (node (ref "JP2") (pin "23") (pinfunction "23_23") (pintype "passive"))
      (node (ref "R70") (pin "2") (pinfunction "2_2") (pintype "passive"))
    )
    (net (code "110") (name "Net-(JP2-Pad24)") (class "Default")
      (node (ref "JP2") (pin "24") (pinfunction "24_24") (pintype "passive"))
      (node (ref "R78") (pin "1") (pinfunction "1_1") (pintype "passive"))
    )
    (net (code "111") (name "Net-(JP3-Pad2)") (class "Default")
      (node (ref "JP3") (pin "2") (pinfunction "2_2") (pintype "passive"))
      (node (ref "SV1") (pin "7") (pinfunction "7_7") (pintype "passive"))
      (node (ref "SV1") (pin "8") (pinfunction "8_8") (pintype "passive"))
    )
    (net (code "112") (name "Net-(LED1-PadC)") (class "Default")
      (node (ref "LED1") (pin "C") (pinfunction "C_C") (pintype "passive"))
      (node (ref "R17") (pin "1") (pinfunction "1_1") (pintype "passive"))
    )
    (net (code "113") (name "Net-(LED2-PadC)") (class "Default")
      (node (ref "LED2") (pin "C") (pinfunction "C_C") (pintype "passive"))
      (node (ref "R18") (pin "1") (pinfunction "1_1") (pintype "passive"))
    )
    (net (code "114") (name "Net-(LED3-PadC)") (class "Default")
      (node (ref "LED3") (pin "C") (pinfunction "C_C") (pintype "passive"))
      (node (ref "R19") (pin "1") (pinfunction "1_1") (pintype "passive"))
    )
    (net (code "115") (name "Net-(LED4-PadC)") (class "Default")
      (node (ref "LED4") (pin "C") (pinfunction "C_C") (pintype "passive"))
      (node (ref "R20") (pin "1") (pinfunction "1_1") (pintype "passive"))
    )
    (net (code "116") (name "Net-(LED5-PadC)") (class "Default")
      (node (ref "LED5") (pin "C") (pinfunction "C_C") (pintype "passive"))
      (node (ref "R21") (pin "1") (pinfunction "1_1") (pintype "passive"))
    )
    (net (code "117") (name "Net-(LED6-PadC)") (class "Default")
      (node (ref "LED6") (pin "C") (pinfunction "C_C") (pintype "passive"))
      (node (ref "R22") (pin "1") (pinfunction "1_1") (pintype "passive"))
    )
    (net (code "118") (name "Net-(LED7-PadC)") (class "Default")
      (node (ref "LED7") (pin "C") (pinfunction "C_C") (pintype "passive"))
      (node (ref "R23") (pin "1") (pinfunction "1_1") (pintype "passive"))
    )
    (net (code "119") (name "Net-(LED8-PadC)") (class "Default")
      (node (ref "LED8") (pin "C") (pinfunction "C_C") (pintype "passive"))
      (node (ref "R24") (pin "1") (pinfunction "1_1") (pintype "passive"))
    )
    (net (code "120") (name "Net-(LED9-PadA)") (class "Default")
      (node (ref "LED9") (pin "A") (pinfunction "A_A") (pintype "passive"))
      (node (ref "R25") (pin "2") (pinfunction "2_2") (pintype "passive"))
    )
    (net (code "121") (name "Net-(LED10-PadA)") (class "Default")
      (node (ref "LED10") (pin "A") (pinfunction "A_A") (pintype "passive"))
      (node (ref "R26") (pin "2") (pinfunction "2_2") (pintype "passive"))
    )
    (net (code "122") (name "Net-(LED11-CBLUE)") (class "Default")
      (node (ref "LED11") (pin "3") (pinfunction "CBLUE_3") (pintype "passive"))
      (node (ref "R28") (pin "1") (pinfunction "1_1") (pintype "passive"))
    )
    (net (code "123") (name "Net-(LED11-CGREEN)") (class "Default")
      (node (ref "LED11") (pin "4") (pinfunction "CGREEN_4") (pintype "passive"))
      (node (ref "R29") (pin "1") (pinfunction "1_1") (pintype "passive"))
    )
    (net (code "124") (name "Net-(LED11-CRED)") (class "Default")
      (node (ref "LED11") (pin "2") (pinfunction "CRED_2") (pintype "passive"))
      (node (ref "R27") (pin "1") (pinfunction "1_1") (pintype "passive"))
    )
    (net (code "125") (name "Net-(LED12-PadC)") (class "Default")
      (node (ref "LED12") (pin "C") (pinfunction "C_C") (pintype "passive"))
      (node (ref "R54") (pin "1") (pinfunction "1_1") (pintype "passive"))
    )
    (net (code "126") (name "Net-(LED13-PadC)") (class "Default")
      (node (ref "LED13") (pin "C") (pinfunction "C_C") (pintype "passive"))
      (node (ref "R55") (pin "1") (pinfunction "1_1") (pintype "passive"))
    )
    (net (code "127") (name "Net-(LED14-PadC)") (class "Default")
      (node (ref "LED14") (pin "C") (pinfunction "C_C") (pintype "passive"))
      (node (ref "R56") (pin "1") (pinfunction "1_1") (pintype "passive"))
    )
    (net (code "128") (name "Net-(LED15-PadC)") (class "Default")
      (node (ref "LED15") (pin "C") (pinfunction "C_C") (pintype "passive"))
      (node (ref "R57") (pin "1") (pinfunction "1_1") (pintype "passive"))
    )
    (net (code "129") (name "Net-(LED16-PadC)") (class "Default")
      (node (ref "LED16") (pin "C") (pinfunction "C_C") (pintype "passive"))
      (node (ref "R58") (pin "1") (pinfunction "1_1") (pintype "passive"))
    )
    (net (code "130") (name "Net-(LED17-PadC)") (class "Default")
      (node (ref "LED17") (pin "C") (pinfunction "C_C") (pintype "passive"))
      (node (ref "R59") (pin "1") (pinfunction "1_1") (pintype "passive"))
    )
    (net (code "131") (name "Net-(LED18-PadC)") (class "Default")
      (node (ref "LED18") (pin "C") (pinfunction "C_C") (pintype "passive"))
      (node (ref "R60") (pin "1") (pinfunction "1_1") (pintype "passive"))
    )
    (net (code "132") (name "Net-(LED19-PadC)") (class "Default")
      (node (ref "LED19") (pin "C") (pinfunction "C_C") (pintype "passive"))
      (node (ref "R61") (pin "1") (pinfunction "1_1") (pintype "passive"))
    )
    (net (code "133") (name "Net-(OK1-VF1+)") (class "Default")
      (node (ref "OK1") (pin "1") (pinfunction "VF1+_1") (pintype "passive"))
      (node (ref "R87") (pin "2") (pinfunction "2_2") (pintype "passive"))
    )
    (net (code "134") (name "Net-(OK1-VF2+)") (class "Default")
      (node (ref "OK1") (pin "4") (pinfunction "VF2+_4") (pintype "passive"))
      (node (ref "R88") (pin "2") (pinfunction "2_2") (pintype "passive"))
    )
    (net (code "135") (name "Net-(OK1-VO1)") (class "Default")
      (node (ref "OK1") (pin "7") (pinfunction "VO1_7") (pintype "passive"))
      (node (ref "R79") (pin "1") (pinfunction "1_1") (pintype "passive"))
      (node (ref "R83") (pin "1") (pinfunction "1_1") (pintype "passive"))
    )
    (net (code "136") (name "Net-(OK1-VO2)") (class "Default")
      (node (ref "OK1") (pin "6") (pinfunction "VO2_6") (pintype "passive"))
      (node (ref "R80") (pin "1") (pinfunction "1_1") (pintype "passive"))
      (node (ref "R84") (pin "1") (pinfunction "1_1") (pintype "passive"))
    )
    (net (code "137") (name "Net-(OK2-VF1+)") (class "Default")
      (node (ref "OK2") (pin "1") (pinfunction "VF1+_1") (pintype "passive"))
      (node (ref "R89") (pin "2") (pinfunction "2_2") (pintype "passive"))
    )
    (net (code "138") (name "Net-(OK2-VF2+)") (class "Default")
      (node (ref "OK2") (pin "4") (pinfunction "VF2+_4") (pintype "passive"))
      (node (ref "R90") (pin "2") (pinfunction "2_2") (pintype "passive"))
    )
    (net (code "139") (name "Net-(OK2-VO1)") (class "Default")
      (node (ref "OK2") (pin "7") (pinfunction "VO1_7") (pintype "passive"))
      (node (ref "R81") (pin "1") (pinfunction "1_1") (pintype "passive"))
      (node (ref "R85") (pin "1") (pinfunction "1_1") (pintype "passive"))
    )
    (net (code "140") (name "Net-(OK2-VO2)") (class "Default")
      (node (ref "OK2") (pin "6") (pinfunction "VO2_6") (pintype "passive"))
      (node (ref "R82") (pin "1") (pinfunction "1_1") (pintype "passive"))
      (node (ref "R86") (pin "1") (pinfunction "1_1") (pintype "passive"))
    )
    (net (code "141") (name "Net-(OK3-AN1)") (class "Default")
      (node (ref "OK3") (pin "1") (pinfunction "AN1_1") (pintype "passive"))
      (node (ref "R95") (pin "2") (pinfunction "2_2") (pintype "passive"))
    )
    (net (code "142") (name "Net-(OK3-AN2)") (class "Default")
      (node (ref "OK3") (pin "3") (pinfunction "AN2_3") (pintype "passive"))
      (node (ref "R96") (pin "2") (pinfunction "2_2") (pintype "passive"))
    )
    (net (code "143") (name "Net-(OK3-AN3)") (class "Default")
      (node (ref "OK3") (pin "5") (pinfunction "AN3_5") (pintype "passive"))
      (node (ref "R97") (pin "2") (pinfunction "2_2") (pintype "passive"))
    )
    (net (code "144") (name "Net-(OK3-AN4)") (class "Default")
      (node (ref "OK3") (pin "7") (pinfunction "AN4_7") (pintype "passive"))
      (node (ref "R98") (pin "2") (pinfunction "2_2") (pintype "passive"))
    )
    (net (code "145") (name "Net-(OK3-EM1)") (class "Default")
      (node (ref "OK3") (pin "16") (pinfunction "EM1_16") (pintype "passive"))
      (node (ref "R103") (pin "1") (pinfunction "1_1") (pintype "passive"))
      (node (ref "R110") (pin "1") (pinfunction "1_1") (pintype "passive"))
    )
    (net (code "146") (name "Net-(OK3-EM2)") (class "Default")
      (node (ref "OK3") (pin "14") (pinfunction "EM2_14") (pintype "passive"))
      (node (ref "R104") (pin "1") (pinfunction "1_1") (pintype "passive"))
      (node (ref "R109") (pin "1") (pinfunction "1_1") (pintype "passive"))
    )
    (net (code "147") (name "Net-(OK3-EM3)") (class "Default")
      (node (ref "OK3") (pin "12") (pinfunction "EM3_12") (pintype "passive"))
      (node (ref "R105") (pin "1") (pinfunction "1_1") (pintype "passive"))
      (node (ref "R108") (pin "1") (pinfunction "1_1") (pintype "passive"))
    )
    (net (code "148") (name "Net-(OK3-EM4)") (class "Default")
      (node (ref "OK3") (pin "10") (pinfunction "EM4_10") (pintype "passive"))
      (node (ref "R106") (pin "1") (pinfunction "1_1") (pintype "passive"))
      (node (ref "R107") (pin "1") (pinfunction "1_1") (pintype "passive"))
    )
    (net (code "149") (name "Net-(Q3-IN1)") (class "Default")
      (node (ref "Q3") (pin "1") (pinfunction "IN1_1") (pintype "passive"))
      (node (ref "R82") (pin "2") (pinfunction "2_2") (pintype "passive"))
    )
    (net (code "150") (name "Net-(Q3-IN3)") (class "Default")
      (node (ref "Q3") (pin "3") (pinfunction "IN3_3") (pintype "passive"))
      (node (ref "R81") (pin "2") (pinfunction "2_2") (pintype "passive"))
    )
    (net (code "151") (name "Net-(Q3-IN5)") (class "Default")
      (node (ref "Q3") (pin "5") (pinfunction "IN5_5") (pintype "passive"))
      (node (ref "R80") (pin "2") (pinfunction "2_2") (pintype "passive"))
    )
    (net (code "152") (name "Net-(Q3-IN7)") (class "Default")
      (node (ref "Q3") (pin "7") (pinfunction "IN7_7") (pintype "passive"))
      (node (ref "R79") (pin "2") (pinfunction "2_2") (pintype "passive"))
    )
    (net (code "153") (name "Net-(Q4-IN1)") (class "Default")
      (node (ref "Q4") (pin "1") (pinfunction "IN1_1") (pintype "passive"))
      (node (ref "R106") (pin "2") (pinfunction "2_2") (pintype "passive"))
    )
    (net (code "154") (name "Net-(Q4-IN3)") (class "Default")
      (node (ref "Q4") (pin "3") (pinfunction "IN3_3") (pintype "passive"))
      (node (ref "R105") (pin "2") (pinfunction "2_2") (pintype "passive"))
    )
    (net (code "155") (name "Net-(Q4-IN5)") (class "Default")
      (node (ref "Q4") (pin "5") (pinfunction "IN5_5") (pintype "passive"))
      (node (ref "R104") (pin "2") (pinfunction "2_2") (pintype "passive"))
    )
    (net (code "156") (name "Net-(Q4-IN7)") (class "Default")
      (node (ref "Q4") (pin "7") (pinfunction "IN7_7") (pintype "passive"))
      (node (ref "R103") (pin "2") (pinfunction "2_2") (pintype "passive"))
    )
    (net (code "157") (name "Net-(T1-CT1)") (class "Default")
      (node (ref "C42") (pin "1") (pinfunction "1_1") (pintype "passive"))
      (node (ref "C43") (pin "1") (pinfunction "1_1") (pintype "passive"))
      (node (ref "R45") (pin "1") (pinfunction "1_1") (pintype "passive"))
      (node (ref "T1") (pin "2") (pinfunction "CT1_2") (pintype "passive"))
      (node (ref "T1") (pin "7") (pinfunction "CT2_7") (pintype "passive"))
    )
    (net (code "158") (name "Net-(T1-CT3)") (class "Default")
      (node (ref "R46") (pin "2") (pinfunction "2_2") (pintype "passive"))
      (node (ref "T1") (pin "10") (pinfunction "CT3_10") (pintype "passive"))
    )
    (net (code "159") (name "Net-(T1-CT4)") (class "Default")
      (node (ref "R47") (pin "2") (pinfunction "2_2") (pintype "passive"))
      (node (ref "T1") (pin "15") (pinfunction "CT4_15") (pintype "passive"))
    )
    (net (code "160") (name "Net-(T1-RD+)") (class "Default")
      (node (ref "R42") (pin "2") (pinfunction "2_2") (pintype "passive"))
      (node (ref "T1") (pin "6") (pinfunction "RD+_6") (pintype "passive"))
    )
    (net (code "161") (name "Net-(T1-RD-)") (class "Default")
      (node (ref "R44") (pin "2") (pinfunction "2_2") (pintype "passive"))
      (node (ref "T1") (pin "8") (pinfunction "RD-_8") (pintype "passive"))
    )
    (net (code "162") (name "Net-(T1-TD+)") (class "Default")
      (node (ref "R41") (pin "2") (pinfunction "2_2") (pintype "passive"))
      (node (ref "T1") (pin "1") (pinfunction "TD+_1") (pintype "passive"))
    )
    (net (code "163") (name "Net-(T1-TD-)") (class "Default")
      (node (ref "R43") (pin "2") (pinfunction "2_2") (pintype "passive"))
      (node (ref "T1") (pin "3") (pinfunction "TD-_3") (pintype "passive"))
    )
    (net (code "164") (name "Net-(X1B-KL)") (class "Default")
      (node (ref "R8") (pin "1") (pinfunction "1_1") (pintype "passive"))
      (node (ref "X1") (pin "2") (pinfunction "KL_2") (pintype "passive"))
    )
    (net (code "165") (name "Net-(X2A-KL)") (class "Default")
      (node (ref "R7") (pin "1") (pinfunction "1_1") (pintype "passive"))
      (node (ref "X2") (pin "1") (pinfunction "KL_1") (pintype "passive"))
    )
    (net (code "166") (name "Net-(X2B-KL)") (class "Default")
      (node (ref "R6") (pin "1") (pinfunction "1_1") (pintype "passive"))
      (node (ref "X2") (pin "2") (pinfunction "KL_2") (pintype "passive"))
    )
    (net (code "167") (name "Net-(X3A-KL)") (class "Default")
      (node (ref "R5") (pin "1") (pinfunction "1_1") (pintype "passive"))
      (node (ref "X3") (pin "1") (pinfunction "KL_1") (pintype "passive"))
    )
    (net (code "168") (name "Net-(X3B-KL)") (class "Default")
      (node (ref "R4") (pin "1") (pinfunction "1_1") (pintype "passive"))
      (node (ref "X3") (pin "2") (pinfunction "KL_2") (pintype "passive"))
    )
    (net (code "169") (name "Net-(X10A-KL)") (class "Default")
      (node (ref "R3") (pin "1") (pinfunction "1_1") (pintype "passive"))
      (node (ref "X10") (pin "1") (pinfunction "KL_1") (pintype "passive"))
    )
    (net (code "170") (name "Net-(X10B-KL)") (class "Default")
      (node (ref "R2") (pin "1") (pinfunction "1_1") (pintype "passive"))
      (node (ref "X10") (pin "2") (pinfunction "KL_2") (pintype "passive"))
    )
    (net (code "171") (name "Net-(X11A-KL)") (class "Default")
      (node (ref "R1") (pin "1") (pinfunction "1_1") (pintype "passive"))
      (node (ref "X11") (pin "1") (pinfunction "KL_1") (pintype "passive"))
    )
    (net (code "172") (name "OUT1.1") (class "Default")
      (node (ref "Q3") (pin "18") (pinfunction "OUT1_18") (pintype "passive"))
      (node (ref "X6") (pin "1") (pinfunction "KL_1") (pintype "passive"))
    )
    (net (code "173") (name "OUT1.2") (class "Default")
      (node (ref "Q3") (pin "16") (pinfunction "OUT3_16") (pintype "passive"))
      (node (ref "X6") (pin "2") (pinfunction "KL_2") (pintype "passive"))
    )
    (net (code "174") (name "OUT1.3") (class "Default")
      (node (ref "Q3") (pin "14") (pinfunction "OUT5_14") (pintype "passive"))
      (node (ref "X5") (pin "1") (pinfunction "KL_1") (pintype "passive"))
    )
    (net (code "175") (name "OUT1.4") (class "Default")
      (node (ref "Q3") (pin "12") (pinfunction "OUT7_12") (pintype "passive"))
      (node (ref "X5") (pin "2") (pinfunction "KL_2") (pintype "passive"))
    )
    (net (code "176") (name "OUT2.1") (class "Default")
      (node (ref "Q4") (pin "18") (pinfunction "OUT1_18") (pintype "passive"))
      (node (ref "X9") (pin "1") (pinfunction "KL_1") (pintype "passive"))
    )
    (net (code "177") (name "OUT2.2") (class "Default")
      (node (ref "Q4") (pin "16") (pinfunction "OUT3_16") (pintype "passive"))
      (node (ref "X9") (pin "2") (pinfunction "KL_2") (pintype "passive"))
    )
    (net (code "178") (name "OUT2.3") (class "Default")
      (node (ref "Q4") (pin "14") (pinfunction "OUT5_14") (pintype "passive"))
      (node (ref "X8") (pin "1") (pinfunction "KL_1") (pintype "passive"))
    )
    (net (code "179") (name "OUT2.4") (class "Default")
      (node (ref "Q4") (pin "12") (pinfunction "OUT7_12") (pintype "passive"))
      (node (ref "X8") (pin "2") (pinfunction "KL_2") (pintype "passive"))
    )
    (net (code "180") (name "PE") (class "Default")
      (node (ref "C44") (pin "2") (pinfunction "2_2") (pintype "passive"))
      (node (ref "C45") (pin "2") (pinfunction "2_2") (pintype "passive"))
      (node (ref "J1") (pin "HOLE1") (pinfunction "GROUND_HOLE1") (pintype "bidirectional"))
      (node (ref "J1") (pin "HOLE2") (pinfunction "GROUND_HOLE2") (pintype "bidirectional"))
    )
    (net (code "181") (name "PFB") (class "Default")
      (node (ref "C36") (pin "+") (pinfunction "+_+") (pintype "passive"))
      (node (ref "C38") (pin "1") (pinfunction "1_1") (pintype "passive"))
      (node (ref "C39") (pin "1") (pinfunction "1_1") (pintype "passive"))
      (node (ref "C40") (pin "1") (pinfunction "1_1") (pintype "passive"))
      (node (ref "IC3") (pin "18") (pinfunction "PFBIN1_18") (pintype "power_in"))
      (node (ref "IC3") (pin "23") (pinfunction "PFBOUT_23") (pintype "output"))
      (node (ref "IC3") (pin "37") (pinfunction "PFBIN2_37") (pintype "power_in"))
    )
    (net (code "182") (name "RMII_CRS_DV") (class "Default")
      (node (ref "IC2") (pin "43") (pinfunction "PA7_43") (pintype "bidirectional"))
      (node (ref "IC3") (pin "40") (pinfunction "CRS_DV_40") (pintype "bidirectional"))
    )
    (net (code "183") (name "RMII_MDC") (class "Default")
      (node (ref "IC2") (pin "27") (pinfunction "PC1_27") (pintype "bidirectional"))
      (node (ref "IC3") (pin "31") (pinfunction "MDC_31") (pintype "input"))
    )
    (net (code "184") (name "RMII_MDIO") (class "Default")
      (node (ref "IC2") (pin "36") (pinfunction "PA2_36") (pintype "bidirectional"))
      (node (ref "IC3") (pin "30") (pinfunction "MDIO_30") (pintype "bidirectional"))
      (node (ref "R31") (pin "2") (pinfunction "2_2") (pintype "passive"))
    )
    (net (code "185") (name "RMII_RXD0") (class "Default")
      (node (ref "IC2") (pin "44") (pinfunction "PC4_44") (pintype "bidirectional"))
      (node (ref "IC3") (pin "43") (pinfunction "RXD_0_43") (pintype "bidirectional"))
    )
    (net (code "186") (name "RMII_RXD1") (class "Default")
      (node (ref "IC2") (pin "45") (pinfunction "PC5_45") (pintype "bidirectional"))
      (node (ref "IC3") (pin "44") (pinfunction "RXD_1_44") (pintype "bidirectional"))
    )
    (net (code "187") (name "RMII_TXD0") (class "Default")
      (node (ref "IC2") (pin "73") (pinfunction "PB12_73") (pintype "bidirectional"))
      (node (ref "IC3") (pin "3") (pinfunction "TXD_0_3") (pintype "bidirectional"))
    )
    (net (code "188") (name "RMII_TXD1") (class "Default")
      (node (ref "IC2") (pin "74") (pinfunction "PB13_74") (pintype "bidirectional"))
      (node (ref "IC3") (pin "4") (pinfunction "TXD_1_4") (pintype "bidirectional"))
    )
    (net (code "189") (name "RMII_TX_EN") (class "Default")
      (node (ref "IC2") (pin "70") (pinfunction "PB11_70") (pintype "bidirectional"))
      (node (ref "IC3") (pin "2") (pinfunction "TX_EN_2") (pintype "bidirectional"))
    )
    (net (code "190") (name "SPI_MISO") (class "Default")
      (node (ref "IC2") (pin "112") (pinfunction "PC11_112") (pintype "bidirectional"))
      (node (ref "R71") (pin "2") (pinfunction "2_2") (pintype "passive"))
    )
    (net (code "191") (name "SPI_MOSI") (class "Default")
      (node (ref "IC2") (pin "113") (pinfunction "PC12_113") (pintype "bidirectional"))
      (node (ref "R62") (pin "1") (pinfunction "1_1") (pintype "passive"))
    )
    (net (code "192") (name "SPI_SCK") (class "Default")
      (node (ref "IC2") (pin "111") (pinfunction "PC10_111") (pintype "bidirectional"))
      (node (ref "R63") (pin "1") (pinfunction "1_1") (pintype "passive"))
    )
    (net (code "193") (name "SWCLK") (class "Default")
      (node (ref "IC2") (pin "109") (pinfunction "PA14_109") (pintype "bidirectional"))
      (node (ref "SV1") (pin "6") (pinfunction "6_6") (pintype "passive"))
    )
    (net (code "194") (name "SWDIO") (class "Default")
      (node (ref "IC2") (pin "105") (pinfunction "PA13_105") (pintype "bidirectional"))
      (node (ref "SV1") (pin "2") (pinfunction "2_2") (pintype "passive"))
    )
    (net (code "195") (name "SWO") (class "Default")
      (node (ref "IC2") (pin "133") (pinfunction "PB3_133") (pintype "bidirectional"))
      (node (ref "SV1") (pin "5") (pinfunction "5_5") (pintype "passive"))
    )
    (net (code "196") (name "unconnected-(IC2-BOOT0-Pad138)") (class "Default")
      (node (ref "IC2") (pin "138") (pinfunction "BOOT0_138") (pintype "bidirectional"))
    )
    (net (code "197") (name "unconnected-(IC2-PA0-Pad34)") (class "Default")
      (node (ref "IC2") (pin "34") (pinfunction "PA0_34") (pintype "bidirectional"))
    )
    (net (code "198") (name "unconnected-(IC2-PA1-Pad35)") (class "Default")
      (node (ref "IC2") (pin "35") (pinfunction "PA1_35") (pintype "bidirectional"))
    )
    (net (code "199") (name "unconnected-(IC2-PA3-Pad37)") (class "Default")
      (node (ref "IC2") (pin "37") (pinfunction "PA3_37") (pintype "bidirectional"))
    )
    (net (code "200") (name "unconnected-(IC2-PA4-Pad40)") (class "Default")
      (node (ref "IC2") (pin "40") (pinfunction "PA4_40") (pintype "bidirectional"))
    )
    (net (code "201") (name "unconnected-(IC2-PA5-Pad41)") (class "Default")
      (node (ref "IC2") (pin "41") (pinfunction "PA5_41") (pintype "bidirectional"))
    )
    (net (code "202") (name "unconnected-(IC2-PA6-Pad42)") (class "Default")
      (node (ref "IC2") (pin "42") (pinfunction "PA6_42") (pintype "bidirectional"))
    )
    (net (code "203") (name "unconnected-(IC2-PA11-Pad103)") (class "Default")
      (node (ref "IC2") (pin "103") (pinfunction "PA11_103") (pintype "bidirectional"))
    )
    (net (code "204") (name "unconnected-(IC2-PA12-Pad104)") (class "Default")
      (node (ref "IC2") (pin "104") (pinfunction "PA12_104") (pintype "bidirectional"))
    )
    (net (code "205") (name "unconnected-(IC2-PA15-Pad110)") (class "Default")
      (node (ref "IC2") (pin "110") (pinfunction "PA15_110") (pintype "bidirectional"))
    )
    (net (code "206") (name "unconnected-(IC2-PB0-Pad46)") (class "Default")
      (node (ref "IC2") (pin "46") (pinfunction "PB0_46") (pintype "bidirectional"))
    )
    (net (code "207") (name "unconnected-(IC2-PB1-Pad47)") (class "Default")
      (node (ref "IC2") (pin "47") (pinfunction "PB1_47") (pintype "bidirectional"))
    )
    (net (code "208") (name "unconnected-(IC2-PB2-Pad48)") (class "Default")
      (node (ref "IC2") (pin "48") (pinfunction "PB2_48") (pintype "bidirectional"))
    )
    (net (code "209") (name "unconnected-(IC2-PB10-Pad69)") (class "Default")
      (node (ref "IC2") (pin "69") (pinfunction "PB10_69") (pintype "bidirectional"))
    )
    (net (code "210") (name "unconnected-(IC2-PC0-Pad26)") (class "Default")
      (node (ref "IC2") (pin "26") (pinfunction "PC0_26") (pintype "bidirectional"))
    )
    (net (code "211") (name "unconnected-(IC2-PC2-Pad28)") (class "Default")
      (node (ref "IC2") (pin "28") (pinfunction "PC2_28") (pintype "bidirectional"))
    )
    (net (code "212") (name "unconnected-(IC2-PC3-Pad29)") (class "Default")
      (node (ref "IC2") (pin "29") (pinfunction "PC3_29") (pintype "bidirectional"))
    )
    (net (code "213") (name "unconnected-(IC2-PC6-Pad96)") (class "Default")
      (node (ref "IC2") (pin "96") (pinfunction "PC6_96") (pintype "bidirectional"))
    )
    (net (code "214") (name "unconnected-(IC2-PC7-Pad97)") (class "Default")
      (node (ref "IC2") (pin "97") (pinfunction "PC7_97") (pintype "bidirectional"))
    )
    (net (code "215") (name "unconnected-(IC2-PC13-Pad7)") (class "Default")
      (node (ref "IC2") (pin "7") (pinfunction "PC13_7") (pintype "bidirectional"))
    )
    (net (code "216") (name "unconnected-(IC2-PD0-Pad114)") (class "Default")
      (node (ref "IC2") (pin "114") (pinfunction "PD0_114") (pintype "bidirectional"))
    )
    (net (code "217") (name "unconnected-(IC2-PD1-Pad115)") (class "Default")
      (node (ref "IC2") (pin "115") (pinfunction "PD1_115") (pintype "bidirectional"))
    )
    (net (code "218") (name "unconnected-(IC2-PD2-Pad116)") (class "Default")
      (node (ref "IC2") (pin "116") (pinfunction "PD2_116") (pintype "bidirectional"))
    )
    (net (code "219") (name "unconnected-(IC2-PD3-Pad117)") (class "Default")
      (node (ref "IC2") (pin "117") (pinfunction "PD3_117") (pintype "bidirectional"))
    )
    (net (code "220") (name "unconnected-(IC2-PD4-Pad118)") (class "Default")
      (node (ref "IC2") (pin "118") (pinfunction "PD4_118") (pintype "bidirectional"))
    )
    (net (code "221") (name "unconnected-(IC2-PD5-Pad119)") (class "Default")
      (node (ref "IC2") (pin "119") (pinfunction "PD5_119") (pintype "bidirectional"))
    )
    (net (code "222") (name "unconnected-(IC2-PD6-Pad122)") (class "Default")
      (node (ref "IC2") (pin "122") (pinfunction "PD6_122") (pintype "bidirectional"))
    )
    (net (code "223") (name "unconnected-(IC2-PD7-Pad123)") (class "Default")
      (node (ref "IC2") (pin "123") (pinfunction "PD7_123") (pintype "bidirectional"))
    )
    (net (code "224") (name "unconnected-(IC2-PD12-Pad81)") (class "Default")
      (node (ref "IC2") (pin "81") (pinfunction "PD12_81") (pintype "bidirectional"))
    )
    (net (code "225") (name "unconnected-(IC2-PD13-Pad82)") (class "Default")
      (node (ref "IC2") (pin "82") (pinfunction "PD13_82") (pintype "bidirectional"))
    )
    (net (code "226") (name "unconnected-(IC2-PD14-Pad85)") (class "Default")
      (node (ref "IC2") (pin "85") (pinfunction "PD14_85") (pintype "bidirectional"))
    )
    (net (code "227") (name "unconnected-(IC2-PD15-Pad86)") (class "Default")
      (node (ref "IC2") (pin "86") (pinfunction "PD15_86") (pintype "bidirectional"))
    )
    (net (code "228") (name "unconnected-(IC2-PE5-Pad4)") (class "Default")
      (node (ref "IC2") (pin "4") (pinfunction "PE5_4") (pintype "bidirectional"))
    )
    (net (code "229") (name "unconnected-(IC2-PE6-Pad5)") (class "Default")
      (node (ref "IC2") (pin "5") (pinfunction "PE6_5") (pintype "bidirectional"))
    )
    (net (code "230") (name "unconnected-(IC2-PE7-Pad58)") (class "Default")
      (node (ref "IC2") (pin "58") (pinfunction "PE7_58") (pintype "bidirectional"))
    )
    (net (code "231") (name "unconnected-(IC2-PE8-Pad59)") (class "Default")
      (node (ref "IC2") (pin "59") (pinfunction "PE8_59") (pintype "bidirectional"))
    )
    (net (code "232") (name "unconnected-(IC2-PE9-Pad60)") (class "Default")
      (node (ref "IC2") (pin "60") (pinfunction "PE9_60") (pintype "bidirectional"))
    )
    (net (code "233") (name "unconnected-(IC2-PE10-Pad63)") (class "Default")
      (node (ref "IC2") (pin "63") (pinfunction "PE10_63") (pintype "bidirectional"))
    )
    (net (code "234") (name "unconnected-(IC2-PE11-Pad64)") (class "Default")
      (node (ref "IC2") (pin "64") (pinfunction "PE11_64") (pintype "bidirectional"))
    )
    (net (code "235") (name "unconnected-(IC2-PF0-Pad10)") (class "Default")
      (node (ref "IC2") (pin "10") (pinfunction "PF0_10") (pintype "bidirectional"))
    )
    (net (code "236") (name "unconnected-(IC2-PF1-Pad11)") (class "Default")
      (node (ref "IC2") (pin "11") (pinfunction "PF1_11") (pintype "bidirectional"))
    )
    (net (code "237") (name "unconnected-(IC2-PF2-Pad12)") (class "Default")
      (node (ref "IC2") (pin "12") (pinfunction "PF2_12") (pintype "bidirectional"))
    )
    (net (code "238") (name "unconnected-(IC2-PF3-Pad13)") (class "Default")
      (node (ref "IC2") (pin "13") (pinfunction "PF3_13") (pintype "bidirectional"))
    )
    (net (code "239") (name "unconnected-(IC2-PF4-Pad14)") (class "Default")
      (node (ref "IC2") (pin "14") (pinfunction "PF4_14") (pintype "bidirectional"))
    )
    (net (code "240") (name "unconnected-(IC2-PF5-Pad15)") (class "Default")
      (node (ref "IC2") (pin "15") (pinfunction "PF5_15") (pintype "bidirectional"))
    )
    (net (code "241") (name "unconnected-(IC2-PF9-Pad21)") (class "Default")
      (node (ref "IC2") (pin "21") (pinfunction "PF9_21") (pintype "bidirectional"))
    )
    (net (code "242") (name "unconnected-(IC2-PF10-Pad22)") (class "Default")
      (node (ref "IC2") (pin "22") (pinfunction "PF10_22") (pintype "bidirectional"))
    )
    (net (code "243") (name "unconnected-(IC2-PF11-Pad49)") (class "Default")
      (node (ref "IC2") (pin "49") (pinfunction "PF11_49") (pintype "bidirectional"))
    )
    (net (code "244") (name "unconnected-(IC2-PF12-Pad50)") (class "Default")
      (node (ref "IC2") (pin "50") (pinfunction "PF12_50") (pintype "bidirectional"))
    )
    (net (code "245") (name "unconnected-(IC2-PF13-Pad53)") (class "Default")
      (node (ref "IC2") (pin "53") (pinfunction "PF13_53") (pintype "bidirectional"))
    )
    (net (code "246") (name "unconnected-(IC2-PG2-Pad87)") (class "Default")
      (node (ref "IC2") (pin "87") (pinfunction "PG2_87") (pintype "bidirectional"))
    )
    (net (code "247") (name "unconnected-(IC2-PG6-Pad91)") (class "Default")
      (node (ref "IC2") (pin "91") (pinfunction "PG6_91") (pintype "bidirectional"))
    )
    (net (code "248") (name "unconnected-(IC2-PG7-Pad92)") (class "Default")
      (node (ref "IC2") (pin "92") (pinfunction "PG7_92") (pintype "bidirectional"))
    )
    (net (code "249") (name "unconnected-(IC2-PG8-Pad93)") (class "Default")
      (node (ref "IC2") (pin "93") (pinfunction "PG8_93") (pintype "bidirectional"))
    )
    (net (code "250") (name "unconnected-(IC2-PG9-Pad124)") (class "Default")
      (node (ref "IC2") (pin "124") (pinfunction "PG9_124") (pintype "bidirectional"))
    )
    (net (code "251") (name "unconnected-(IC2-PG10-Pad125)") (class "Default")
      (node (ref "IC2") (pin "125") (pinfunction "PG10_125") (pintype "bidirectional"))
    )
    (net (code "252") (name "unconnected-(IC2-PG11-Pad126)") (class "Default")
      (node (ref "IC2") (pin "126") (pinfunction "PG11_126") (pintype "bidirectional"))
    )
    (net (code "253") (name "unconnected-(IC2-PG12-Pad127)") (class "Default")
      (node (ref "IC2") (pin "127") (pinfunction "PG12_127") (pintype "bidirectional"))
    )
    (net (code "254") (name "unconnected-(IC2-PG13-Pad128)") (class "Default")
      (node (ref "IC2") (pin "128") (pinfunction "PG13_128") (pintype "bidirectional"))
    )
    (net (code "255") (name "unconnected-(IC2-PG14-Pad129)") (class "Default")
      (node (ref "IC2") (pin "129") (pinfunction "PG14_129") (pintype "bidirectional"))
    )
    (net (code "256") (name "unconnected-(IC2-PG15-Pad132)") (class "Default")
      (node (ref "IC2") (pin "132") (pinfunction "PG15_132") (pintype "bidirectional"))
    )
    (net (code "257") (name "unconnected-(IC3-CLK_OUT-Pad25)") (class "Default")
      (node (ref "IC3") (pin "25") (pinfunction "CLK_OUT_25") (pintype "bidirectional"))
    )
    (net (code "258") (name "unconnected-(IC3-COL-Pad42)") (class "Default")
      (node (ref "IC3") (pin "42") (pinfunction "COL_42") (pintype "bidirectional"))
    )
    (net (code "259") (name "unconnected-(IC3-PWR_DOWN-Pad7)") (class "Default")
      (node (ref "IC3") (pin "7") (pinfunction "PWR_DOWN_7") (pintype "bidirectional"))
    )
    (net (code "260") (name "unconnected-(IC3-RXD_2-Pad45)") (class "Default")
      (node (ref "IC3") (pin "45") (pinfunction "RXD_2_45") (pintype "bidirectional"))
    )
    (net (code "261") (name "unconnected-(IC3-RXD_3-Pad46)") (class "Default")
      (node (ref "IC3") (pin "46") (pinfunction "RXD_3_46") (pintype "bidirectional"))
    )
    (net (code "262") (name "unconnected-(IC3-RX_CLK-Pad38)") (class "Default")
      (node (ref "IC3") (pin "38") (pinfunction "RX_CLK_38") (pintype "bidirectional"))
    )
    (net (code "263") (name "unconnected-(IC3-RX_ER-Pad41)") (class "Default")
      (node (ref "IC3") (pin "41") (pinfunction "RX_ER_41") (pintype "bidirectional"))
    )
    (net (code "264") (name "unconnected-(IC3-TCK-Pad8)") (class "Default")
      (node (ref "IC3") (pin "8") (pinfunction "TCK_8") (pintype "input"))
    )
    (net (code "265") (name "unconnected-(IC3-TDI-Pad12)") (class "Default")
      (node (ref "IC3") (pin "12") (pinfunction "TDI_12") (pintype "input"))
    )
    (net (code "266") (name "unconnected-(IC3-TDO-Pad9)") (class "Default")
      (node (ref "IC3") (pin "9") (pinfunction "TDO_9") (pintype "output"))
    )
    (net (code "267") (name "unconnected-(IC3-TMS-Pad10)") (class "Default")
      (node (ref "IC3") (pin "10") (pinfunction "TMS_10") (pintype "input"))
    )
    (net (code "268") (name "unconnected-(IC3-TRST_N-Pad11)") (class "Default")
      (node (ref "IC3") (pin "11") (pinfunction "TRST_N_11") (pintype "input"))
    )
    (net (code "269") (name "unconnected-(IC3-TXD_2-Pad5)") (class "Default")
      (node (ref "IC3") (pin "5") (pinfunction "TXD_2_5") (pintype "bidirectional"))
    )
    (net (code "270") (name "unconnected-(IC3-TX_CLK-Pad1)") (class "Default")
      (node (ref "IC3") (pin "1") (pinfunction "TX_CLK_1") (pintype "bidirectional"))
    )
    (net (code "271") (name "unconnected-(IC3-X2-Pad33)") (class "Default")
      (node (ref "IC3") (pin "33") (pinfunction "X2_33") (pintype "output"))
    )
    (net (code "272") (name "unconnected-(IC4-MODE-Pad8)") (class "Default")
      (node (ref "IC4") (pin "8") (pinfunction "MODE_8") (pintype "input"))
    )
    (net (code "273") (name "unconnected-(IC4-SS-Pad4)") (class "Default")
      (node (ref "IC4") (pin "4") (pinfunction "SS_4") (pintype "input"))
    )
    (net (code "274") (name "unconnected-(IC4-{slash}RST-Pad7)") (class "Default")
      (node (ref "IC4") (pin "7") (pinfunction "/RST_7") (pintype "input"))
    )
    (net (code "275") (name "unconnected-(IC5-MODE-Pad8)") (class "Default")
      (node (ref "IC5") (pin "8") (pinfunction "MODE_8") (pintype "input"))
    )
    (net (code "276") (name "unconnected-(IC5-SS-Pad4)") (class "Default")
      (node (ref "IC5") (pin "4") (pinfunction "SS_4") (pintype "input"))
    )
    (net (code "277") (name "unconnected-(IC5-{slash}RST-Pad7)") (class "Default")
      (node (ref "IC5") (pin "7") (pinfunction "/RST_7") (pintype "input"))
    )
    (net (code "278") (name "unconnected-(OS1-CON-Pad1)") (class "Default")
      (node (ref "OS1") (pin "1") (pinfunction "CON_1") (pintype "input"))
    )
    (net (code "279") (name "unconnected-(Q3-IN2-Pad2)") (class "Default")
      (node (ref "Q3") (pin "2") (pinfunction "IN2_2") (pintype "passive"))
    )
    (net (code "280") (name "unconnected-(Q3-IN4-Pad4)") (class "Default")
      (node (ref "Q3") (pin "4") (pinfunction "IN4_4") (pintype "passive"))
    )
    (net (code "281") (name "unconnected-(Q3-IN6-Pad6)") (class "Default")
      (node (ref "Q3") (pin "6") (pinfunction "IN6_6") (pintype "passive"))
    )
    (net (code "282") (name "unconnected-(Q3-IN8-Pad8)") (class "Default")
      (node (ref "Q3") (pin "8") (pinfunction "IN8_8") (pintype "passive"))
    )
    (net (code "283") (name "unconnected-(Q3-OUT2-Pad17)") (class "Default")
      (node (ref "Q3") (pin "17") (pinfunction "OUT2_17") (pintype "passive"))
    )
    (net (code "284") (name "unconnected-(Q3-OUT4-Pad15)") (class "Default")
      (node (ref "Q3") (pin "15") (pinfunction "OUT4_15") (pintype "passive"))
    )
    (net (code "285") (name "unconnected-(Q3-OUT6-Pad13)") (class "Default")
      (node (ref "Q3") (pin "13") (pinfunction "OUT6_13") (pintype "passive"))
    )
    (net (code "286") (name "unconnected-(Q3-OUT8-Pad11)") (class "Default")
      (node (ref "Q3") (pin "11") (pinfunction "OUT8_11") (pintype "passive"))
    )
    (net (code "287") (name "unconnected-(Q4-IN2-Pad2)") (class "Default")
      (node (ref "Q4") (pin "2") (pinfunction "IN2_2") (pintype "passive"))
    )
    (net (code "288") (name "unconnected-(Q4-IN4-Pad4)") (class "Default")
      (node (ref "Q4") (pin "4") (pinfunction "IN4_4") (pintype "passive"))
    )
    (net (code "289") (name "unconnected-(Q4-IN6-Pad6)") (class "Default")
      (node (ref "Q4") (pin "6") (pinfunction "IN6_6") (pintype "passive"))
    )
    (net (code "290") (name "unconnected-(Q4-IN8-Pad8)") (class "Default")
      (node (ref "Q4") (pin "8") (pinfunction "IN8_8") (pintype "passive"))
    )
    (net (code "291") (name "unconnected-(Q4-OUT2-Pad17)") (class "Default")
      (node (ref "Q4") (pin "17") (pinfunction "OUT2_17") (pintype "passive"))
    )
    (net (code "292") (name "unconnected-(Q4-OUT4-Pad15)") (class "Default")
      (node (ref "Q4") (pin "15") (pinfunction "OUT4_15") (pintype "passive"))
    )
    (net (code "293") (name "unconnected-(Q4-OUT6-Pad13)") (class "Default")
      (node (ref "Q4") (pin "13") (pinfunction "OUT6_13") (pintype "passive"))
    )
    (net (code "294") (name "unconnected-(Q4-OUT8-Pad11)") (class "Default")
      (node (ref "Q4") (pin "11") (pinfunction "OUT8_11") (pintype "passive"))
    )
    (net (code "295") (name "unconnected-(SV1-Pad9)") (class "Default")
      (node (ref "SV1") (pin "9") (pinfunction "9_9") (pintype "passive"))
    )
    (net (code "296") (name "unconnected-(SV1-Pad10)") (class "Default")
      (node (ref "SV1") (pin "10") (pinfunction "10_10") (pintype "passive"))
    )
  )
)
